# smrf-v1_0_1b.net
KiCad netlist of a schematic drawn in EAGLE
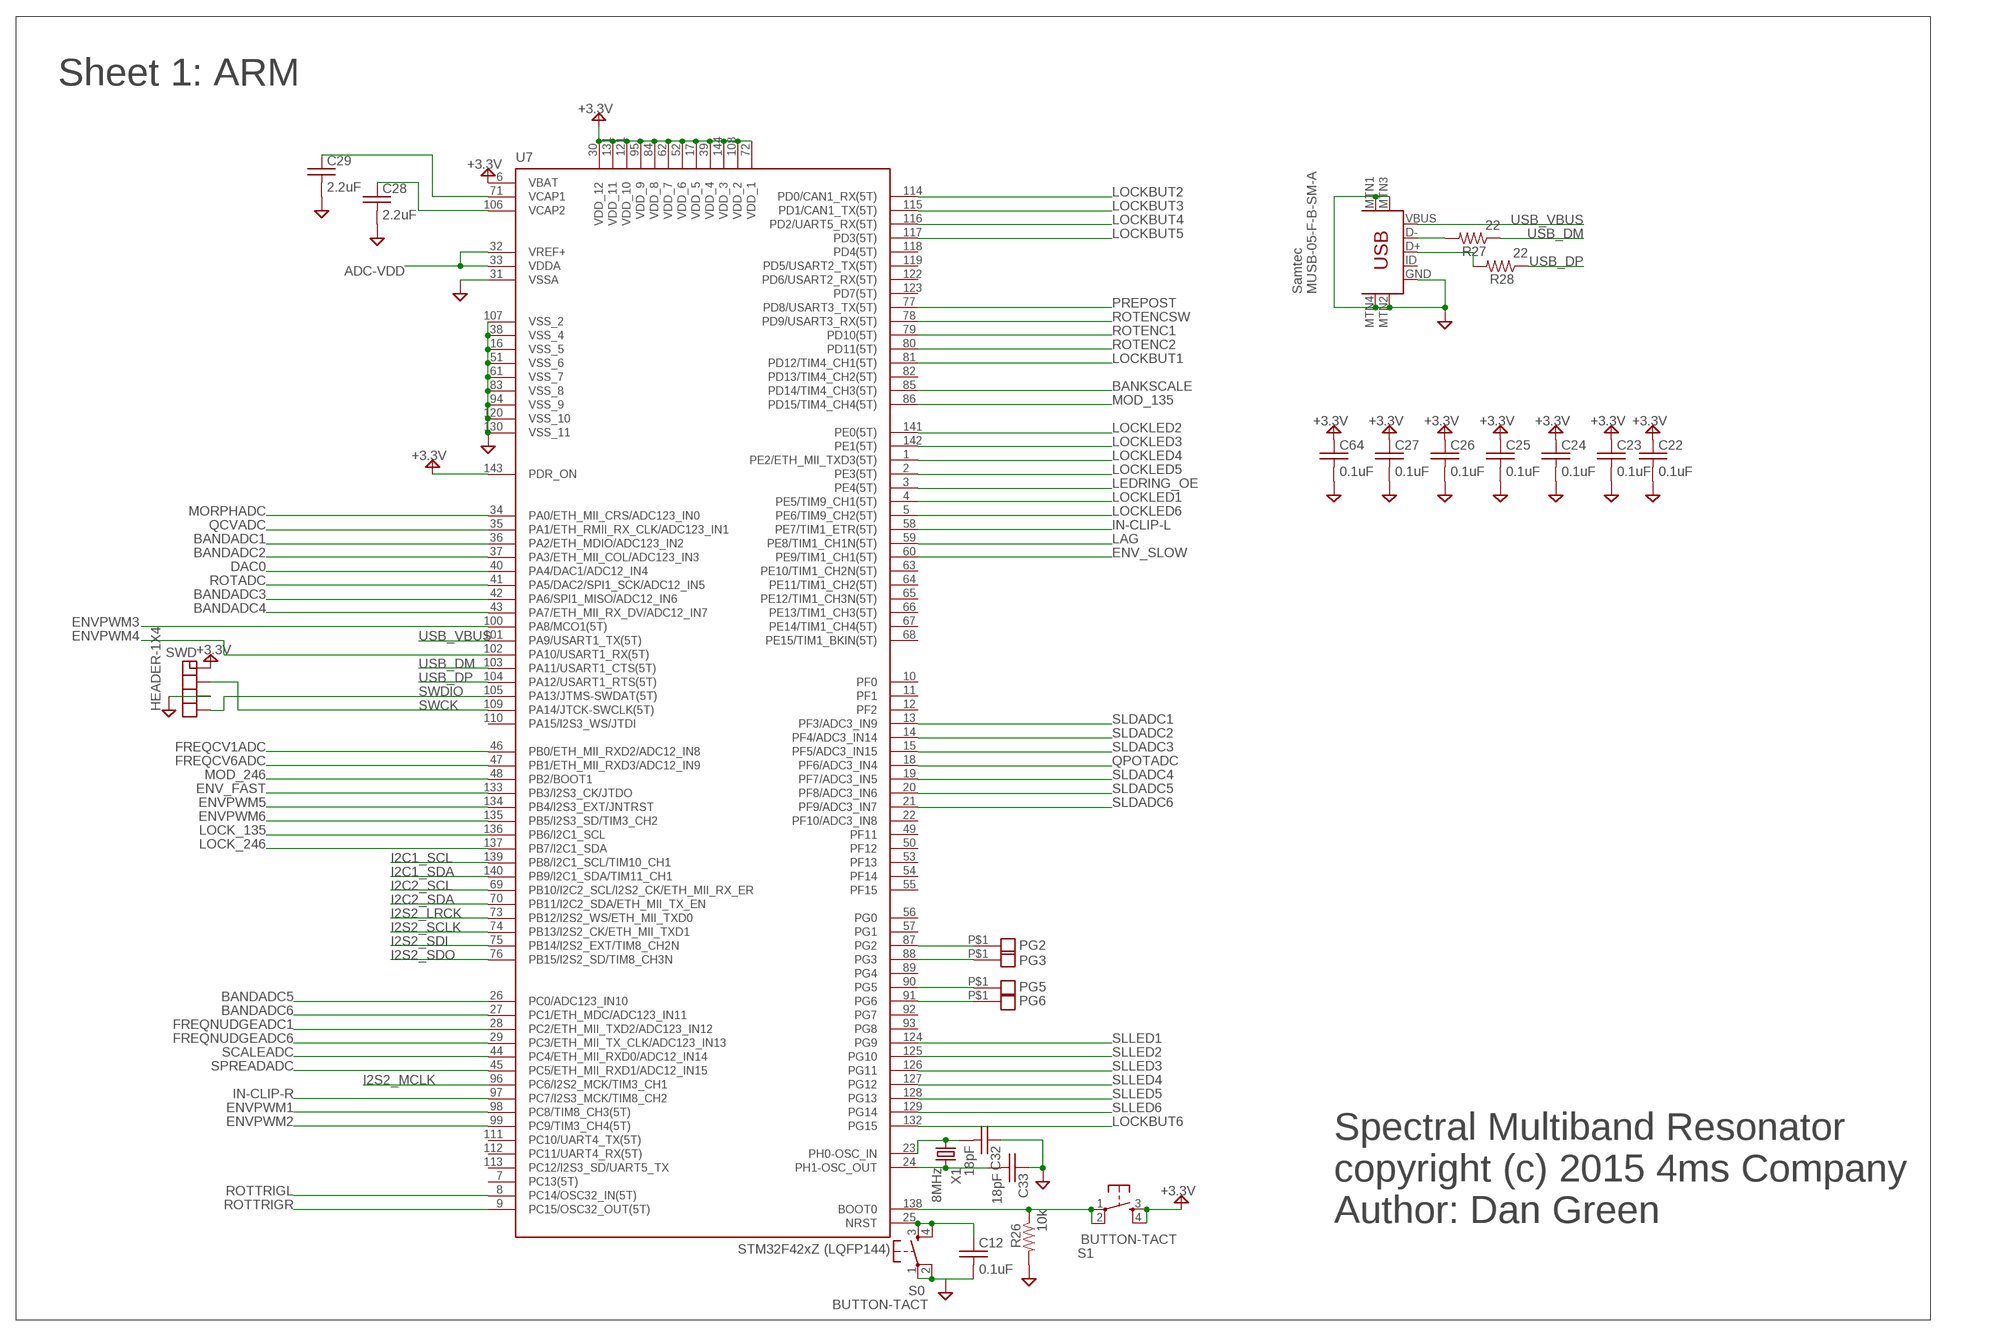
[diagram p0: schematic, sheet 1]
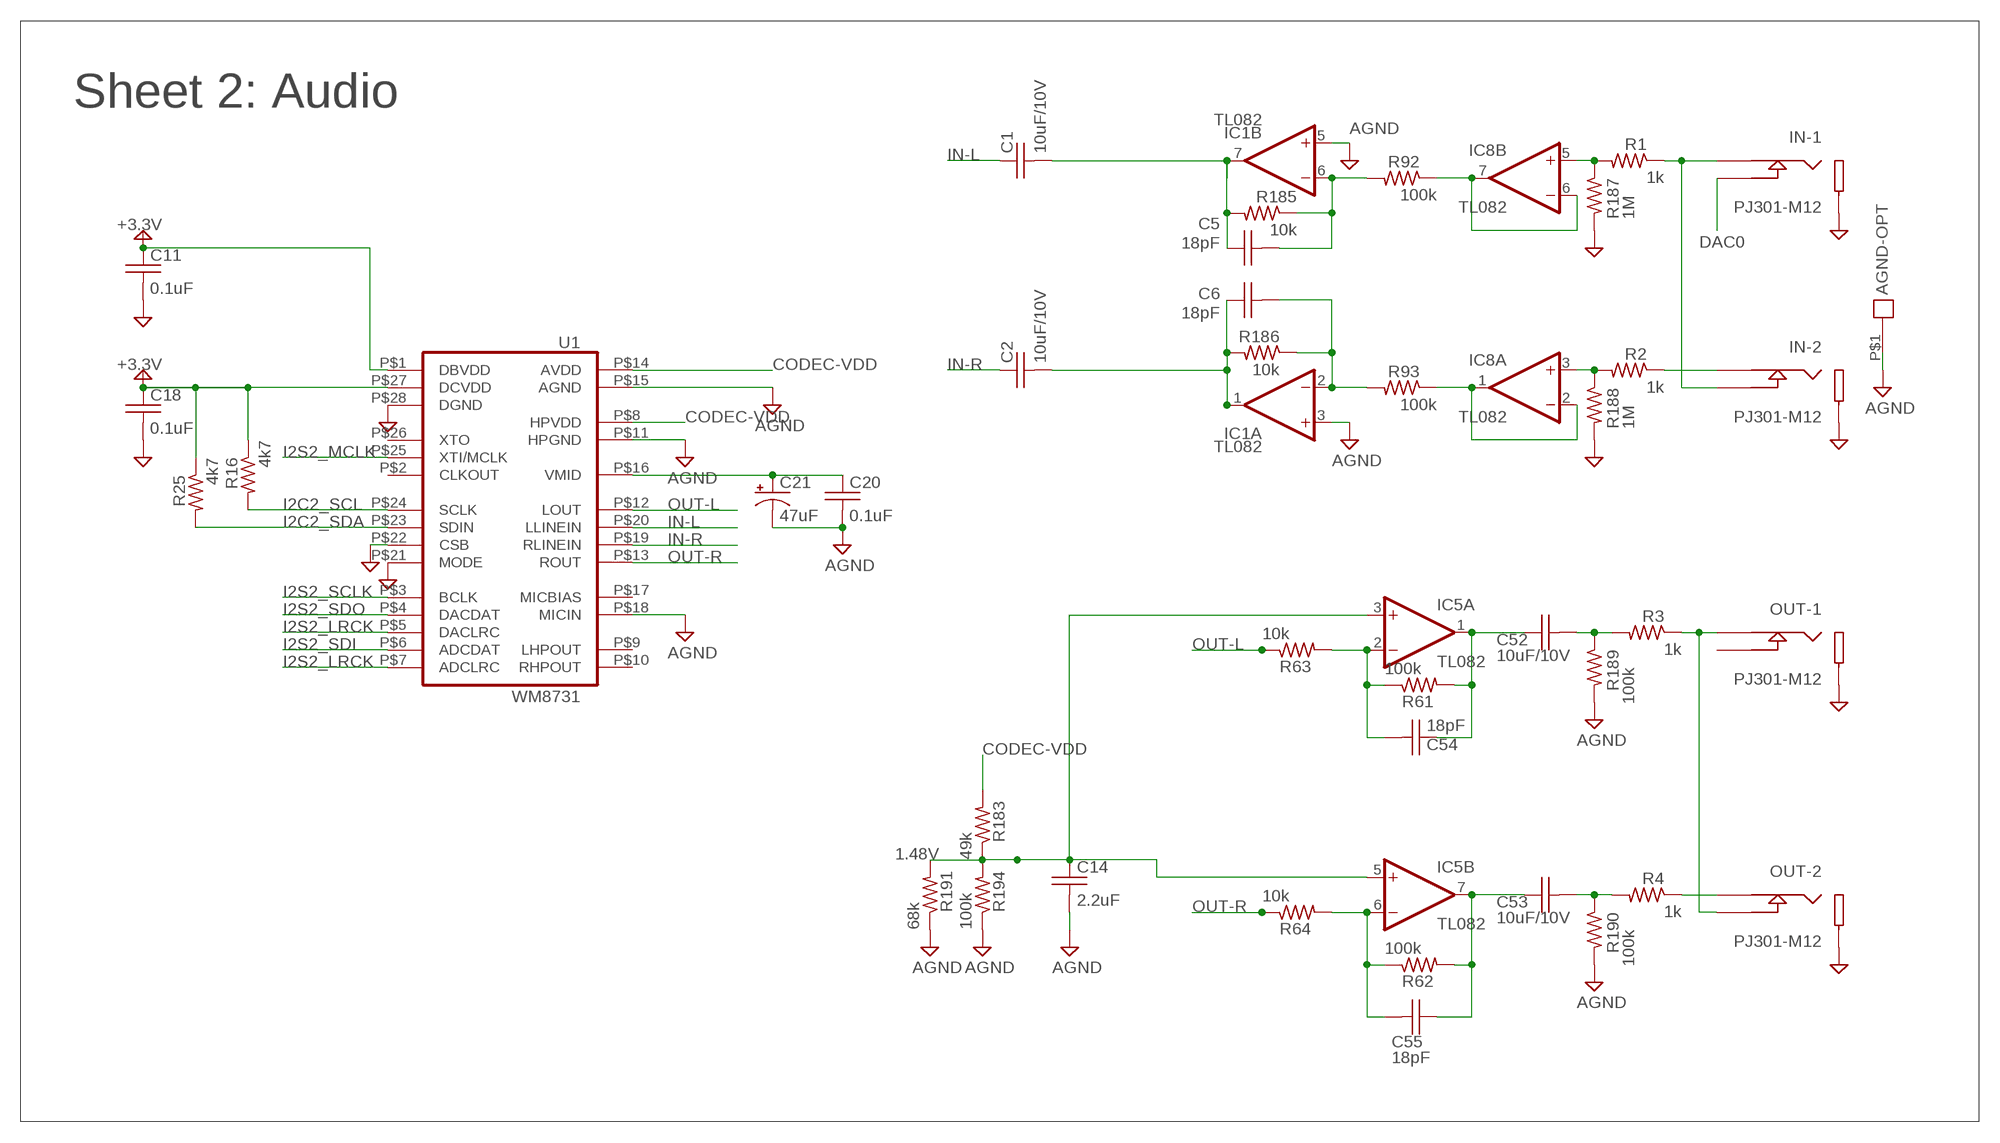
[diagram p1: schematic, sheet 2]
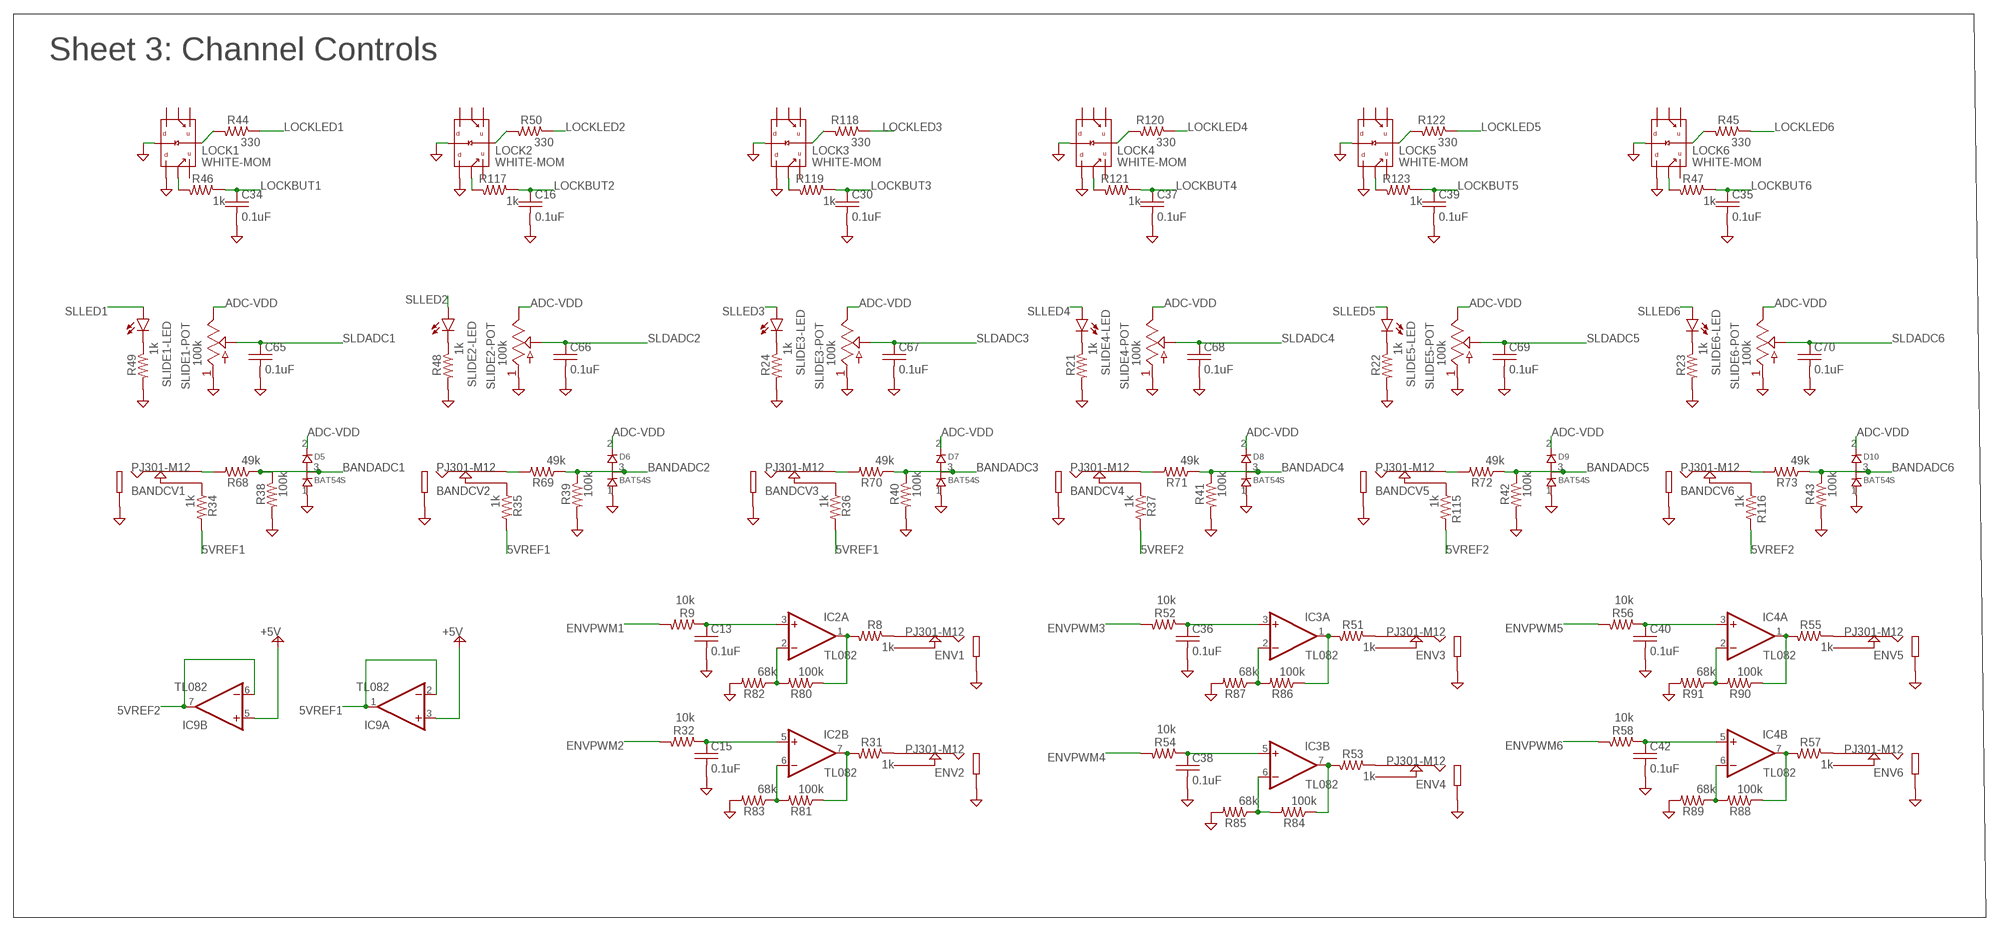
[diagram p2: schematic, sheet 3]
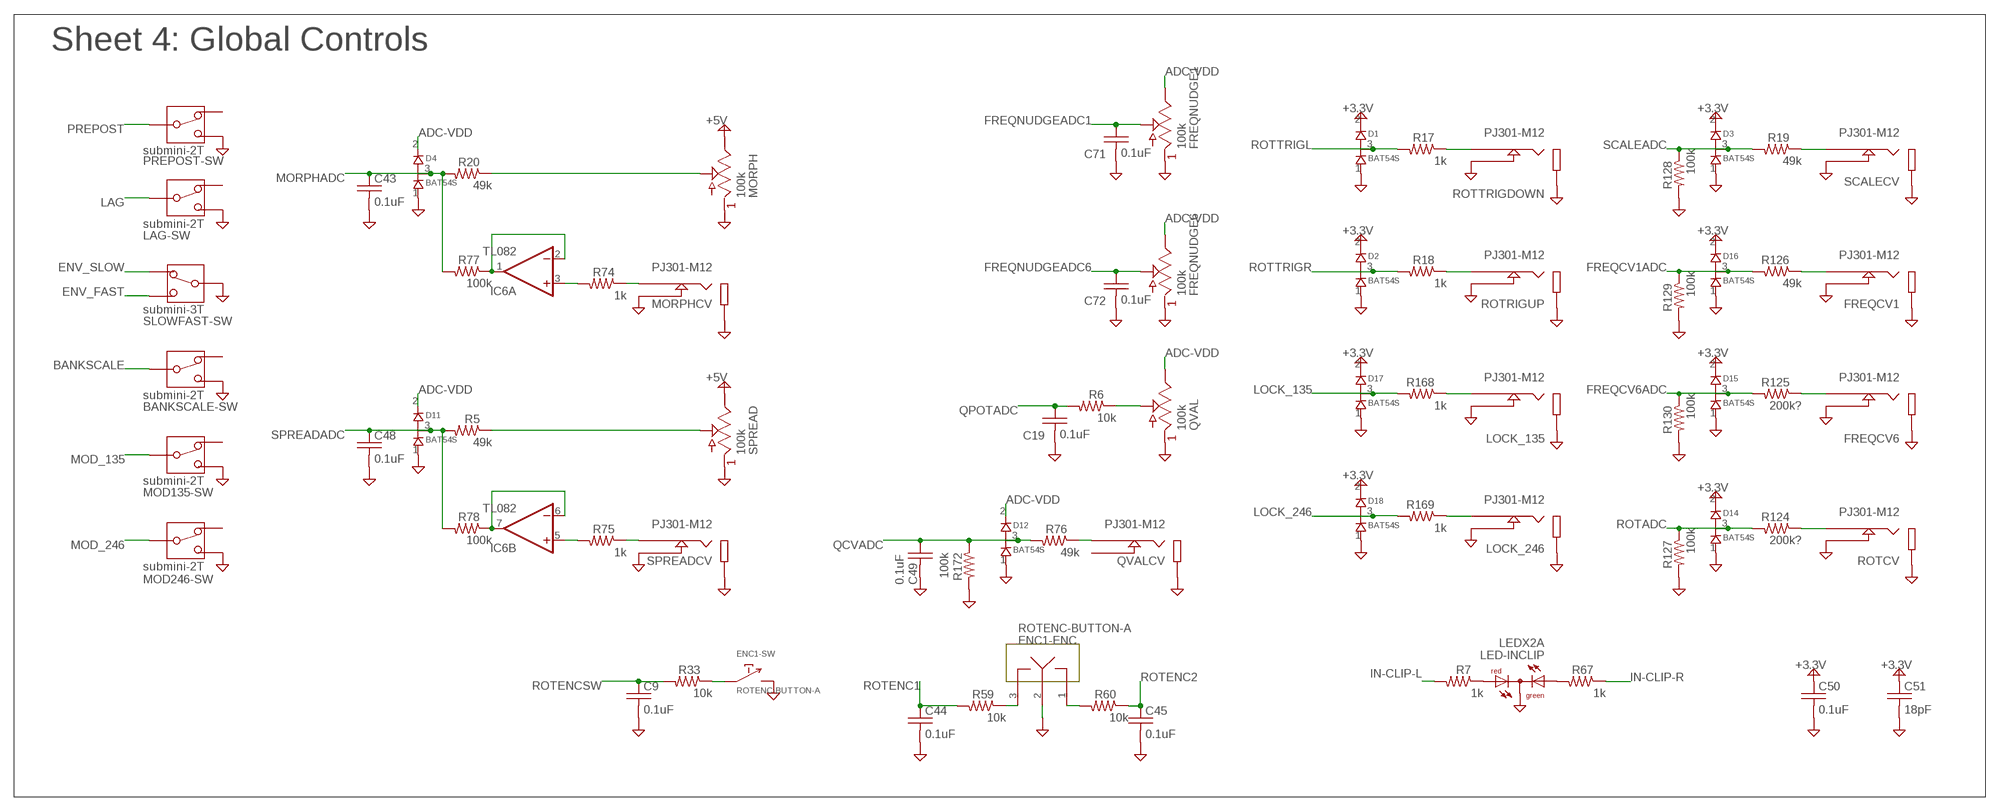
[diagram p3: schematic, sheet 4]
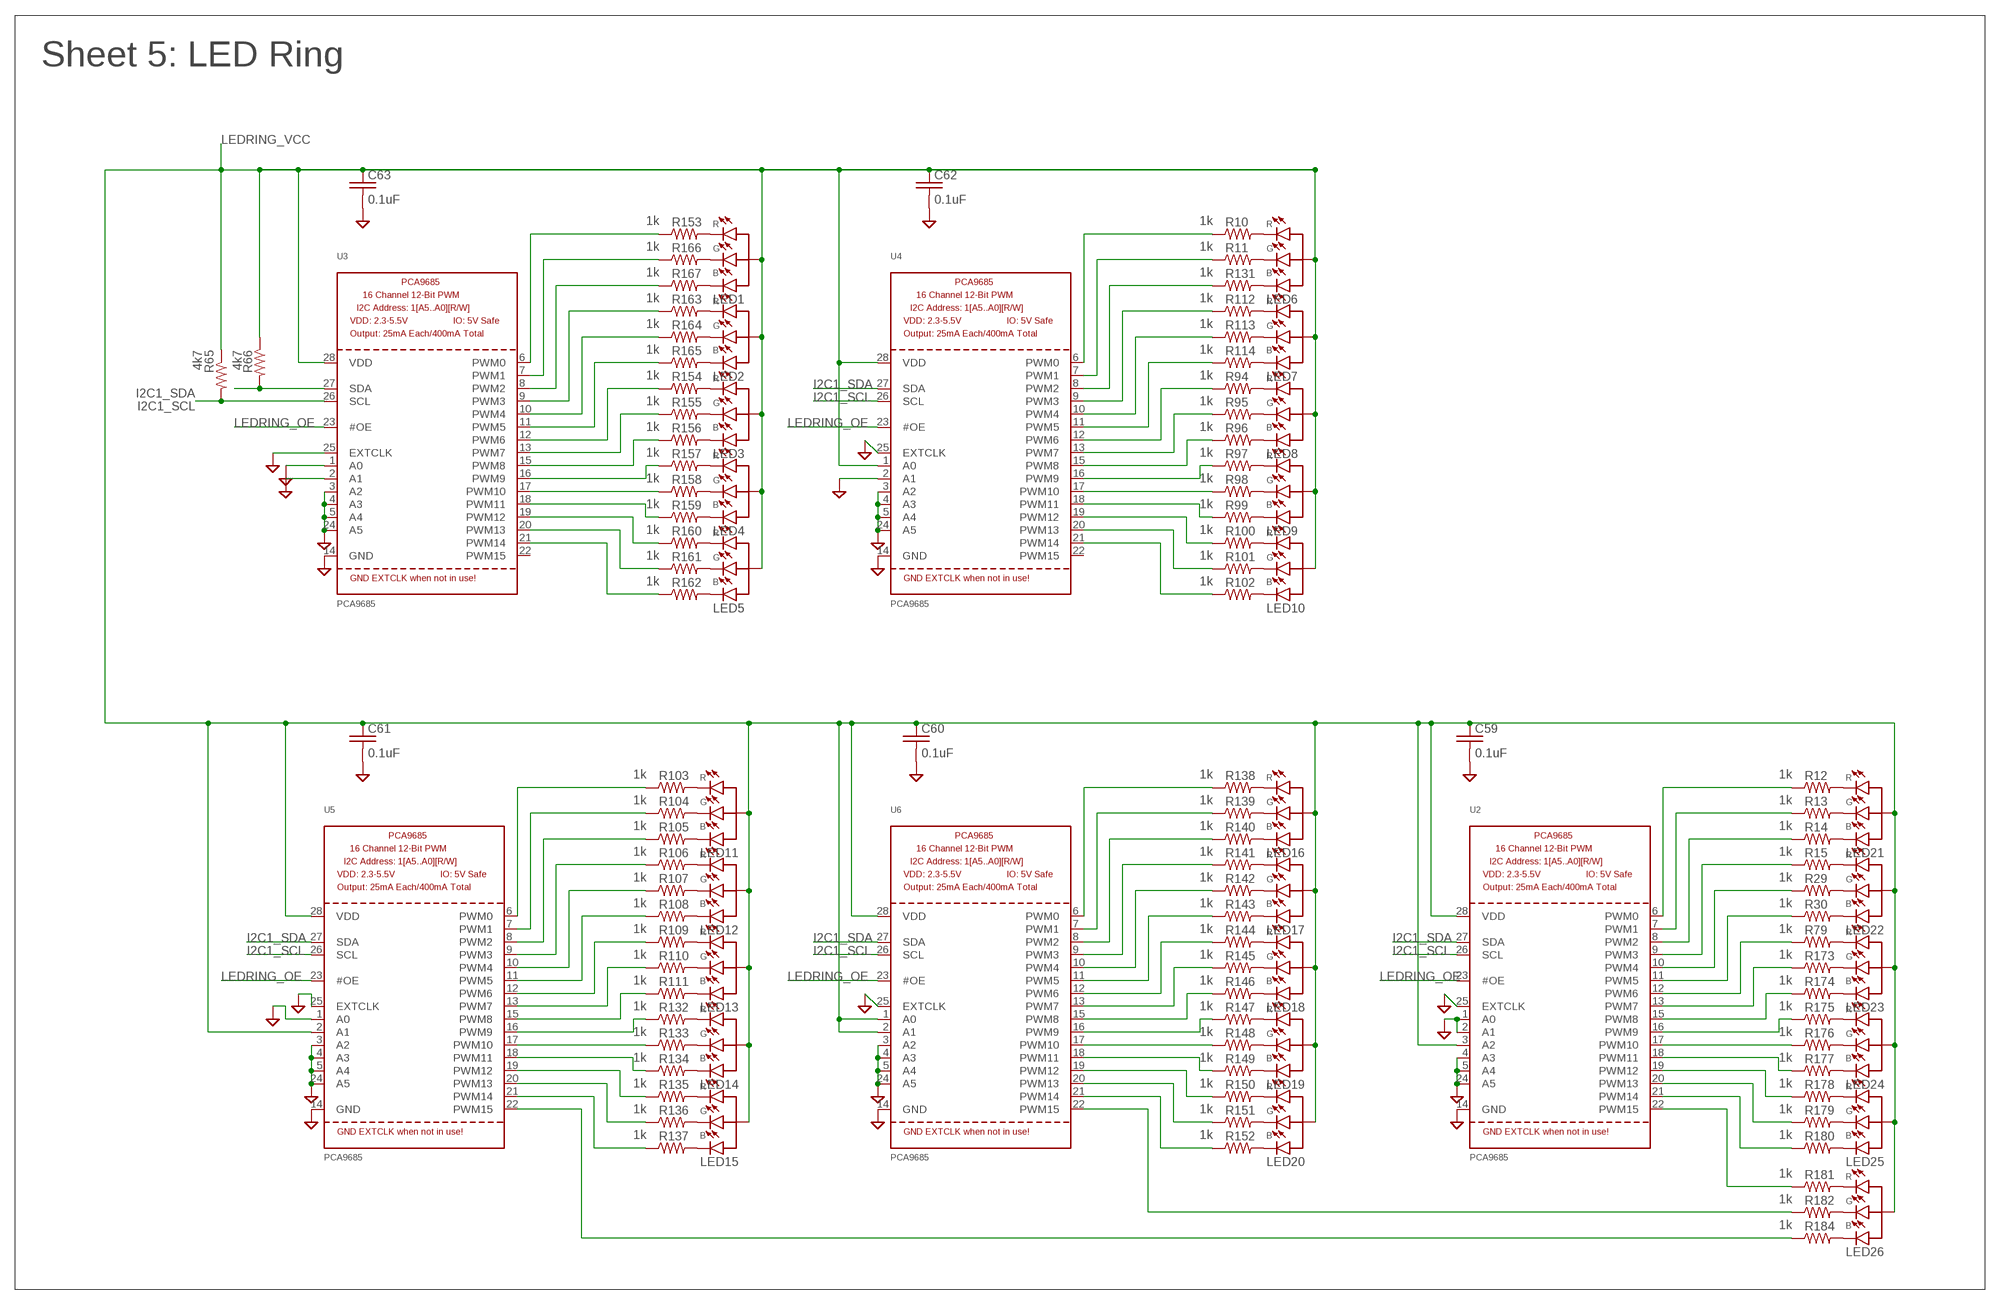
[diagram p4: schematic, sheet 5]
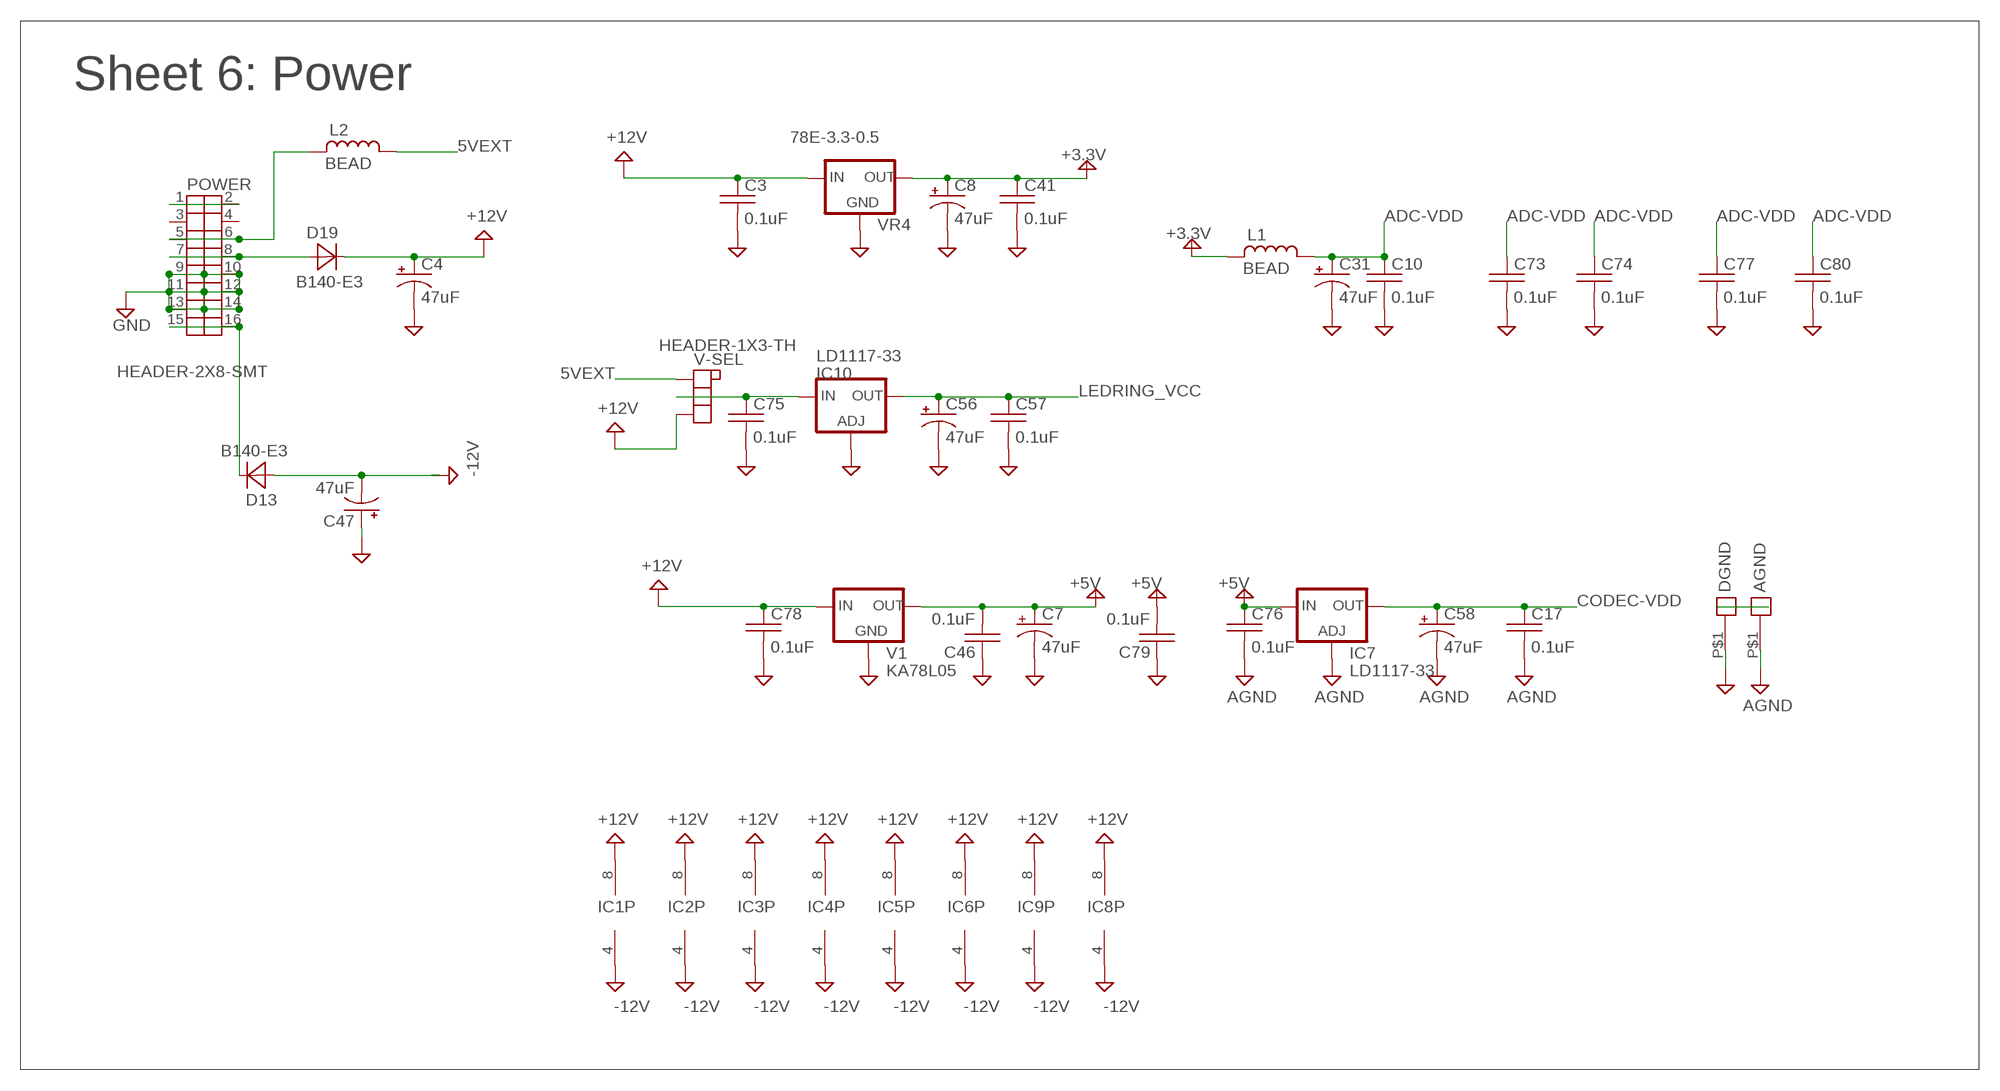
[diagram p5: schematic, sheet 6]

(export (version "E")
  (design (tool "Eeschema 10.0.6"))
  (components
    (comp (ref "BANKSCALE-SW")
      (value "submini-2T")
      (footprint "eagle-import:SPDT-SUB")
      (libsource (lib "eagle-import") (part "SPDTT"))
    )
    (comp (ref "C9")
      (value "0.1uF")
      (footprint "eagle-import:C0603")
      (libsource (lib "eagle-import") (part "CB"))
    )
    (comp (ref "C19")
      (value "0.1uF")
      (footprint "eagle-import:C0603")
      (libsource (lib "eagle-import") (part "CB"))
    )
    (comp (ref "C43")
      (value "0.1uF")
      (footprint "eagle-import:C0603")
      (libsource (lib "eagle-import") (part "CB"))
    )
    (comp (ref "C44")
      (value "0.1uF")
      (footprint "eagle-import:C0603")
      (libsource (lib "eagle-import") (part "CB"))
    )
    (comp (ref "C45")
      (value "0.1uF")
      (footprint "eagle-import:C0603")
      (libsource (lib "eagle-import") (part "CB"))
    )
    (comp (ref "C48")
      (value "0.1uF")
      (footprint "eagle-import:C0603")
      (libsource (lib "eagle-import") (part "CB"))
    )
    (comp (ref "C49")
      (value "0.1uF")
      (footprint "eagle-import:C0603")
      (libsource (lib "eagle-import") (part "CB"))
    )
    (comp (ref "C50")
      (value "0.1uF")
      (footprint "eagle-import:C0603")
      (libsource (lib "eagle-import") (part "CB"))
    )
    (comp (ref "C51")
      (value "18pF")
      (footprint "eagle-import:C0603")
      (libsource (lib "eagle-import") (part "CB"))
    )
    (comp (ref "C71")
      (value "0.1uF")
      (footprint "eagle-import:C0603")
      (libsource (lib "eagle-import") (part "CB"))
    )
    (comp (ref "C72")
      (value "0.1uF")
      (footprint "eagle-import:C0603")
      (libsource (lib "eagle-import") (part "CB"))
    )
    (comp (ref "D1")
      (value "BAT54S")
      (footprint "eagle-import:SOT23")
      (libsource (lib "eagle-import") (part "DIODE-DUAL"))
    )
    (comp (ref "D2")
      (value "BAT54S")
      (footprint "eagle-import:SOT23")
      (libsource (lib "eagle-import") (part "DIODE-DUAL"))
    )
    (comp (ref "D3")
      (value "BAT54S")
      (footprint "eagle-import:SOT23")
      (libsource (lib "eagle-import") (part "DIODE-DUAL"))
    )
    (comp (ref "D4")
      (value "BAT54S")
      (footprint "eagle-import:SOT23")
      (libsource (lib "eagle-import") (part "DIODE-DUAL"))
    )
    (comp (ref "D11")
      (value "BAT54S")
      (footprint "eagle-import:SOT23")
      (libsource (lib "eagle-import") (part "DIODE-DUAL"))
    )
    (comp (ref "D12")
      (value "BAT54S")
      (footprint "eagle-import:SOT23")
      (libsource (lib "eagle-import") (part "DIODE-DUAL"))
    )
    (comp (ref "D14")
      (value "BAT54S")
      (footprint "eagle-import:SOT23")
      (libsource (lib "eagle-import") (part "DIODE-DUAL"))
    )
    (comp (ref "D15")
      (value "BAT54S")
      (footprint "eagle-import:SOT23")
      (libsource (lib "eagle-import") (part "DIODE-DUAL"))
    )
    (comp (ref "D16")
      (value "BAT54S")
      (footprint "eagle-import:SOT23")
      (libsource (lib "eagle-import") (part "DIODE-DUAL"))
    )
    (comp (ref "D17")
      (value "BAT54S")
      (footprint "eagle-import:SOT23")
      (libsource (lib "eagle-import") (part "DIODE-DUAL"))
    )
    (comp (ref "D18")
      (value "BAT54S")
      (footprint "eagle-import:SOT23")
      (libsource (lib "eagle-import") (part "DIODE-DUAL"))
    )
    (comp (ref "ENC1")
      (value "ROTENC-BUTTON-A")
      (footprint "eagle-import:ROTENC-12MM-BUT")
      (libsource (lib "eagle-import") (part "ROTENC-BUTTON-A"))
    )
    (comp (ref "FREQCV1")
      (value "PJ301-M12")
      (footprint "eagle-import:PJ301M-12-FIX")
      (libsource (lib "eagle-import") (part "JACK-MONO-SWM2"))
    )
    (comp (ref "FREQCV6")
      (value "PJ301-M12")
      (footprint "eagle-import:PJ301M-12-FIX")
      (libsource (lib "eagle-import") (part "JACK-MONO-SWM2"))
    )
    (comp (ref "FREQNUDGE1")
      (value "100k")
      (footprint "eagle-import:POT-9MM-SONGHUEI")
      (libsource (lib "eagle-import") (part "POTR0904N"))
    )
    (comp (ref "FREQNUDGE6")
      (value "100k")
      (footprint "eagle-import:POT-9MM-SONGHUEI")
      (libsource (lib "eagle-import") (part "POTR0904N"))
    )
    (comp (ref "IC6")
      (value "TL082")
      (footprint "eagle-import:TSSOP8")
      (libsource (lib "eagle-import") (part "OPAMP-2TL072T"))
    )
    (comp (ref "LAG-SW")
      (value "submini-2T")
      (footprint "eagle-import:SPDT-SUB")
      (libsource (lib "eagle-import") (part "SPDTT"))
    )
    (comp (ref "LED-INCLIP")
      (value "LEDX2A")
      (footprint "eagle-import:LED-T1X2")
      (libsource (lib "eagle-import") (part "LEDX2A"))
    )
    (comp (ref "LOCK_135")
      (value "PJ301-M12")
      (footprint "eagle-import:PJ301M-12-FIX")
      (libsource (lib "eagle-import") (part "JACK-MONO-SWM2"))
    )
    (comp (ref "LOCK_246")
      (value "PJ301-M12")
      (footprint "eagle-import:PJ301M-12-FIX")
      (libsource (lib "eagle-import") (part "JACK-MONO-SWM2"))
    )
    (comp (ref "MOD135-SW")
      (value "submini-2T")
      (footprint "eagle-import:SPDT-SUB")
      (libsource (lib "eagle-import") (part "SPDTT"))
    )
    (comp (ref "MOD246-SW")
      (value "submini-2T")
      (footprint "eagle-import:SPDT-SUB")
      (libsource (lib "eagle-import") (part "SPDTT"))
    )
    (comp (ref "MORPH")
      (value "100k")
      (footprint "eagle-import:POT-9MM-SONGHUEI")
      (libsource (lib "eagle-import") (part "POTR0904N"))
    )
    (comp (ref "MORPHCV")
      (value "PJ301-M12")
      (footprint "eagle-import:PJ301M-12-FIX")
      (libsource (lib "eagle-import") (part "JACK-MONO-SWM2"))
    )
    (comp (ref "PREPOST-SW")
      (value "submini-2T")
      (footprint "eagle-import:SPDT-SUB")
      (libsource (lib "eagle-import") (part "SPDTT"))
    )
    (comp (ref "QVAL")
      (value "100k")
      (footprint "eagle-import:POT-9MM-SONGHUEI")
      (libsource (lib "eagle-import") (part "POTR0904N"))
    )
    (comp (ref "QVALCV")
      (value "PJ301-M12")
      (footprint "eagle-import:PJ301M-12-FIX")
      (libsource (lib "eagle-import") (part "JACK-MONO-SWM2"))
    )
    (comp (ref "R5")
      (value "49k")
      (footprint "eagle-import:R0603")
      (libsource (lib "eagle-import") (part "malekko main_RB"))
    )
    (comp (ref "R6")
      (value "10k")
      (footprint "eagle-import:R0603")
      (libsource (lib "eagle-import") (part "malekko main_RB"))
    )
    (comp (ref "R7")
      (value "1k")
      (footprint "eagle-import:R0603")
      (libsource (lib "eagle-import") (part "malekko main_RB"))
    )
    (comp (ref "R17")
      (value "1k")
      (footprint "eagle-import:R0603")
      (libsource (lib "eagle-import") (part "RB"))
    )
    (comp (ref "R18")
      (value "1k")
      (footprint "eagle-import:R0603")
      (libsource (lib "eagle-import") (part "RB"))
    )
    (comp (ref "R19")
      (value "49k")
      (footprint "eagle-import:R0603")
      (libsource (lib "eagle-import") (part "RB"))
    )
    (comp (ref "R20")
      (value "49k")
      (footprint "eagle-import:R0603")
      (libsource (lib "eagle-import") (part "malekko main_RB"))
    )
    (comp (ref "R33")
      (value "10k")
      (footprint "eagle-import:R0603")
      (libsource (lib "eagle-import") (part "RB"))
    )
    (comp (ref "R59")
      (value "10k")
      (footprint "eagle-import:R0603")
      (libsource (lib "eagle-import") (part "RB"))
    )
    (comp (ref "R60")
      (value "10k")
      (footprint "eagle-import:R0603")
      (libsource (lib "eagle-import") (part "RB"))
    )
    (comp (ref "R67")
      (value "1k")
      (footprint "eagle-import:R0603")
      (libsource (lib "eagle-import") (part "malekko main_RB"))
    )
    (comp (ref "R74")
      (value "1k")
      (footprint "eagle-import:R0603")
      (libsource (lib "eagle-import") (part "malekko main_RB"))
    )
    (comp (ref "R75")
      (value "1k")
      (footprint "eagle-import:R0603")
      (libsource (lib "eagle-import") (part "malekko main_RB"))
    )
    (comp (ref "R76")
      (value "49k")
      (footprint "eagle-import:R0603")
      (libsource (lib "eagle-import") (part "malekko main_RB"))
    )
    (comp (ref "R77")
      (value "100k")
      (footprint "eagle-import:R0603")
      (libsource (lib "eagle-import") (part "malekko main_RB"))
    )
    (comp (ref "R78")
      (value "100k")
      (footprint "eagle-import:R0603")
      (libsource (lib "eagle-import") (part "malekko main_RB"))
    )
    (comp (ref "R124")
      (value "200k?")
      (footprint "eagle-import:R0603")
      (libsource (lib "eagle-import") (part "RB"))
    )
    (comp (ref "R125")
      (value "200k?")
      (footprint "eagle-import:R0603")
      (libsource (lib "eagle-import") (part "RB"))
    )
    (comp (ref "R126")
      (value "49k")
      (footprint "eagle-import:R0603")
      (libsource (lib "eagle-import") (part "RB"))
    )
    (comp (ref "R127")
      (value "100k")
      (footprint "eagle-import:R0603")
      (libsource (lib "eagle-import") (part "RB"))
    )
    (comp (ref "R128")
      (value "100k")
      (footprint "eagle-import:R0603")
      (libsource (lib "eagle-import") (part "RB"))
    )
    (comp (ref "R129")
      (value "100k")
      (footprint "eagle-import:R0603")
      (libsource (lib "eagle-import") (part "RB"))
    )
    (comp (ref "R130")
      (value "100k")
      (footprint "eagle-import:R0603")
      (libsource (lib "eagle-import") (part "RB"))
    )
    (comp (ref "R168")
      (value "1k")
      (footprint "eagle-import:R0603")
      (libsource (lib "eagle-import") (part "RB"))
    )
    (comp (ref "R169")
      (value "1k")
      (footprint "eagle-import:R0603")
      (libsource (lib "eagle-import") (part "RB"))
    )
    (comp (ref "R172")
      (value "100k")
      (footprint "eagle-import:R0603")
      (libsource (lib "eagle-import") (part "malekko main_RB"))
    )
    (comp (ref "ROTCV")
      (value "PJ301-M12")
      (footprint "eagle-import:PJ301M-12-FIX")
      (libsource (lib "eagle-import") (part "JACK-MONO-SWM2"))
    )
    (comp (ref "ROTRIGUP")
      (value "PJ301-M12")
      (footprint "eagle-import:PJ301M-12-FIX")
      (libsource (lib "eagle-import") (part "JACK-MONO-SWM2"))
    )
    (comp (ref "ROTTRIGDOWN")
      (value "PJ301-M12")
      (footprint "eagle-import:PJ301M-12-FIX")
      (libsource (lib "eagle-import") (part "JACK-MONO-SWM2"))
    )
    (comp (ref "SCALECV")
      (value "PJ301-M12")
      (footprint "eagle-import:PJ301M-12-FIX")
      (libsource (lib "eagle-import") (part "JACK-MONO-SWM2"))
    )
    (comp (ref "SLOWFAST-SW")
      (value "submini-3T")
      (footprint "eagle-import:SPDT-SUB")
      (libsource (lib "eagle-import") (part "SPDTT"))
    )
    (comp (ref "SPREAD")
      (value "100k")
      (footprint "eagle-import:POT-9MM-SONGHUEI")
      (libsource (lib "eagle-import") (part "POTR0904N"))
    )
    (comp (ref "SPREADCV")
      (value "PJ301-M12")
      (footprint "eagle-import:PJ301M-12-FIX")
      (libsource (lib "eagle-import") (part "JACK-MONO-SWM2"))
    )
    (comp (ref "C59")
      (value "0.1uF")
      (footprint "eagle-import:C0603")
      (libsource (lib "eagle-import") (part "CB"))
    )
    (comp (ref "C60")
      (value "0.1uF")
      (footprint "eagle-import:C0603")
      (libsource (lib "eagle-import") (part "CB"))
    )
    (comp (ref "C61")
      (value "0.1uF")
      (footprint "eagle-import:C0603")
      (libsource (lib "eagle-import") (part "CB"))
    )
    (comp (ref "C62")
      (value "0.1uF")
      (footprint "eagle-import:C0603")
      (libsource (lib "eagle-import") (part "CB"))
    )
    (comp (ref "C63")
      (value "0.1uF")
      (footprint "eagle-import:C0603")
      (libsource (lib "eagle-import") (part "CB"))
    )
    (comp (ref "LED1")
      (value "LED-RGB-CA-HEBEI")
      (footprint "eagle-import:PLCC4")
      (libsource (lib "eagle-import") (part "LED-RGB-CA-HEBEI"))
    )
    (comp (ref "LED2")
      (value "LED-RGB-CA-HEBEI")
      (footprint "eagle-import:PLCC4")
      (libsource (lib "eagle-import") (part "LED-RGB-CA-HEBEI"))
    )
    (comp (ref "LED3")
      (value "LED-RGB-CA-HEBEI")
      (footprint "eagle-import:PLCC4")
      (libsource (lib "eagle-import") (part "LED-RGB-CA-HEBEI"))
    )
    (comp (ref "LED4")
      (value "LED-RGB-CA-HEBEI")
      (footprint "eagle-import:PLCC4")
      (libsource (lib "eagle-import") (part "LED-RGB-CA-HEBEI"))
    )
    (comp (ref "LED5")
      (value "LED-RGB-CA-HEBEI")
      (footprint "eagle-import:PLCC4")
      (libsource (lib "eagle-import") (part "LED-RGB-CA-HEBEI"))
    )
    (comp (ref "LED6")
      (value "LED-RGB-CA-HEBEI")
      (footprint "eagle-import:PLCC4")
      (libsource (lib "eagle-import") (part "LED-RGB-CA-HEBEI"))
    )
    (comp (ref "LED7")
      (value "LED-RGB-CA-HEBEI")
      (footprint "eagle-import:PLCC4")
      (libsource (lib "eagle-import") (part "LED-RGB-CA-HEBEI"))
    )
    (comp (ref "LED8")
      (value "LED-RGB-CA-HEBEI")
      (footprint "eagle-import:PLCC4")
      (libsource (lib "eagle-import") (part "LED-RGB-CA-HEBEI"))
    )
    (comp (ref "LED9")
      (value "LED-RGB-CA-HEBEI")
      (footprint "eagle-import:PLCC4")
      (libsource (lib "eagle-import") (part "LED-RGB-CA-HEBEI"))
    )
    (comp (ref "LED10")
      (value "LED-RGB-CA-HEBEI")
      (footprint "eagle-import:PLCC4")
      (libsource (lib "eagle-import") (part "LED-RGB-CA-HEBEI"))
    )
    (comp (ref "LED11")
      (value "LED-RGB-CA-HEBEI")
      (footprint "eagle-import:PLCC4")
      (libsource (lib "eagle-import") (part "LED-RGB-CA-HEBEI"))
    )
    (comp (ref "LED12")
      (value "LED-RGB-CA-HEBEI")
      (footprint "eagle-import:PLCC4")
      (libsource (lib "eagle-import") (part "LED-RGB-CA-HEBEI"))
    )
    (comp (ref "LED13")
      (value "LED-RGB-CA-HEBEI")
      (footprint "eagle-import:PLCC4")
      (libsource (lib "eagle-import") (part "LED-RGB-CA-HEBEI"))
    )
    (comp (ref "LED14")
      (value "LED-RGB-CA-HEBEI")
      (footprint "eagle-import:PLCC4")
      (libsource (lib "eagle-import") (part "LED-RGB-CA-HEBEI"))
    )
    (comp (ref "LED15")
      (value "LED-RGB-CA-HEBEI")
      (footprint "eagle-import:PLCC4")
      (libsource (lib "eagle-import") (part "LED-RGB-CA-HEBEI"))
    )
    (comp (ref "LED16")
      (value "LED-RGB-CA-HEBEI")
      (footprint "eagle-import:PLCC4")
      (libsource (lib "eagle-import") (part "LED-RGB-CA-HEBEI"))
    )
    (comp (ref "LED17")
      (value "LED-RGB-CA-HEBEI")
      (footprint "eagle-import:PLCC4")
      (libsource (lib "eagle-import") (part "LED-RGB-CA-HEBEI"))
    )
    (comp (ref "LED18")
      (value "LED-RGB-CA-HEBEI")
      (footprint "eagle-import:PLCC4")
      (libsource (lib "eagle-import") (part "LED-RGB-CA-HEBEI"))
    )
    (comp (ref "LED19")
      (value "LED-RGB-CA-HEBEI")
      (footprint "eagle-import:PLCC4")
      (libsource (lib "eagle-import") (part "LED-RGB-CA-HEBEI"))
    )
    (comp (ref "LED20")
      (value "LED-RGB-CA-HEBEI")
      (footprint "eagle-import:PLCC4")
      (libsource (lib "eagle-import") (part "LED-RGB-CA-HEBEI"))
    )
    (comp (ref "LED21")
      (value "LED-RGB-CA-HEBEI")
      (footprint "eagle-import:PLCC4")
      (libsource (lib "eagle-import") (part "LED-RGB-CA-HEBEI"))
    )
    (comp (ref "LED22")
      (value "LED-RGB-CA-HEBEI")
      (footprint "eagle-import:PLCC4")
      (libsource (lib "eagle-import") (part "LED-RGB-CA-HEBEI"))
    )
    (comp (ref "LED23")
      (value "LED-RGB-CA-HEBEI")
      (footprint "eagle-import:PLCC4")
      (libsource (lib "eagle-import") (part "LED-RGB-CA-HEBEI"))
    )
    (comp (ref "LED24")
      (value "LED-RGB-CA-HEBEI")
      (footprint "eagle-import:PLCC4")
      (libsource (lib "eagle-import") (part "LED-RGB-CA-HEBEI"))
    )
    (comp (ref "LED25")
      (value "LED-RGB-CA-HEBEI")
      (footprint "eagle-import:PLCC4")
      (libsource (lib "eagle-import") (part "LED-RGB-CA-HEBEI"))
    )
    (comp (ref "LED26")
      (value "LED-RGB-CA-HEBEI")
      (footprint "eagle-import:PLCC4")
      (libsource (lib "eagle-import") (part "LED-RGB-CA-HEBEI"))
    )
    (comp (ref "R10")
      (value "1k")
      (footprint "eagle-import:R0603")
      (libsource (lib "eagle-import") (part "RB"))
    )
    (comp (ref "R11")
      (value "1k")
      (footprint "eagle-import:R0603")
      (libsource (lib "eagle-import") (part "RB"))
    )
    (comp (ref "R12")
      (value "1k")
      (footprint "eagle-import:R0603")
      (libsource (lib "eagle-import") (part "RB"))
    )
    (comp (ref "R13")
      (value "1k")
      (footprint "eagle-import:R0603")
      (libsource (lib "eagle-import") (part "RB"))
    )
    (comp (ref "R14")
      (value "1k")
      (footprint "eagle-import:R0603")
      (libsource (lib "eagle-import") (part "RB"))
    )
    (comp (ref "R15")
      (value "1k")
      (footprint "eagle-import:R0603")
      (libsource (lib "eagle-import") (part "RB"))
    )
    (comp (ref "R29")
      (value "1k")
      (footprint "eagle-import:R0603")
      (libsource (lib "eagle-import") (part "RB"))
    )
    (comp (ref "R30")
      (value "1k")
      (footprint "eagle-import:R0603")
      (libsource (lib "eagle-import") (part "RB"))
    )
    (comp (ref "R65")
      (value "4k7")
      (footprint "eagle-import:R0603")
      (libsource (lib "eagle-import") (part "malekko main_RB"))
    )
    (comp (ref "R66")
      (value "4k7")
      (footprint "eagle-import:R0603")
      (libsource (lib "eagle-import") (part "malekko main_RB"))
    )
    (comp (ref "R79")
      (value "1k")
      (footprint "eagle-import:R0603")
      (libsource (lib "eagle-import") (part "RB"))
    )
    (comp (ref "R94")
      (value "1k")
      (footprint "eagle-import:R0603")
      (libsource (lib "eagle-import") (part "RB"))
    )
    (comp (ref "R95")
      (value "1k")
      (footprint "eagle-import:R0603")
      (libsource (lib "eagle-import") (part "RB"))
    )
    (comp (ref "R96")
      (value "1k")
      (footprint "eagle-import:R0603")
      (libsource (lib "eagle-import") (part "RB"))
    )
    (comp (ref "R97")
      (value "1k")
      (footprint "eagle-import:R0603")
      (libsource (lib "eagle-import") (part "RB"))
    )
    (comp (ref "R98")
      (value "1k")
      (footprint "eagle-import:R0603")
      (libsource (lib "eagle-import") (part "RB"))
    )
    (comp (ref "R99")
      (value "1k")
      (footprint "eagle-import:R0603")
      (libsource (lib "eagle-import") (part "RB"))
    )
    (comp (ref "R100")
      (value "1k")
      (footprint "eagle-import:R0603")
      (libsource (lib "eagle-import") (part "RB"))
    )
    (comp (ref "R101")
      (value "1k")
      (footprint "eagle-import:R0603")
      (libsource (lib "eagle-import") (part "RB"))
    )
    (comp (ref "R102")
      (value "1k")
      (footprint "eagle-import:R0603")
      (libsource (lib "eagle-import") (part "RB"))
    )
    (comp (ref "R103")
      (value "1k")
      (footprint "eagle-import:R0603")
      (libsource (lib "eagle-import") (part "RB"))
    )
    (comp (ref "R104")
      (value "1k")
      (footprint "eagle-import:R0603")
      (libsource (lib "eagle-import") (part "RB"))
    )
    (comp (ref "R105")
      (value "1k")
      (footprint "eagle-import:R0603")
      (libsource (lib "eagle-import") (part "RB"))
    )
    (comp (ref "R106")
      (value "1k")
      (footprint "eagle-import:R0603")
      (libsource (lib "eagle-import") (part "RB"))
    )
    (comp (ref "R107")
      (value "1k")
      (footprint "eagle-import:R0603")
      (libsource (lib "eagle-import") (part "RB"))
    )
    (comp (ref "R108")
      (value "1k")
      (footprint "eagle-import:R0603")
      (libsource (lib "eagle-import") (part "RB"))
    )
    (comp (ref "R109")
      (value "1k")
      (footprint "eagle-import:R0603")
      (libsource (lib "eagle-import") (part "RB"))
    )
    (comp (ref "R110")
      (value "1k")
      (footprint "eagle-import:R0603")
      (libsource (lib "eagle-import") (part "RB"))
    )
    (comp (ref "R111")
      (value "1k")
      (footprint "eagle-import:R0603")
      (libsource (lib "eagle-import") (part "RB"))
    )
    (comp (ref "R112")
      (value "1k")
      (footprint "eagle-import:R0603")
      (libsource (lib "eagle-import") (part "RB"))
    )
    (comp (ref "R113")
      (value "1k")
      (footprint "eagle-import:R0603")
      (libsource (lib "eagle-import") (part "RB"))
    )
    (comp (ref "R114")
      (value "1k")
      (footprint "eagle-import:R0603")
      (libsource (lib "eagle-import") (part "RB"))
    )
    (comp (ref "R131")
      (value "1k")
      (footprint "eagle-import:R0603")
      (libsource (lib "eagle-import") (part "RB"))
    )
    (comp (ref "R132")
      (value "1k")
      (footprint "eagle-import:R0603")
      (libsource (lib "eagle-import") (part "RB"))
    )
    (comp (ref "R133")
      (value "1k")
      (footprint "eagle-import:R0603")
      (libsource (lib "eagle-import") (part "RB"))
    )
    (comp (ref "R134")
      (value "1k")
      (footprint "eagle-import:R0603")
      (libsource (lib "eagle-import") (part "RB"))
    )
    (comp (ref "R135")
      (value "1k")
      (footprint "eagle-import:R0603")
      (libsource (lib "eagle-import") (part "RB"))
    )
    (comp (ref "R136")
      (value "1k")
      (footprint "eagle-import:R0603")
      (libsource (lib "eagle-import") (part "RB"))
    )
    (comp (ref "R137")
      (value "1k")
      (footprint "eagle-import:R0603")
      (libsource (lib "eagle-import") (part "RB"))
    )
    (comp (ref "R138")
      (value "1k")
      (footprint "eagle-import:R0603")
      (libsource (lib "eagle-import") (part "RB"))
    )
    (comp (ref "R139")
      (value "1k")
      (footprint "eagle-import:R0603")
      (libsource (lib "eagle-import") (part "RB"))
    )
    (comp (ref "R140")
      (value "1k")
      (footprint "eagle-import:R0603")
      (libsource (lib "eagle-import") (part "RB"))
    )
    (comp (ref "R141")
      (value "1k")
      (footprint "eagle-import:R0603")
      (libsource (lib "eagle-import") (part "RB"))
    )
    (comp (ref "R142")
      (value "1k")
      (footprint "eagle-import:R0603")
      (libsource (lib "eagle-import") (part "RB"))
    )
    (comp (ref "R143")
      (value "1k")
      (footprint "eagle-import:R0603")
      (libsource (lib "eagle-import") (part "RB"))
    )
    (comp (ref "R144")
      (value "1k")
      (footprint "eagle-import:R0603")
      (libsource (lib "eagle-import") (part "RB"))
    )
    (comp (ref "R145")
      (value "1k")
      (footprint "eagle-import:R0603")
      (libsource (lib "eagle-import") (part "RB"))
    )
    (comp (ref "R146")
      (value "1k")
      (footprint "eagle-import:R0603")
      (libsource (lib "eagle-import") (part "RB"))
    )
    (comp (ref "R147")
      (value "1k")
      (footprint "eagle-import:R0603")
      (libsource (lib "eagle-import") (part "RB"))
    )
    (comp (ref "R148")
      (value "1k")
      (footprint "eagle-import:R0603")
      (libsource (lib "eagle-import") (part "RB"))
    )
    (comp (ref "R149")
      (value "1k")
      (footprint "eagle-import:R0603")
      (libsource (lib "eagle-import") (part "RB"))
    )
    (comp (ref "R150")
      (value "1k")
      (footprint "eagle-import:R0603")
      (libsource (lib "eagle-import") (part "RB"))
    )
    (comp (ref "R151")
      (value "1k")
      (footprint "eagle-import:R0603")
      (libsource (lib "eagle-import") (part "RB"))
    )
    (comp (ref "R152")
      (value "1k")
      (footprint "eagle-import:R0603")
      (libsource (lib "eagle-import") (part "RB"))
    )
    (comp (ref "R153")
      (value "1k")
      (footprint "eagle-import:R0603")
      (libsource (lib "eagle-import") (part "RB"))
    )
    (comp (ref "R154")
      (value "1k")
      (footprint "eagle-import:R0603")
      (libsource (lib "eagle-import") (part "RB"))
    )
    (comp (ref "R155")
      (value "1k")
      (footprint "eagle-import:R0603")
      (libsource (lib "eagle-import") (part "RB"))
    )
    (comp (ref "R156")
      (value "1k")
      (footprint "eagle-import:R0603")
      (libsource (lib "eagle-import") (part "RB"))
    )
    (comp (ref "R157")
      (value "1k")
      (footprint "eagle-import:R0603")
      (libsource (lib "eagle-import") (part "RB"))
    )
    (comp (ref "R158")
      (value "1k")
      (footprint "eagle-import:R0603")
      (libsource (lib "eagle-import") (part "RB"))
    )
    (comp (ref "R159")
      (value "1k")
      (footprint "eagle-import:R0603")
      (libsource (lib "eagle-import") (part "RB"))
    )
    (comp (ref "R160")
      (value "1k")
      (footprint "eagle-import:R0603")
      (libsource (lib "eagle-import") (part "RB"))
    )
    (comp (ref "R161")
      (value "1k")
      (footprint "eagle-import:R0603")
      (libsource (lib "eagle-import") (part "RB"))
    )
    (comp (ref "R162")
      (value "1k")
      (footprint "eagle-import:R0603")
      (libsource (lib "eagle-import") (part "RB"))
    )
    (comp (ref "R163")
      (value "1k")
      (footprint "eagle-import:R0603")
      (libsource (lib "eagle-import") (part "RB"))
    )
    (comp (ref "R164")
      (value "1k")
      (footprint "eagle-import:R0603")
      (libsource (lib "eagle-import") (part "RB"))
    )
    (comp (ref "R165")
      (value "1k")
      (footprint "eagle-import:R0603")
      (libsource (lib "eagle-import") (part "RB"))
    )
    (comp (ref "R166")
      (value "1k")
      (footprint "eagle-import:R0603")
      (libsource (lib "eagle-import") (part "RB"))
    )
    (comp (ref "R167")
      (value "1k")
      (footprint "eagle-import:R0603")
      (libsource (lib "eagle-import") (part "RB"))
    )
    (comp (ref "R173")
      (value "1k")
      (footprint "eagle-import:R0603")
      (libsource (lib "eagle-import") (part "RB"))
    )
    (comp (ref "R174")
      (value "1k")
      (footprint "eagle-import:R0603")
      (libsource (lib "eagle-import") (part "RB"))
    )
    (comp (ref "R175")
      (value "1k")
      (footprint "eagle-import:R0603")
      (libsource (lib "eagle-import") (part "RB"))
    )
    (comp (ref "R176")
      (value "1k")
      (footprint "eagle-import:R0603")
      (libsource (lib "eagle-import") (part "RB"))
    )
    (comp (ref "R177")
      (value "1k")
      (footprint "eagle-import:R0603")
      (libsource (lib "eagle-import") (part "RB"))
    )
    (comp (ref "R178")
      (value "1k")
      (footprint "eagle-import:R0603")
      (libsource (lib "eagle-import") (part "RB"))
    )
    (comp (ref "R179")
      (value "1k")
      (footprint "eagle-import:R0603")
      (libsource (lib "eagle-import") (part "RB"))
    )
    (comp (ref "R180")
      (value "1k")
      (footprint "eagle-import:R0603")
      (libsource (lib "eagle-import") (part "RB"))
    )
    (comp (ref "R181")
      (value "1k")
      (footprint "eagle-import:R0603")
      (libsource (lib "eagle-import") (part "RB"))
    )
    (comp (ref "R182")
      (value "1k")
      (footprint "eagle-import:R0603")
      (libsource (lib "eagle-import") (part "RB"))
    )
    (comp (ref "R184")
      (value "1k")
      (footprint "eagle-import:R0603")
      (libsource (lib "eagle-import") (part "RB"))
    )
    (comp (ref "U2")
      (value "PCA9685")
      (footprint "eagle-import:TSSOP28")
      (libsource (lib "eagle-import") (part "PCA9685"))
    )
    (comp (ref "U3")
      (value "PCA9685")
      (footprint "eagle-import:TSSOP28")
      (libsource (lib "eagle-import") (part "PCA9685"))
    )
    (comp (ref "U4")
      (value "PCA9685")
      (footprint "eagle-import:TSSOP28")
      (libsource (lib "eagle-import") (part "PCA9685"))
    )
    (comp (ref "U5")
      (value "PCA9685")
      (footprint "eagle-import:TSSOP28")
      (libsource (lib "eagle-import") (part "PCA9685"))
    )
    (comp (ref "U6")
      (value "PCA9685")
      (footprint "eagle-import:TSSOP28")
      (libsource (lib "eagle-import") (part "PCA9685"))
    )
    (comp (ref "BANDCV1")
      (value "PJ301-M12")
      (footprint "eagle-import:PJ301M-12-FIX")
      (libsource (lib "eagle-import") (part "JACK-MONO-SWM2"))
    )
    (comp (ref "BANDCV2")
      (value "PJ301-M12")
      (footprint "eagle-import:PJ301M-12-FIX")
      (libsource (lib "eagle-import") (part "JACK-MONO-SWM2"))
    )
    (comp (ref "BANDCV3")
      (value "PJ301-M12")
      (footprint "eagle-import:PJ301M-12-FIX")
      (libsource (lib "eagle-import") (part "JACK-MONO-SWM2"))
    )
    (comp (ref "BANDCV4")
      (value "PJ301-M12")
      (footprint "eagle-import:PJ301M-12-FIX")
      (libsource (lib "eagle-import") (part "JACK-MONO-SWM2"))
    )
    (comp (ref "BANDCV5")
      (value "PJ301-M12")
      (footprint "eagle-import:PJ301M-12-FIX")
      (libsource (lib "eagle-import") (part "JACK-MONO-SWM2"))
    )
    (comp (ref "BANDCV6")
      (value "PJ301-M12")
      (footprint "eagle-import:PJ301M-12-FIX")
      (libsource (lib "eagle-import") (part "JACK-MONO-SWM2"))
    )
    (comp (ref "C13")
      (value "0.1uF")
      (footprint "eagle-import:C0603")
      (libsource (lib "eagle-import") (part "CB"))
    )
    (comp (ref "C15")
      (value "0.1uF")
      (footprint "eagle-import:C0603")
      (libsource (lib "eagle-import") (part "CB"))
    )
    (comp (ref "C16")
      (value "0.1uF")
      (footprint "eagle-import:C0603")
      (libsource (lib "eagle-import") (part "CB"))
    )
    (comp (ref "C30")
      (value "0.1uF")
      (footprint "eagle-import:C0603")
      (libsource (lib "eagle-import") (part "CB"))
    )
    (comp (ref "C34")
      (value "0.1uF")
      (footprint "eagle-import:C0603")
      (libsource (lib "eagle-import") (part "CB"))
    )
    (comp (ref "C35")
      (value "0.1uF")
      (footprint "eagle-import:C0603")
      (libsource (lib "eagle-import") (part "CB"))
    )
    (comp (ref "C36")
      (value "0.1uF")
      (footprint "eagle-import:C0603")
      (libsource (lib "eagle-import") (part "CB"))
    )
    (comp (ref "C37")
      (value "0.1uF")
      (footprint "eagle-import:C0603")
      (libsource (lib "eagle-import") (part "CB"))
    )
    (comp (ref "C38")
      (value "0.1uF")
      (footprint "eagle-import:C0603")
      (libsource (lib "eagle-import") (part "CB"))
    )
    (comp (ref "C39")
      (value "0.1uF")
      (footprint "eagle-import:C0603")
      (libsource (lib "eagle-import") (part "CB"))
    )
    (comp (ref "C40")
      (value "0.1uF")
      (footprint "eagle-import:C0603")
      (libsource (lib "eagle-import") (part "CB"))
    )
    (comp (ref "C42")
      (value "0.1uF")
      (footprint "eagle-import:C0603")
      (libsource (lib "eagle-import") (part "CB"))
    )
    (comp (ref "C65")
      (value "0.1uF")
      (footprint "eagle-import:C0603")
      (libsource (lib "eagle-import") (part "CB"))
    )
    (comp (ref "C66")
      (value "0.1uF")
      (footprint "eagle-import:C0603")
      (libsource (lib "eagle-import") (part "CB"))
    )
    (comp (ref "C67")
      (value "0.1uF")
      (footprint "eagle-import:C0603")
      (libsource (lib "eagle-import") (part "CB"))
    )
    (comp (ref "C68")
      (value "0.1uF")
      (footprint "eagle-import:C0603")
      (libsource (lib "eagle-import") (part "CB"))
    )
    (comp (ref "C69")
      (value "0.1uF")
      (footprint "eagle-import:C0603")
      (libsource (lib "eagle-import") (part "CB"))
    )
    (comp (ref "C70")
      (value "0.1uF")
      (footprint "eagle-import:C0603")
      (libsource (lib "eagle-import") (part "CB"))
    )
    (comp (ref "D5")
      (value "BAT54S")
      (footprint "eagle-import:SOT23")
      (libsource (lib "eagle-import") (part "DIODE-DUAL"))
    )
    (comp (ref "D6")
      (value "BAT54S")
      (footprint "eagle-import:SOT23")
      (libsource (lib "eagle-import") (part "DIODE-DUAL"))
    )
    (comp (ref "D7")
      (value "BAT54S")
      (footprint "eagle-import:SOT23")
      (libsource (lib "eagle-import") (part "DIODE-DUAL"))
    )
    (comp (ref "D8")
      (value "BAT54S")
      (footprint "eagle-import:SOT23")
      (libsource (lib "eagle-import") (part "DIODE-DUAL"))
    )
    (comp (ref "D9")
      (value "BAT54S")
      (footprint "eagle-import:SOT23")
      (libsource (lib "eagle-import") (part "DIODE-DUAL"))
    )
    (comp (ref "D10")
      (value "BAT54S")
      (footprint "eagle-import:SOT23")
      (libsource (lib "eagle-import") (part "DIODE-DUAL"))
    )
    (comp (ref "ENV1")
      (value "PJ301-M12")
      (footprint "eagle-import:PJ301M-12-FIX")
      (libsource (lib "eagle-import") (part "JACK-MONO-SWM2"))
    )
    (comp (ref "ENV2")
      (value "PJ301-M12")
      (footprint "eagle-import:PJ301M-12-FIX")
      (libsource (lib "eagle-import") (part "JACK-MONO-SWM2"))
    )
    (comp (ref "ENV3")
      (value "PJ301-M12")
      (footprint "eagle-import:PJ301M-12-FIX")
      (libsource (lib "eagle-import") (part "JACK-MONO-SWM2"))
    )
    (comp (ref "ENV4")
      (value "PJ301-M12")
      (footprint "eagle-import:PJ301M-12-FIX")
      (libsource (lib "eagle-import") (part "JACK-MONO-SWM2"))
    )
    (comp (ref "ENV5")
      (value "PJ301-M12")
      (footprint "eagle-import:PJ301M-12-FIX")
      (libsource (lib "eagle-import") (part "JACK-MONO-SWM2"))
    )
    (comp (ref "ENV6")
      (value "PJ301-M12")
      (footprint "eagle-import:PJ301M-12-FIX")
      (libsource (lib "eagle-import") (part "JACK-MONO-SWM2"))
    )
    (comp (ref "IC2")
      (value "TL082")
      (footprint "eagle-import:TSSOP8")
      (libsource (lib "eagle-import") (part "OPAMP-2TL072T"))
    )
    (comp (ref "IC3")
      (value "TL082")
      (footprint "eagle-import:TSSOP8")
      (libsource (lib "eagle-import") (part "OPAMP-2TL072T"))
    )
    (comp (ref "IC4")
      (value "TL082")
      (footprint "eagle-import:TSSOP8")
      (libsource (lib "eagle-import") (part "OPAMP-2TL072T"))
    )
    (comp (ref "IC9")
      (value "TL082")
      (footprint "eagle-import:TSSOP8")
      (libsource (lib "eagle-import") (part "OPAMP-2TL072T"))
    )
    (comp (ref "LOCK1")
      (value "WHITE-MOM")
      (footprint "eagle-import:BUTTON-LED-PB61303")
      (libsource (lib "eagle-import") (part "BUTTON-LED"))
    )
    (comp (ref "LOCK2")
      (value "WHITE-MOM")
      (footprint "eagle-import:BUTTON-LED-PB61303")
      (libsource (lib "eagle-import") (part "BUTTON-LED"))
    )
    (comp (ref "LOCK3")
      (value "WHITE-MOM")
      (footprint "eagle-import:BUTTON-LED-PB61303")
      (libsource (lib "eagle-import") (part "BUTTON-LED"))
    )
    (comp (ref "LOCK4")
      (value "WHITE-MOM")
      (footprint "eagle-import:BUTTON-LED-PB61303")
      (libsource (lib "eagle-import") (part "BUTTON-LED"))
    )
    (comp (ref "LOCK5")
      (value "WHITE-MOM")
      (footprint "eagle-import:BUTTON-LED-PB61303")
      (libsource (lib "eagle-import") (part "BUTTON-LED"))
    )
    (comp (ref "LOCK6")
      (value "WHITE-MOM")
      (footprint "eagle-import:BUTTON-LED-PB61303")
      (libsource (lib "eagle-import") (part "BUTTON-LED"))
    )
    (comp (ref "R8")
      (value "1k")
      (footprint "eagle-import:R0603")
      (libsource (lib "eagle-import") (part "malekko main_RB"))
    )
    (comp (ref "R9")
      (value "10k")
      (footprint "eagle-import:R0603")
      (libsource (lib "eagle-import") (part "RB"))
    )
    (comp (ref "R21")
      (value "1k")
      (footprint "eagle-import:R0603")
      (libsource (lib "eagle-import") (part "RB"))
    )
    (comp (ref "R22")
      (value "1k")
      (footprint "eagle-import:R0603")
      (libsource (lib "eagle-import") (part "RB"))
    )
    (comp (ref "R23")
      (value "1k")
      (footprint "eagle-import:R0603")
      (libsource (lib "eagle-import") (part "RB"))
    )
    (comp (ref "R24")
      (value "1k")
      (footprint "eagle-import:R0603")
      (libsource (lib "eagle-import") (part "RB"))
    )
    (comp (ref "R31")
      (value "1k")
      (footprint "eagle-import:R0603")
      (libsource (lib "eagle-import") (part "malekko main_RB"))
    )
    (comp (ref "R32")
      (value "10k")
      (footprint "eagle-import:R0603")
      (libsource (lib "eagle-import") (part "RB"))
    )
    (comp (ref "R34")
      (value "1k")
      (footprint "eagle-import:R0603")
      (libsource (lib "eagle-import") (part "malekko main_RB"))
    )
    (comp (ref "R35")
      (value "1k")
      (footprint "eagle-import:R0603")
      (libsource (lib "eagle-import") (part "malekko main_RB"))
    )
    (comp (ref "R36")
      (value "1k")
      (footprint "eagle-import:R0603")
      (libsource (lib "eagle-import") (part "malekko main_RB"))
    )
    (comp (ref "R37")
      (value "1k")
      (footprint "eagle-import:R0603")
      (libsource (lib "eagle-import") (part "malekko main_RB"))
    )
    (comp (ref "R38")
      (value "100k")
      (footprint "eagle-import:R0603")
      (libsource (lib "eagle-import") (part "RB"))
    )
    (comp (ref "R39")
      (value "100k")
      (footprint "eagle-import:R0603")
      (libsource (lib "eagle-import") (part "RB"))
    )
    (comp (ref "R40")
      (value "100k")
      (footprint "eagle-import:R0603")
      (libsource (lib "eagle-import") (part "RB"))
    )
    (comp (ref "R41")
      (value "100k")
      (footprint "eagle-import:R0603")
      (libsource (lib "eagle-import") (part "RB"))
    )
    (comp (ref "R42")
      (value "100k")
      (footprint "eagle-import:R0603")
      (libsource (lib "eagle-import") (part "RB"))
    )
    (comp (ref "R43")
      (value "100k")
      (footprint "eagle-import:R0603")
      (libsource (lib "eagle-import") (part "RB"))
    )
    (comp (ref "R44")
      (value "330")
      (footprint "eagle-import:R0603")
      (libsource (lib "eagle-import") (part "RB"))
    )
    (comp (ref "R45")
      (value "330")
      (footprint "eagle-import:R0603")
      (libsource (lib "eagle-import") (part "RB"))
    )
    (comp (ref "R46")
      (value "1k")
      (footprint "eagle-import:R0603")
      (libsource (lib "eagle-import") (part "RB"))
    )
    (comp (ref "R47")
      (value "1k")
      (footprint "eagle-import:R0603")
      (libsource (lib "eagle-import") (part "RB"))
    )
    (comp (ref "R48")
      (value "1k")
      (footprint "eagle-import:R0603")
      (libsource (lib "eagle-import") (part "RB"))
    )
    (comp (ref "R49")
      (value "1k")
      (footprint "eagle-import:R0603")
      (libsource (lib "eagle-import") (part "RB"))
    )
    (comp (ref "R50")
      (value "330")
      (footprint "eagle-import:R0603")
      (libsource (lib "eagle-import") (part "RB"))
    )
    (comp (ref "R51")
      (value "1k")
      (footprint "eagle-import:R0603")
      (libsource (lib "eagle-import") (part "malekko main_RB"))
    )
    (comp (ref "R52")
      (value "10k")
      (footprint "eagle-import:R0603")
      (libsource (lib "eagle-import") (part "RB"))
    )
    (comp (ref "R53")
      (value "1k")
      (footprint "eagle-import:R0603")
      (libsource (lib "eagle-import") (part "malekko main_RB"))
    )
    (comp (ref "R54")
      (value "10k")
      (footprint "eagle-import:R0603")
      (libsource (lib "eagle-import") (part "RB"))
    )
    (comp (ref "R55")
      (value "1k")
      (footprint "eagle-import:R0603")
      (libsource (lib "eagle-import") (part "malekko main_RB"))
    )
    (comp (ref "R56")
      (value "10k")
      (footprint "eagle-import:R0603")
      (libsource (lib "eagle-import") (part "RB"))
    )
    (comp (ref "R57")
      (value "1k")
      (footprint "eagle-import:R0603")
      (libsource (lib "eagle-import") (part "malekko main_RB"))
    )
    (comp (ref "R58")
      (value "10k")
      (footprint "eagle-import:R0603")
      (libsource (lib "eagle-import") (part "RB"))
    )
    (comp (ref "R68")
      (value "49k")
      (footprint "eagle-import:R0603")
      (libsource (lib "eagle-import") (part "malekko main_RB"))
    )
    (comp (ref "R69")
      (value "49k")
      (footprint "eagle-import:R0603")
      (libsource (lib "eagle-import") (part "malekko main_RB"))
    )
    (comp (ref "R70")
      (value "49k")
      (footprint "eagle-import:R0603")
      (libsource (lib "eagle-import") (part "malekko main_RB"))
    )
    (comp (ref "R71")
      (value "49k")
      (footprint "eagle-import:R0603")
      (libsource (lib "eagle-import") (part "malekko main_RB"))
    )
    (comp (ref "R72")
      (value "49k")
      (footprint "eagle-import:R0603")
      (libsource (lib "eagle-import") (part "malekko main_RB"))
    )
    (comp (ref "R73")
      (value "49k")
      (footprint "eagle-import:R0603")
      (libsource (lib "eagle-import") (part "malekko main_RB"))
    )
    (comp (ref "R80")
      (value "100k")
      (footprint "eagle-import:R0603")
      (libsource (lib "eagle-import") (part "malekko main_RB"))
    )
    (comp (ref "R81")
      (value "100k")
      (footprint "eagle-import:R0603")
      (libsource (lib "eagle-import") (part "malekko main_RB"))
    )
    (comp (ref "R82")
      (value "68k")
      (footprint "eagle-import:R0603")
      (libsource (lib "eagle-import") (part "malekko main_RB"))
    )
    (comp (ref "R83")
      (value "68k")
      (footprint "eagle-import:R0603")
      (libsource (lib "eagle-import") (part "malekko main_RB"))
    )
    (comp (ref "R84")
      (value "100k")
      (footprint "eagle-import:R0603")
      (libsource (lib "eagle-import") (part "malekko main_RB"))
    )
    (comp (ref "R85")
      (value "68k")
      (footprint "eagle-import:R0603")
      (libsource (lib "eagle-import") (part "malekko main_RB"))
    )
    (comp (ref "R86")
      (value "100k")
      (footprint "eagle-import:R0603")
      (libsource (lib "eagle-import") (part "malekko main_RB"))
    )
    (comp (ref "R87")
      (value "68k")
      (footprint "eagle-import:R0603")
      (libsource (lib "eagle-import") (part "malekko main_RB"))
    )
    (comp (ref "R88")
      (value "100k")
      (footprint "eagle-import:R0603")
      (libsource (lib "eagle-import") (part "malekko main_RB"))
    )
    (comp (ref "R89")
      (value "68k")
      (footprint "eagle-import:R0603")
      (libsource (lib "eagle-import") (part "malekko main_RB"))
    )
    (comp (ref "R90")
      (value "100k")
      (footprint "eagle-import:R0603")
      (libsource (lib "eagle-import") (part "malekko main_RB"))
    )
    (comp (ref "R91")
      (value "68k")
      (footprint "eagle-import:R0603")
      (libsource (lib "eagle-import") (part "malekko main_RB"))
    )
    (comp (ref "R115")
      (value "1k")
      (footprint "eagle-import:R0603")
      (libsource (lib "eagle-import") (part "malekko main_RB"))
    )
    (comp (ref "R116")
      (value "1k")
      (footprint "eagle-import:R0603")
      (libsource (lib "eagle-import") (part "malekko main_RB"))
    )
    (comp (ref "R117")
      (value "1k")
      (footprint "eagle-import:R0603")
      (libsource (lib "eagle-import") (part "RB"))
    )
    (comp (ref "R118")
      (value "330")
      (footprint "eagle-import:R0603")
      (libsource (lib "eagle-import") (part "RB"))
    )
    (comp (ref "R119")
      (value "1k")
      (footprint "eagle-import:R0603")
      (libsource (lib "eagle-import") (part "RB"))
    )
    (comp (ref "R120")
      (value "330")
      (footprint "eagle-import:R0603")
      (libsource (lib "eagle-import") (part "RB"))
    )
    (comp (ref "R121")
      (value "1k")
      (footprint "eagle-import:R0603")
      (libsource (lib "eagle-import") (part "RB"))
    )
    (comp (ref "R122")
      (value "330")
      (footprint "eagle-import:R0603")
      (libsource (lib "eagle-import") (part "RB"))
    )
    (comp (ref "R123")
      (value "1k")
      (footprint "eagle-import:R0603")
      (libsource (lib "eagle-import") (part "RB"))
    )
    (comp (ref "SLIDE1")
      (value "100k")
      (footprint "eagle-import:POT-SLIDER-ALPHA-RA2045F-20")
      (libsource (lib "eagle-import") (part "POT-LED"))
    )
    (comp (ref "SLIDE2")
      (value "100k")
      (footprint "eagle-import:POT-SLIDER-ALPHA-RA2045F-20")
      (libsource (lib "eagle-import") (part "POT-LED"))
    )
    (comp (ref "SLIDE3")
      (value "100k")
      (footprint "eagle-import:POT-SLIDER-ALPHA-RA2045F-20")
      (libsource (lib "eagle-import") (part "POT-LED"))
    )
    (comp (ref "SLIDE4")
      (value "100k")
      (footprint "eagle-import:POT-SLIDER-ALPHA-RA2045F-20")
      (libsource (lib "eagle-import") (part "POT-LED"))
    )
    (comp (ref "SLIDE5")
      (value "100k")
      (footprint "eagle-import:POT-SLIDER-ALPHA-RA2045F-20")
      (libsource (lib "eagle-import") (part "POT-LED"))
    )
    (comp (ref "SLIDE6")
      (value "100k")
      (footprint "eagle-import:POT-SLIDER-ALPHA-RA2045F-20")
      (libsource (lib "eagle-import") (part "POT-LED"))
    )
    (comp (ref "AGND")
      (value "PAD-06")
      (footprint "eagle-import:PAD-06")
      (libsource (lib "eagle-import") (part "PAD-06"))
    )
    (comp (ref "C3")
      (value "0.1uF")
      (footprint "eagle-import:C0603")
      (libsource (lib "eagle-import") (part "CB"))
    )
    (comp (ref "C4")
      (value "47uF")
      (footprint "eagle-import:C-POL-5")
      (libsource (lib "eagle-import") (part "C-POL5"))
    )
    (comp (ref "C7")
      (value "47uF")
      (footprint "eagle-import:C-POL-5")
      (libsource (lib "eagle-import") (part "C-POL5"))
    )
    (comp (ref "C8")
      (value "47uF")
      (footprint "eagle-import:C-POL-5")
      (libsource (lib "eagle-import") (part "C-POL5"))
    )
    (comp (ref "C10")
      (value "0.1uF")
      (footprint "eagle-import:C0603")
      (libsource (lib "eagle-import") (part "CB"))
    )
    (comp (ref "C17")
      (value "0.1uF")
      (footprint "eagle-import:C0603")
      (libsource (lib "eagle-import") (part "CB"))
    )
    (comp (ref "C31")
      (value "47uF")
      (footprint "eagle-import:C-POL-5")
      (libsource (lib "eagle-import") (part "C-POL5"))
    )
    (comp (ref "C41")
      (value "0.1uF")
      (footprint "eagle-import:C0603")
      (libsource (lib "eagle-import") (part "CB"))
    )
    (comp (ref "C46")
      (value "0.1uF")
      (footprint "eagle-import:C0603")
      (libsource (lib "eagle-import") (part "CB"))
    )
    (comp (ref "C47")
      (value "47uF")
      (footprint "eagle-import:C-POL-5")
      (libsource (lib "eagle-import") (part "C-POL5"))
    )
    (comp (ref "C56")
      (value "47uF")
      (footprint "eagle-import:C-POL-5")
      (libsource (lib "eagle-import") (part "C-POL5"))
    )
    (comp (ref "C57")
      (value "0.1uF")
      (footprint "eagle-import:C0603")
      (libsource (lib "eagle-import") (part "CB"))
    )
    (comp (ref "C58")
      (value "47uF")
      (footprint "eagle-import:C-POL-5")
      (libsource (lib "eagle-import") (part "C-POL5"))
    )
    (comp (ref "C73")
      (value "0.1uF")
      (footprint "eagle-import:C0603")
      (libsource (lib "eagle-import") (part "CB"))
    )
    (comp (ref "C74")
      (value "0.1uF")
      (footprint "eagle-import:C0603")
      (libsource (lib "eagle-import") (part "CB"))
    )
    (comp (ref "C75")
      (value "0.1uF")
      (footprint "eagle-import:C0603")
      (libsource (lib "eagle-import") (part "CB"))
    )
    (comp (ref "C76")
      (value "0.1uF")
      (footprint "eagle-import:C0603")
      (libsource (lib "eagle-import") (part "CB"))
    )
    (comp (ref "C77")
      (value "0.1uF")
      (footprint "eagle-import:C0603")
      (libsource (lib "eagle-import") (part "CB"))
    )
    (comp (ref "C78")
      (value "0.1uF")
      (footprint "eagle-import:C0603")
      (libsource (lib "eagle-import") (part "CB"))
    )
    (comp (ref "C79")
      (value "0.1uF")
      (footprint "eagle-import:C0603")
      (libsource (lib "eagle-import") (part "CB"))
    )
    (comp (ref "C80")
      (value "0.1uF")
      (footprint "eagle-import:C0603")
      (libsource (lib "eagle-import") (part "CB"))
    )
    (comp (ref "D13")
      (value "B140-E3")
      (footprint "eagle-import:SMA")
      (libsource (lib "eagle-import") (part "DA"))
    )
    (comp (ref "D19")
      (value "B140-E3")
      (footprint "eagle-import:SMA")
      (libsource (lib "eagle-import") (part "DA"))
    )
    (comp (ref "DGND")
      (value "PAD-06")
      (footprint "eagle-import:PAD-06")
      (libsource (lib "eagle-import") (part "PAD-06"))
    )
    (comp (ref "IC1")
      (value "TL082")
      (footprint "eagle-import:TSSOP8")
      (libsource (lib "eagle-import") (part "OPAMP-2TL072T"))
    )
    (comp (ref "IC5")
      (value "TL082")
      (footprint "eagle-import:TSSOP8")
      (libsource (lib "eagle-import") (part "OPAMP-2TL072T"))
    )
    (comp (ref "IC7")
      (value "LD1117-33")
      (footprint "eagle-import:SOT223")
      (libsource (lib "eagle-import") (part "LD1117S50TR"))
    )
    (comp (ref "IC8")
      (value "TL082")
      (footprint "eagle-import:TSSOP8")
      (libsource (lib "eagle-import") (part "OPAMP-2TL072T"))
    )
    (comp (ref "IC10")
      (value "LD1117-33")
      (footprint "eagle-import:SOT223")
      (libsource (lib "eagle-import") (part "LD1117S50TR"))
    )
    (comp (ref "L1")
      (value "BEAD")
      (footprint "eagle-import:0603")
      (libsource (lib "eagle-import") (part "LB"))
    )
    (comp (ref "L2")
      (value "BEAD")
      (footprint "eagle-import:0603")
      (libsource (lib "eagle-import") (part "LB"))
    )
    (comp (ref "POWER")
      (value "HEADER-2X8-SMT")
      (footprint "eagle-import:HEADER-2X8-SMT-SHROUDED")
      (libsource (lib "eagle-import") (part "HEADER-2X8SHRD"))
    )
    (comp (ref "V-SEL")
      (value "HEADER-1X3-TH")
      (footprint "eagle-import:HEADER-1X3-TH")
      (libsource (lib "eagle-import") (part "HEADER-1X3"))
    )
    (comp (ref "V1")
      (value "KA78L05")
      (footprint "eagle-import:SOT89")
      (libsource (lib "eagle-import") (part "VREG-KA78LXX"))
    )
    (comp (ref "VR4")
      (value "78E-3.3-0.5")
      (footprint "eagle-import:RECOM-DCDC")
      (libsource (lib "eagle-import") (part "VREG-DCDC"))
    )
    (comp (ref "C12")
      (value "0.1uF")
      (footprint "eagle-import:C0603")
      (libsource (lib "eagle-import") (part "CB"))
    )
    (comp (ref "C22")
      (value "0.1uF")
      (footprint "eagle-import:C0603")
      (libsource (lib "eagle-import") (part "CB"))
    )
    (comp (ref "C23")
      (value "0.1uF")
      (footprint "eagle-import:C0603")
      (libsource (lib "eagle-import") (part "CB"))
    )
    (comp (ref "C24")
      (value "0.1uF")
      (footprint "eagle-import:C0603")
      (libsource (lib "eagle-import") (part "CB"))
    )
    (comp (ref "C25")
      (value "0.1uF")
      (footprint "eagle-import:C0603")
      (libsource (lib "eagle-import") (part "CB"))
    )
    (comp (ref "C26")
      (value "0.1uF")
      (footprint "eagle-import:C0603")
      (libsource (lib "eagle-import") (part "CB"))
    )
    (comp (ref "C27")
      (value "0.1uF")
      (footprint "eagle-import:C0603")
      (libsource (lib "eagle-import") (part "CB"))
    )
    (comp (ref "C28")
      (value "2.2uF")
      (footprint "eagle-import:C0603")
      (libsource (lib "eagle-import") (part "CB"))
    )
    (comp (ref "C29")
      (value "2.2uF")
      (footprint "eagle-import:C0603")
      (libsource (lib "eagle-import") (part "CB"))
    )
    (comp (ref "C32")
      (value "18pF")
      (footprint "eagle-import:C0603")
      (libsource (lib "eagle-import") (part "CB"))
    )
    (comp (ref "C33")
      (value "18pF")
      (footprint "eagle-import:C0603")
      (libsource (lib "eagle-import") (part "CB"))
    )
    (comp (ref "C64")
      (value "0.1uF")
      (footprint "eagle-import:C0603")
      (libsource (lib "eagle-import") (part "CB"))
    )
    (comp (ref "PG2")
      (value "PAD-06")
      (footprint "eagle-import:PAD-06")
      (libsource (lib "eagle-import") (part "PAD-06"))
    )
    (comp (ref "PG3")
      (value "PAD-06")
      (footprint "eagle-import:PAD-06")
      (libsource (lib "eagle-import") (part "PAD-06"))
    )
    (comp (ref "PG5")
      (value "PAD-06")
      (footprint "eagle-import:PAD-06")
      (libsource (lib "eagle-import") (part "PAD-06"))
    )
    (comp (ref "PG6")
      (value "PAD-06")
      (footprint "eagle-import:PAD-06")
      (libsource (lib "eagle-import") (part "PAD-06"))
    )
    (comp (ref "R26")
      (value "10k")
      (footprint "eagle-import:R0603")
      (libsource (lib "eagle-import") (part "malekko main_RB"))
    )
    (comp (ref "R27")
      (value "22")
      (footprint "eagle-import:R0603")
      (libsource (lib "eagle-import") (part "RB"))
    )
    (comp (ref "R28")
      (value "22")
      (footprint "eagle-import:R0603")
      (libsource (lib "eagle-import") (part "RB"))
    )
    (comp (ref "S0")
      (value "BUTTON-TACT")
      (footprint "eagle-import:BUTTON-TACT-SKQG")
      (libsource (lib "eagle-import") (part "BUTTON-TACT"))
    )
    (comp (ref "S1")
      (value "BUTTON-TACT")
      (footprint "eagle-import:BUTTON-TACT-SKQG")
      (libsource (lib "eagle-import") (part "BUTTON-TACT"))
    )
    (comp (ref "SWD")
      (value "HEADER-1X4")
      (footprint "eagle-import:HEADER-1X4-TH")
      (libsource (lib "eagle-import") (part "HEADER-1X4"))
    )
    (comp (ref "U$1")
      (value "USB-MINIB-5PIN")
      (footprint "eagle-import:USB-MINIB")
      (libsource (lib "eagle-import") (part "USB-MINIB-5PIN"))
    )
    (comp (ref "U7")
      (value "STM32F427ZG")
      (footprint "eagle-import:LQFP144")
      (libsource (lib "eagle-import") (part "STM32F429ZI"))
    )
    (comp (ref "X1")
      (value "8MHz")
      (footprint "eagle-import:HC-49_US")
      (libsource (lib "eagle-import") (part "CRYSTALD"))
    )
    (comp (ref "AGND-OPT")
      (value "PAD-06")
      (footprint "eagle-import:PAD-06")
      (libsource (lib "eagle-import") (part "PAD-06"))
    )
    (comp (ref "C1")
      (value "10uF/10V")
      (footprint "eagle-import:C0603")
      (libsource (lib "eagle-import") (part "CB"))
    )
    (comp (ref "C2")
      (value "10uF/10V")
      (footprint "eagle-import:C0603")
      (libsource (lib "eagle-import") (part "CB"))
    )
    (comp (ref "C5")
      (value "18pF")
      (footprint "eagle-import:C0603")
      (libsource (lib "eagle-import") (part "CB"))
    )
    (comp (ref "C6")
      (value "18pF")
      (footprint "eagle-import:C0603")
      (libsource (lib "eagle-import") (part "CB"))
    )
    (comp (ref "C11")
      (value "0.1uF")
      (footprint "eagle-import:C0603")
      (libsource (lib "eagle-import") (part "CB"))
    )
    (comp (ref "C14")
      (value "2.2uF")
      (footprint "eagle-import:C0603")
      (libsource (lib "eagle-import") (part "CB"))
    )
    (comp (ref "C18")
      (value "0.1uF")
      (footprint "eagle-import:C0603")
      (libsource (lib "eagle-import") (part "CB"))
    )
    (comp (ref "C20")
      (value "0.1uF")
      (footprint "eagle-import:C0603")
      (libsource (lib "eagle-import") (part "CB"))
    )
    (comp (ref "C21")
      (value "47uF")
      (footprint "eagle-import:C-POL-5")
      (libsource (lib "eagle-import") (part "C-POL5"))
    )
    (comp (ref "C52")
      (value "10uF/10V")
      (footprint "eagle-import:C0603")
      (libsource (lib "eagle-import") (part "CB"))
    )
    (comp (ref "C53")
      (value "10uF/10V")
      (footprint "eagle-import:C0603")
      (libsource (lib "eagle-import") (part "CB"))
    )
    (comp (ref "C54")
      (value "18pF")
      (footprint "eagle-import:C0603")
      (libsource (lib "eagle-import") (part "CB"))
    )
    (comp (ref "C55")
      (value "18pF")
      (footprint "eagle-import:C0603")
      (libsource (lib "eagle-import") (part "CB"))
    )
    (comp (ref "IN-1")
      (value "PJ301-M12")
      (footprint "eagle-import:PJ301M-12-FIX")
      (libsource (lib "eagle-import") (part "JACK-MONO-SWM2"))
    )
    (comp (ref "IN-2")
      (value "PJ301-M12")
      (footprint "eagle-import:PJ301M-12-FIX")
      (libsource (lib "eagle-import") (part "JACK-MONO-SWM2"))
    )
    (comp (ref "OUT-1")
      (value "PJ301-M12")
      (footprint "eagle-import:PJ301M-12-FIX")
      (libsource (lib "eagle-import") (part "JACK-MONO-SWM2"))
    )
    (comp (ref "OUT-2")
      (value "PJ301-M12")
      (footprint "eagle-import:PJ301M-12-FIX")
      (libsource (lib "eagle-import") (part "JACK-MONO-SWM2"))
    )
    (comp (ref "R1")
      (value "1k")
      (footprint "eagle-import:R0603")
      (libsource (lib "eagle-import") (part "malekko main_RB"))
    )
    (comp (ref "R2")
      (value "1k")
      (footprint "eagle-import:R0603")
      (libsource (lib "eagle-import") (part "malekko main_RB"))
    )
    (comp (ref "R3")
      (value "1k")
      (footprint "eagle-import:R0603")
      (libsource (lib "eagle-import") (part "malekko main_RB"))
    )
    (comp (ref "R4")
      (value "1k")
      (footprint "eagle-import:R0603")
      (libsource (lib "eagle-import") (part "malekko main_RB"))
    )
    (comp (ref "R16")
      (value "4k7")
      (footprint "eagle-import:R0603")
      (libsource (lib "eagle-import") (part "malekko main_RB"))
    )
    (comp (ref "R25")
      (value "4k7")
      (footprint "eagle-import:R0603")
      (libsource (lib "eagle-import") (part "malekko main_RB"))
    )
    (comp (ref "R61")
      (value "100k")
      (footprint "eagle-import:R0603")
      (libsource (lib "eagle-import") (part "malekko main_RB"))
    )
    (comp (ref "R62")
      (value "100k")
      (footprint "eagle-import:R0603")
      (libsource (lib "eagle-import") (part "malekko main_RB"))
    )
    (comp (ref "R63")
      (value "10k")
      (footprint "eagle-import:R0603")
      (libsource (lib "eagle-import") (part "malekko main_RB"))
    )
    (comp (ref "R64")
      (value "10k")
      (footprint "eagle-import:R0603")
      (libsource (lib "eagle-import") (part "malekko main_RB"))
    )
    (comp (ref "R92")
      (value "100k")
      (footprint "eagle-import:R0603")
      (libsource (lib "eagle-import") (part "malekko main_RB"))
    )
    (comp (ref "R93")
      (value "100k")
      (footprint "eagle-import:R0603")
      (libsource (lib "eagle-import") (part "malekko main_RB"))
    )
    (comp (ref "R183")
      (value "49k")
      (footprint "eagle-import:R0603")
      (libsource (lib "eagle-import") (part "malekko main_RB"))
    )
    (comp (ref "R185")
      (value "10k")
      (footprint "eagle-import:R0603")
      (libsource (lib "eagle-import") (part "malekko main_RB"))
    )
    (comp (ref "R186")
      (value "10k")
      (footprint "eagle-import:R0603")
      (libsource (lib "eagle-import") (part "malekko main_RB"))
    )
    (comp (ref "R187")
      (value "1M")
      (footprint "eagle-import:R0603")
      (libsource (lib "eagle-import") (part "malekko main_RB"))
    )
    (comp (ref "R188")
      (value "1M")
      (footprint "eagle-import:R0603")
      (libsource (lib "eagle-import") (part "malekko main_RB"))
    )
    (comp (ref "R189")
      (value "100k")
      (footprint "eagle-import:R0603")
      (libsource (lib "eagle-import") (part "malekko main_RB"))
    )
    (comp (ref "R190")
      (value "100k")
      (footprint "eagle-import:R0603")
      (libsource (lib "eagle-import") (part "malekko main_RB"))
    )
    (comp (ref "R191")
      (value "68k")
      (footprint "eagle-import:R0603")
      (libsource (lib "eagle-import") (part "malekko main_RB"))
    )
    (comp (ref "R194")
      (value "100k")
      (footprint "eagle-import:R0603")
      (libsource (lib "eagle-import") (part "malekko main_RB"))
    )
    (comp (ref "U1")
      (value "WM8731")
      (footprint "eagle-import:28-SSOP")
      (libsource (lib "eagle-import") (part "WM8731"))
    )
  )
  (nets
    (net (code "1") (name "+3.3V") (class "Default")
      (node (ref "C11") (pin "1") (pinfunction "1_1") (pintype "passive"))
      (node (ref "C18") (pin "1") (pinfunction "1_1") (pintype "passive"))
      (node (ref "C22") (pin "1") (pinfunction "1_1") (pintype "passive"))
      (node (ref "C23") (pin "1") (pinfunction "1_1") (pintype "passive"))
      (node (ref "C24") (pin "1") (pinfunction "1_1") (pintype "passive"))
      (node (ref "C25") (pin "1") (pinfunction "1_1") (pintype "passive"))
      (node (ref "C26") (pin "1") (pinfunction "1_1") (pintype "passive"))
      (node (ref "C27") (pin "1") (pinfunction "1_1") (pintype "passive"))
      (node (ref "C41") (pin "1") (pinfunction "1_1") (pintype "passive"))
      (node (ref "C50") (pin "1") (pinfunction "1_1") (pintype "passive"))
      (node (ref "C51") (pin "1") (pinfunction "1_1") (pintype "passive"))
      (node (ref "C64") (pin "1") (pinfunction "1_1") (pintype "passive"))
      (node (ref "C8") (pin "+") (pinfunction "+_+") (pintype "passive"))
      (node (ref "D1") (pin "2") (pinfunction "CATHODE_2") (pintype "bidirectional"))
      (node (ref "D14") (pin "2") (pinfunction "CATHODE_2") (pintype "bidirectional"))
      (node (ref "D15") (pin "2") (pinfunction "CATHODE_2") (pintype "bidirectional"))
      (node (ref "D16") (pin "2") (pinfunction "CATHODE_2") (pintype "bidirectional"))
      (node (ref "D17") (pin "2") (pinfunction "CATHODE_2") (pintype "bidirectional"))
      (node (ref "D18") (pin "2") (pinfunction "CATHODE_2") (pintype "bidirectional"))
      (node (ref "D2") (pin "2") (pinfunction "CATHODE_2") (pintype "bidirectional"))
      (node (ref "D3") (pin "2") (pinfunction "CATHODE_2") (pintype "bidirectional"))
      (node (ref "L1") (pin "1") (pinfunction "1_1") (pintype "passive"))
      (node (ref "R16") (pin "1") (pinfunction "1_1") (pintype "passive"))
      (node (ref "R25") (pin "1") (pinfunction "1_1") (pintype "passive"))
      (node (ref "S1") (pin "3") (pinfunction "3_3") (pintype "passive"))
      (node (ref "S1") (pin "4") (pinfunction "4_4") (pintype "passive"))
      (node (ref "SWD") (pin "P$1") (pinfunction "P$1_P$1") (pintype "bidirectional"))
      (node (ref "U1") (pin "P$1") (pinfunction "DBVDD_P$1") (pintype "power_in"))
      (node (ref "U1") (pin "P$27") (pinfunction "DCVDD_P$27") (pintype "power_in"))
      (node (ref "U7") (pin "108") (pinfunction "VDD_2_108") (pintype "bidirectional"))
      (node (ref "U7") (pin "121") (pinfunction "VDD_10_121") (pintype "bidirectional"))
      (node (ref "U7") (pin "131") (pinfunction "VDD_11_131") (pintype "bidirectional"))
      (node (ref "U7") (pin "143") (pinfunction "PDR_ON_143") (pintype "bidirectional"))
      (node (ref "U7") (pin "144") (pinfunction "VDD_3_144") (pintype "bidirectional"))
      (node (ref "U7") (pin "17") (pinfunction "VDD_5_17") (pintype "bidirectional"))
      (node (ref "U7") (pin "30") (pinfunction "VDD_12_30") (pintype "bidirectional"))
      (node (ref "U7") (pin "39") (pinfunction "VDD_4_39") (pintype "bidirectional"))
      (node (ref "U7") (pin "52") (pinfunction "VDD_6_52") (pintype "bidirectional"))
      (node (ref "U7") (pin "6") (pinfunction "VBAT_6") (pintype "bidirectional"))
      (node (ref "U7") (pin "62") (pinfunction "VDD_7_62") (pintype "bidirectional"))
      (node (ref "U7") (pin "72") (pinfunction "VDD_1_72") (pintype "bidirectional"))
      (node (ref "U7") (pin "84") (pinfunction "VDD_8_84") (pintype "bidirectional"))
      (node (ref "U7") (pin "95") (pinfunction "VDD_9_95") (pintype "bidirectional"))
      (node (ref "VR4") (pin "P$3") (pinfunction "OUT_P$3") (pintype "passive"))
    )
    (net (code "2") (name "+5V") (class "Default")
      (node (ref "C46") (pin "2") (pinfunction "2_2") (pintype "passive"))
      (node (ref "C7") (pin "+") (pinfunction "+_+") (pintype "passive"))
      (node (ref "C76") (pin "1") (pinfunction "1_1") (pintype "passive"))
      (node (ref "C79") (pin "2") (pinfunction "2_2") (pintype "passive"))
      (node (ref "IC7") (pin "3") (pinfunction "IN_3") (pintype "input"))
      (node (ref "IC9") (pin "3") (pinfunction "+IN_3") (pintype "input"))
      (node (ref "IC9") (pin "5") (pinfunction "+IN_5") (pintype "input"))
      (node (ref "MORPH") (pin "3") (pinfunction "3_3") (pintype "passive"))
      (node (ref "SPREAD") (pin "3") (pinfunction "3_3") (pintype "passive"))
      (node (ref "V1") (pin "1") (pinfunction "OUT_1") (pintype "passive"))
    )
    (net (code "3") (name "+12V") (class "Default")
      (node (ref "C3") (pin "1") (pinfunction "1_1") (pintype "passive"))
      (node (ref "C4") (pin "+") (pinfunction "+_+") (pintype "passive"))
      (node (ref "C78") (pin "1") (pinfunction "1_1") (pintype "passive"))
      (node (ref "D19") (pin "K") (pinfunction "C_K") (pintype "passive"))
      (node (ref "IC1") (pin "8") (pinfunction "V+_8") (pintype "power_in"))
      (node (ref "IC2") (pin "8") (pinfunction "V+_8") (pintype "power_in"))
      (node (ref "IC3") (pin "8") (pinfunction "V+_8") (pintype "power_in"))
      (node (ref "IC4") (pin "8") (pinfunction "V+_8") (pintype "power_in"))
      (node (ref "IC5") (pin "8") (pinfunction "V+_8") (pintype "power_in"))
      (node (ref "IC6") (pin "8") (pinfunction "V+_8") (pintype "power_in"))
      (node (ref "IC8") (pin "8") (pinfunction "V+_8") (pintype "power_in"))
      (node (ref "IC9") (pin "8") (pinfunction "V+_8") (pintype "power_in"))
      (node (ref "V-SEL") (pin "P$3") (pinfunction "P$3_P$3") (pintype "bidirectional"))
      (node (ref "V1") (pin "3") (pinfunction "IN_3") (pintype "input"))
      (node (ref "VR4") (pin "P$1") (pinfunction "IN_P$1") (pintype "input"))
    )
    (net (code "4") (name "-12V") (class "Default")
      (node (ref "C47") (pin "-") (pinfunction "-_-") (pintype "passive"))
      (node (ref "D13") (pin "A") (pinfunction "A_A") (pintype "passive"))
      (node (ref "IC1") (pin "4") (pinfunction "V-_4") (pintype "power_in"))
      (node (ref "IC2") (pin "4") (pinfunction "V-_4") (pintype "power_in"))
      (node (ref "IC3") (pin "4") (pinfunction "V-_4") (pintype "power_in"))
      (node (ref "IC4") (pin "4") (pinfunction "V-_4") (pintype "power_in"))
      (node (ref "IC5") (pin "4") (pinfunction "V-_4") (pintype "power_in"))
      (node (ref "IC6") (pin "4") (pinfunction "V-_4") (pintype "power_in"))
      (node (ref "IC8") (pin "4") (pinfunction "V-_4") (pintype "power_in"))
      (node (ref "IC9") (pin "4") (pinfunction "V-_4") (pintype "power_in"))
    )
    (net (code "5") (name "5VEXT") (class "Default")
      (node (ref "L2") (pin "2") (pinfunction "4_2") (pintype "passive"))
      (node (ref "V-SEL") (pin "P$1") (pinfunction "P$1_P$1") (pintype "bidirectional"))
    )
    (net (code "6") (name "5VREF1") (class "Default")
      (node (ref "IC9") (pin "1") (pinfunction "OUT_1") (pintype "output"))
      (node (ref "IC9") (pin "2") (pinfunction "-IN_2") (pintype "input"))
      (node (ref "R34") (pin "2") (pinfunction "2_2") (pintype "passive"))
      (node (ref "R35") (pin "2") (pinfunction "2_2") (pintype "passive"))
      (node (ref "R36") (pin "2") (pinfunction "2_2") (pintype "passive"))
    )
    (net (code "7") (name "5VREF2") (class "Default")
      (node (ref "IC9") (pin "6") (pinfunction "-IN_6") (pintype "input"))
      (node (ref "IC9") (pin "7") (pinfunction "OUT_7") (pintype "output"))
      (node (ref "R115") (pin "2") (pinfunction "2_2") (pintype "passive"))
      (node (ref "R116") (pin "2") (pinfunction "2_2") (pintype "passive"))
      (node (ref "R37") (pin "2") (pinfunction "2_2") (pintype "passive"))
    )
    (net (code "8") (name "ADC-VDD") (class "Default")
      (node (ref "C10") (pin "1") (pinfunction "1_1") (pintype "passive"))
      (node (ref "C31") (pin "+") (pinfunction "+_+") (pintype "passive"))
      (node (ref "C73") (pin "1") (pinfunction "1_1") (pintype "passive"))
      (node (ref "C74") (pin "1") (pinfunction "1_1") (pintype "passive"))
      (node (ref "C77") (pin "1") (pinfunction "1_1") (pintype "passive"))
      (node (ref "C80") (pin "1") (pinfunction "1_1") (pintype "passive"))
      (node (ref "D10") (pin "2") (pinfunction "CATHODE_2") (pintype "bidirectional"))
      (node (ref "D11") (pin "2") (pinfunction "CATHODE_2") (pintype "bidirectional"))
      (node (ref "D12") (pin "2") (pinfunction "CATHODE_2") (pintype "bidirectional"))
      (node (ref "D4") (pin "2") (pinfunction "CATHODE_2") (pintype "bidirectional"))
      (node (ref "D5") (pin "2") (pinfunction "CATHODE_2") (pintype "bidirectional"))
      (node (ref "D6") (pin "2") (pinfunction "CATHODE_2") (pintype "bidirectional"))
      (node (ref "D7") (pin "2") (pinfunction "CATHODE_2") (pintype "bidirectional"))
      (node (ref "D8") (pin "2") (pinfunction "CATHODE_2") (pintype "bidirectional"))
      (node (ref "D9") (pin "2") (pinfunction "CATHODE_2") (pintype "bidirectional"))
      (node (ref "FREQNUDGE1") (pin "3") (pinfunction "3_3") (pintype "passive"))
      (node (ref "FREQNUDGE6") (pin "3") (pinfunction "3_3") (pintype "passive"))
      (node (ref "L1") (pin "2") (pinfunction "4_2") (pintype "passive"))
      (node (ref "QVAL") (pin "3") (pinfunction "3_3") (pintype "passive"))
      (node (ref "SLIDE1") (pin "P$3") (pinfunction "3_P$3") (pintype "passive"))
      (node (ref "SLIDE2") (pin "P$3") (pinfunction "3_P$3") (pintype "passive"))
      (node (ref "SLIDE3") (pin "P$3") (pinfunction "3_P$3") (pintype "passive"))
      (node (ref "SLIDE4") (pin "P$3") (pinfunction "3_P$3") (pintype "passive"))
      (node (ref "SLIDE5") (pin "P$3") (pinfunction "3_P$3") (pintype "passive"))
      (node (ref "SLIDE6") (pin "P$3") (pinfunction "3_P$3") (pintype "passive"))
      (node (ref "U7") (pin "32") (pinfunction "VREF+_32") (pintype "bidirectional"))
      (node (ref "U7") (pin "33") (pinfunction "VDDA_33") (pintype "bidirectional"))
    )
    (net (code "9") (name "AGND") (class "Default")
      (node (ref "AGND") (pin "P$1") (pinfunction "1_P$1") (pintype "bidirectional"))
      (node (ref "AGND-OPT") (pin "P$1") (pinfunction "1_P$1") (pintype "bidirectional"))
      (node (ref "C14") (pin "2") (pinfunction "2_2") (pintype "passive"))
      (node (ref "C17") (pin "2") (pinfunction "2_2") (pintype "passive"))
      (node (ref "C20") (pin "2") (pinfunction "2_2") (pintype "passive"))
      (node (ref "C21") (pin "-") (pinfunction "-_-") (pintype "passive"))
      (node (ref "C58") (pin "-") (pinfunction "-_-") (pintype "passive"))
      (node (ref "C76") (pin "2") (pinfunction "2_2") (pintype "passive"))
      (node (ref "IC1") (pin "3") (pinfunction "+IN_3") (pintype "input"))
      (node (ref "IC1") (pin "5") (pinfunction "+IN_5") (pintype "input"))
      (node (ref "IC7") (pin "1") (pinfunction "ADJ_1") (pintype "input"))
      (node (ref "R189") (pin "2") (pinfunction "2_2") (pintype "passive"))
      (node (ref "R190") (pin "2") (pinfunction "2_2") (pintype "passive"))
      (node (ref "R191") (pin "1") (pinfunction "1_1") (pintype "passive"))
      (node (ref "R194") (pin "1") (pinfunction "1_1") (pintype "passive"))
      (node (ref "U1") (pin "P$11") (pinfunction "HPGND_P$11") (pintype "power_in"))
      (node (ref "U1") (pin "P$15") (pinfunction "AGND_P$15") (pintype "power_in"))
      (node (ref "U1") (pin "P$18") (pinfunction "MICIN_P$18") (pintype "input"))
    )
    (net (code "10") (name "BANDADC1") (class "Default")
      (node (ref "D5") (pin "3") (pinfunction "COMMON_3") (pintype "bidirectional"))
      (node (ref "R38") (pin "1") (pinfunction "1_1") (pintype "passive"))
      (node (ref "R68") (pin "1") (pinfunction "1_1") (pintype "passive"))
      (node (ref "U7") (pin "36") (pinfunction "PA2/ETH_MDIO/ADC123_IN2_36") (pintype "bidirectional"))
    )
    (net (code "11") (name "BANDADC2") (class "Default")
      (node (ref "D6") (pin "3") (pinfunction "COMMON_3") (pintype "bidirectional"))
      (node (ref "R39") (pin "1") (pinfunction "1_1") (pintype "passive"))
      (node (ref "R69") (pin "1") (pinfunction "1_1") (pintype "passive"))
      (node (ref "U7") (pin "37") (pinfunction "PA3/ETH_MII_COL/ADC123_IN3_37") (pintype "bidirectional"))
    )
    (net (code "12") (name "BANDADC3") (class "Default")
      (node (ref "D7") (pin "3") (pinfunction "COMMON_3") (pintype "bidirectional"))
      (node (ref "R40") (pin "1") (pinfunction "1_1") (pintype "passive"))
      (node (ref "R70") (pin "1") (pinfunction "1_1") (pintype "passive"))
      (node (ref "U7") (pin "42") (pinfunction "PA6/SPI1_MISO/ADC12_IN6_42") (pintype "bidirectional"))
    )
    (net (code "13") (name "BANDADC4") (class "Default")
      (node (ref "D8") (pin "3") (pinfunction "COMMON_3") (pintype "bidirectional"))
      (node (ref "R41") (pin "1") (pinfunction "1_1") (pintype "passive"))
      (node (ref "R71") (pin "1") (pinfunction "1_1") (pintype "passive"))
      (node (ref "U7") (pin "43") (pinfunction "PA7/ETH_MII_RX_DV/ADC12_IN7_43") (pintype "bidirectional"))
    )
    (net (code "14") (name "BANDADC5") (class "Default")
      (node (ref "D9") (pin "3") (pinfunction "COMMON_3") (pintype "bidirectional"))
      (node (ref "R42") (pin "1") (pinfunction "1_1") (pintype "passive"))
      (node (ref "R72") (pin "1") (pinfunction "1_1") (pintype "passive"))
      (node (ref "U7") (pin "26") (pinfunction "PC0/ADC123_IN10_26") (pintype "bidirectional"))
    )
    (net (code "15") (name "BANDADC6") (class "Default")
      (node (ref "D10") (pin "3") (pinfunction "COMMON_3") (pintype "bidirectional"))
      (node (ref "R43") (pin "1") (pinfunction "1_1") (pintype "passive"))
      (node (ref "R73") (pin "1") (pinfunction "1_1") (pintype "passive"))
      (node (ref "U7") (pin "27") (pinfunction "PC1/ETH_MDC/ADC123_IN11_27") (pintype "bidirectional"))
    )
    (net (code "16") (name "BANKSCALE") (class "Default")
      (node (ref "BANKSCALE-SW") (pin "P$2") (pinfunction "P$2_P$2") (pintype "passive"))
      (node (ref "U7") (pin "85") (pinfunction "PD14/TIM4_CH3(5T)_85") (pintype "bidirectional"))
    )
    (net (code "17") (name "CODEC-VDD") (class "Default")
      (node (ref "C17") (pin "1") (pinfunction "1_1") (pintype "passive"))
      (node (ref "C58") (pin "+") (pinfunction "+_+") (pintype "passive"))
      (node (ref "IC7") (pin "2") (pinfunction "OUT_2") (pintype "passive"))
      (node (ref "IC7") (pin "4") (pinfunction "OUT_4") (pintype "passive"))
      (node (ref "R183") (pin "2") (pinfunction "2_2") (pintype "passive"))
      (node (ref "U1") (pin "P$14") (pinfunction "AVDD_P$14") (pintype "power_in"))
      (node (ref "U1") (pin "P$8") (pinfunction "HPVDD_P$8") (pintype "power_in"))
    )
    (net (code "18") (name "DAC0") (class "Default")
      (node (ref "IN-1") (pin "3") (pinfunction "TIP-SW_3") (pintype "passive"))
      (node (ref "U7") (pin "40") (pinfunction "PA4/DAC1/ADC12_IN4_40") (pintype "bidirectional"))
    )
    (net (code "19") (name "ENVPWM1") (class "Default")
      (node (ref "R9") (pin "2") (pinfunction "2_2") (pintype "passive"))
      (node (ref "U7") (pin "98") (pinfunction "PC8/TIM8_CH3(5T)_98") (pintype "bidirectional"))
    )
    (net (code "20") (name "ENVPWM2") (class "Default")
      (node (ref "R32") (pin "2") (pinfunction "2_2") (pintype "passive"))
      (node (ref "U7") (pin "99") (pinfunction "PC9/TIM3_CH4(5T)_99") (pintype "bidirectional"))
    )
    (net (code "21") (name "ENVPWM3") (class "Default")
      (node (ref "R52") (pin "2") (pinfunction "2_2") (pintype "passive"))
      (node (ref "U7") (pin "100") (pinfunction "PA8/MCO1(5T)_100") (pintype "bidirectional"))
    )
    (net (code "22") (name "ENVPWM4") (class "Default")
      (node (ref "R54") (pin "2") (pinfunction "2_2") (pintype "passive"))
      (node (ref "U7") (pin "102") (pinfunction "PA10/USART1_RX(5T)_102") (pintype "bidirectional"))
    )
    (net (code "23") (name "ENVPWM5") (class "Default")
      (node (ref "R56") (pin "2") (pinfunction "2_2") (pintype "passive"))
      (node (ref "U7") (pin "134") (pinfunction "PB4/I2S3_EXT/JNTRST_134") (pintype "bidirectional"))
    )
    (net (code "24") (name "ENVPWM6") (class "Default")
      (node (ref "R58") (pin "2") (pinfunction "2_2") (pintype "passive"))
      (node (ref "U7") (pin "135") (pinfunction "PB5/I2S3_SD/TIM3_CH2_135") (pintype "bidirectional"))
    )
    (net (code "25") (name "ENV_FAST") (class "Default")
      (node (ref "SLOWFAST-SW") (pin "P$1") (pinfunction "P$1_P$1") (pintype "passive"))
      (node (ref "U7") (pin "133") (pinfunction "PB3/I2S3_CK/JTDO_133") (pintype "bidirectional"))
    )
    (net (code "26") (name "ENV_SLOW") (class "Default")
      (node (ref "SLOWFAST-SW") (pin "P$3") (pinfunction "P$3_P$3") (pintype "passive"))
      (node (ref "U7") (pin "60") (pinfunction "PE9/TIM1_CH1(5T)_60") (pintype "bidirectional"))
    )
    (net (code "27") (name "FREQCV1ADC") (class "Default")
      (node (ref "D16") (pin "3") (pinfunction "COMMON_3") (pintype "bidirectional"))
      (node (ref "R126") (pin "2") (pinfunction "2_2") (pintype "passive"))
      (node (ref "R129") (pin "1") (pinfunction "1_1") (pintype "passive"))
      (node (ref "U7") (pin "46") (pinfunction "PB0/ETH_MII_RXD2/ADC12_IN8_46") (pintype "bidirectional"))
    )
    (net (code "28") (name "FREQCV6ADC") (class "Default")
      (node (ref "D15") (pin "3") (pinfunction "COMMON_3") (pintype "bidirectional"))
      (node (ref "R125") (pin "2") (pinfunction "2_2") (pintype "passive"))
      (node (ref "R130") (pin "1") (pinfunction "1_1") (pintype "passive"))
      (node (ref "U7") (pin "47") (pinfunction "PB1/ETH_MII_RXD3/ADC12_IN9_47") (pintype "bidirectional"))
    )
    (net (code "29") (name "FREQNUDGEADC1") (class "Default")
      (node (ref "C71") (pin "1") (pinfunction "1_1") (pintype "passive"))
      (node (ref "FREQNUDGE1") (pin "2") (pinfunction "2_2") (pintype "passive"))
      (node (ref "U7") (pin "28") (pinfunction "PC2/ETH_MII_TXD2/ADC123_IN12_28") (pintype "bidirectional"))
    )
    (net (code "30") (name "FREQNUDGEADC6") (class "Default")
      (node (ref "C72") (pin "1") (pinfunction "1_1") (pintype "passive"))
      (node (ref "FREQNUDGE6") (pin "2") (pinfunction "2_2") (pintype "passive"))
      (node (ref "U7") (pin "29") (pinfunction "PC3/ETH_MII_TX_CLK/ADC123_IN13_29") (pintype "bidirectional"))
    )
    (net (code "31") (name "GND") (class "Default")
      (node (ref "BANDCV1") (pin "2") (pinfunction "SLEEVE_2") (pintype "passive"))
      (node (ref "BANDCV2") (pin "2") (pinfunction "SLEEVE_2") (pintype "passive"))
      (node (ref "BANDCV3") (pin "2") (pinfunction "SLEEVE_2") (pintype "passive"))
      (node (ref "BANDCV4") (pin "2") (pinfunction "SLEEVE_2") (pintype "passive"))
      (node (ref "BANDCV5") (pin "2") (pinfunction "SLEEVE_2") (pintype "passive"))
      (node (ref "BANDCV6") (pin "2") (pinfunction "SLEEVE_2") (pintype "passive"))
      (node (ref "BANKSCALE-SW") (pin "P$1") (pinfunction "P$1_P$1") (pintype "passive"))
      (node (ref "C10") (pin "2") (pinfunction "2_2") (pintype "passive"))
      (node (ref "C11") (pin "2") (pinfunction "2_2") (pintype "passive"))
      (node (ref "C12") (pin "2") (pinfunction "2_2") (pintype "passive"))
      (node (ref "C13") (pin "2") (pinfunction "2_2") (pintype "passive"))
      (node (ref "C15") (pin "2") (pinfunction "2_2") (pintype "passive"))
      (node (ref "C16") (pin "2") (pinfunction "2_2") (pintype "passive"))
      (node (ref "C18") (pin "2") (pinfunction "2_2") (pintype "passive"))
      (node (ref "C19") (pin "2") (pinfunction "2_2") (pintype "passive"))
      (node (ref "C22") (pin "2") (pinfunction "2_2") (pintype "passive"))
      (node (ref "C23") (pin "2") (pinfunction "2_2") (pintype "passive"))
      (node (ref "C24") (pin "2") (pinfunction "2_2") (pintype "passive"))
      (node (ref "C25") (pin "2") (pinfunction "2_2") (pintype "passive"))
      (node (ref "C26") (pin "2") (pinfunction "2_2") (pintype "passive"))
      (node (ref "C27") (pin "2") (pinfunction "2_2") (pintype "passive"))
      (node (ref "C28") (pin "2") (pinfunction "2_2") (pintype "passive"))
      (node (ref "C29") (pin "2") (pinfunction "2_2") (pintype "passive"))
      (node (ref "C3") (pin "2") (pinfunction "2_2") (pintype "passive"))
      (node (ref "C30") (pin "2") (pinfunction "2_2") (pintype "passive"))
      (node (ref "C31") (pin "-") (pinfunction "-_-") (pintype "passive"))
      (node (ref "C32") (pin "1") (pinfunction "1_1") (pintype "passive"))
      (node (ref "C33") (pin "1") (pinfunction "1_1") (pintype "passive"))
      (node (ref "C34") (pin "2") (pinfunction "2_2") (pintype "passive"))
      (node (ref "C35") (pin "2") (pinfunction "2_2") (pintype "passive"))
      (node (ref "C36") (pin "2") (pinfunction "2_2") (pintype "passive"))
      (node (ref "C37") (pin "2") (pinfunction "2_2") (pintype "passive"))
      (node (ref "C38") (pin "2") (pinfunction "2_2") (pintype "passive"))
      (node (ref "C39") (pin "2") (pinfunction "2_2") (pintype "passive"))
      (node (ref "C4") (pin "-") (pinfunction "-_-") (pintype "passive"))
      (node (ref "C40") (pin "2") (pinfunction "2_2") (pintype "passive"))
      (node (ref "C41") (pin "2") (pinfunction "2_2") (pintype "passive"))
      (node (ref "C42") (pin "2") (pinfunction "2_2") (pintype "passive"))
      (node (ref "C43") (pin "2") (pinfunction "2_2") (pintype "passive"))
      (node (ref "C44") (pin "2") (pinfunction "2_2") (pintype "passive"))
      (node (ref "C45") (pin "2") (pinfunction "2_2") (pintype "passive"))
      (node (ref "C46") (pin "1") (pinfunction "1_1") (pintype "passive"))
      (node (ref "C47") (pin "+") (pinfunction "+_+") (pintype "passive"))
      (node (ref "C48") (pin "2") (pinfunction "2_2") (pintype "passive"))
      (node (ref "C49") (pin "2") (pinfunction "2_2") (pintype "passive"))
      (node (ref "C50") (pin "2") (pinfunction "2_2") (pintype "passive"))
      (node (ref "C51") (pin "2") (pinfunction "2_2") (pintype "passive"))
      (node (ref "C56") (pin "-") (pinfunction "-_-") (pintype "passive"))
      (node (ref "C57") (pin "2") (pinfunction "2_2") (pintype "passive"))
      (node (ref "C59") (pin "2") (pinfunction "2_2") (pintype "passive"))
      (node (ref "C60") (pin "2") (pinfunction "2_2") (pintype "passive"))
      (node (ref "C61") (pin "2") (pinfunction "2_2") (pintype "passive"))
      (node (ref "C62") (pin "2") (pinfunction "2_2") (pintype "passive"))
      (node (ref "C63") (pin "2") (pinfunction "2_2") (pintype "passive"))
      (node (ref "C64") (pin "2") (pinfunction "2_2") (pintype "passive"))
      (node (ref "C65") (pin "2") (pinfunction "2_2") (pintype "passive"))
      (node (ref "C66") (pin "2") (pinfunction "2_2") (pintype "passive"))
      (node (ref "C67") (pin "2") (pinfunction "2_2") (pintype "passive"))
      (node (ref "C68") (pin "2") (pinfunction "2_2") (pintype "passive"))
      (node (ref "C69") (pin "2") (pinfunction "2_2") (pintype "passive"))
      (node (ref "C7") (pin "-") (pinfunction "-_-") (pintype "passive"))
      (node (ref "C70") (pin "2") (pinfunction "2_2") (pintype "passive"))
      (node (ref "C71") (pin "2") (pinfunction "2_2") (pintype "passive"))
      (node (ref "C72") (pin "2") (pinfunction "2_2") (pintype "passive"))
      (node (ref "C73") (pin "2") (pinfunction "2_2") (pintype "passive"))
      (node (ref "C74") (pin "2") (pinfunction "2_2") (pintype "passive"))
      (node (ref "C75") (pin "2") (pinfunction "2_2") (pintype "passive"))
      (node (ref "C77") (pin "2") (pinfunction "2_2") (pintype "passive"))
      (node (ref "C78") (pin "2") (pinfunction "2_2") (pintype "passive"))
      (node (ref "C79") (pin "1") (pinfunction "1_1") (pintype "passive"))
      (node (ref "C8") (pin "-") (pinfunction "-_-") (pintype "passive"))
      (node (ref "C80") (pin "2") (pinfunction "2_2") (pintype "passive"))
      (node (ref "C9") (pin "2") (pinfunction "2_2") (pintype "passive"))
      (node (ref "D1") (pin "1") (pinfunction "ANODE_1") (pintype "bidirectional"))
      (node (ref "D10") (pin "1") (pinfunction "ANODE_1") (pintype "bidirectional"))
      (node (ref "D11") (pin "1") (pinfunction "ANODE_1") (pintype "bidirectional"))
      (node (ref "D12") (pin "1") (pinfunction "ANODE_1") (pintype "bidirectional"))
      (node (ref "D14") (pin "1") (pinfunction "ANODE_1") (pintype "bidirectional"))
      (node (ref "D15") (pin "1") (pinfunction "ANODE_1") (pintype "bidirectional"))
      (node (ref "D16") (pin "1") (pinfunction "ANODE_1") (pintype "bidirectional"))
      (node (ref "D17") (pin "1") (pinfunction "ANODE_1") (pintype "bidirectional"))
      (node (ref "D18") (pin "1") (pinfunction "ANODE_1") (pintype "bidirectional"))
      (node (ref "D2") (pin "1") (pinfunction "ANODE_1") (pintype "bidirectional"))
      (node (ref "D3") (pin "1") (pinfunction "ANODE_1") (pintype "bidirectional"))
      (node (ref "D4") (pin "1") (pinfunction "ANODE_1") (pintype "bidirectional"))
      (node (ref "D5") (pin "1") (pinfunction "ANODE_1") (pintype "bidirectional"))
      (node (ref "D6") (pin "1") (pinfunction "ANODE_1") (pintype "bidirectional"))
      (node (ref "D7") (pin "1") (pinfunction "ANODE_1") (pintype "bidirectional"))
      (node (ref "D8") (pin "1") (pinfunction "ANODE_1") (pintype "bidirectional"))
      (node (ref "D9") (pin "1") (pinfunction "ANODE_1") (pintype "bidirectional"))
      (node (ref "DGND") (pin "P$1") (pinfunction "1_P$1") (pintype "bidirectional"))
      (node (ref "ENC1") (pin "2") (pinfunction "P$2_2") (pintype "bidirectional"))
      (node (ref "ENC1") (pin "SW2") (pinfunction "P$2_SW2") (pintype "passive"))
      (node (ref "ENV1") (pin "2") (pinfunction "SLEEVE_2") (pintype "passive"))
      (node (ref "ENV2") (pin "2") (pinfunction "SLEEVE_2") (pintype "passive"))
      (node (ref "ENV3") (pin "2") (pinfunction "SLEEVE_2") (pintype "passive"))
      (node (ref "ENV4") (pin "2") (pinfunction "SLEEVE_2") (pintype "passive"))
      (node (ref "ENV5") (pin "2") (pinfunction "SLEEVE_2") (pintype "passive"))
      (node (ref "ENV6") (pin "2") (pinfunction "SLEEVE_2") (pintype "passive"))
      (node (ref "FREQCV1") (pin "2") (pinfunction "SLEEVE_2") (pintype "passive"))
      (node (ref "FREQCV1") (pin "3") (pinfunction "TIP-SW_3") (pintype "passive"))
      (node (ref "FREQCV6") (pin "2") (pinfunction "SLEEVE_2") (pintype "passive"))
      (node (ref "FREQCV6") (pin "3") (pinfunction "TIP-SW_3") (pintype "passive"))
      (node (ref "FREQNUDGE1") (pin "1") (pinfunction "1_1") (pintype "passive"))
      (node (ref "FREQNUDGE6") (pin "1") (pinfunction "1_1") (pintype "passive"))
      (node (ref "IC10") (pin "1") (pinfunction "ADJ_1") (pintype "input"))
      (node (ref "IN-1") (pin "2") (pinfunction "SLEEVE_2") (pintype "passive"))
      (node (ref "IN-2") (pin "2") (pinfunction "SLEEVE_2") (pintype "passive"))
      (node (ref "LAG-SW") (pin "P$1") (pinfunction "P$1_P$1") (pintype "passive"))
      (node (ref "LED-INCLIP") (pin "K-2") (pinfunction "C_K-2") (pintype "passive"))
      (node (ref "LOCK1") (pin "P$6") (pinfunction "P$6_P$6") (pintype "bidirectional"))
      (node (ref "LOCK1") (pin "P$8") (pinfunction "P$8_P$8") (pintype "bidirectional"))
      (node (ref "LOCK2") (pin "P$6") (pinfunction "P$6_P$6") (pintype "bidirectional"))
      (node (ref "LOCK2") (pin "P$8") (pinfunction "P$8_P$8") (pintype "bidirectional"))
      (node (ref "LOCK3") (pin "P$6") (pinfunction "P$6_P$6") (pintype "bidirectional"))
      (node (ref "LOCK3") (pin "P$8") (pinfunction "P$8_P$8") (pintype "bidirectional"))
      (node (ref "LOCK4") (pin "P$6") (pinfunction "P$6_P$6") (pintype "bidirectional"))
      (node (ref "LOCK4") (pin "P$8") (pinfunction "P$8_P$8") (pintype "bidirectional"))
      (node (ref "LOCK5") (pin "P$6") (pinfunction "P$6_P$6") (pintype "bidirectional"))
      (node (ref "LOCK5") (pin "P$8") (pinfunction "P$8_P$8") (pintype "bidirectional"))
      (node (ref "LOCK6") (pin "P$6") (pinfunction "P$6_P$6") (pintype "bidirectional"))
      (node (ref "LOCK6") (pin "P$8") (pinfunction "P$8_P$8") (pintype "bidirectional"))
      (node (ref "LOCK_135") (pin "2") (pinfunction "SLEEVE_2") (pintype "passive"))
      (node (ref "LOCK_135") (pin "3") (pinfunction "TIP-SW_3") (pintype "passive"))
      (node (ref "LOCK_246") (pin "2") (pinfunction "SLEEVE_2") (pintype "passive"))
      (node (ref "LOCK_246") (pin "3") (pinfunction "TIP-SW_3") (pintype "passive"))
      (node (ref "MOD135-SW") (pin "P$1") (pinfunction "P$1_P$1") (pintype "passive"))
      (node (ref "MOD246-SW") (pin "P$1") (pinfunction "P$1_P$1") (pintype "passive"))
      (node (ref "MORPH") (pin "1") (pinfunction "1_1") (pintype "passive"))
      (node (ref "MORPHCV") (pin "2") (pinfunction "SLEEVE_2") (pintype "passive"))
      (node (ref "MORPHCV") (pin "3") (pinfunction "TIP-SW_3") (pintype "passive"))
      (node (ref "OUT-1") (pin "2") (pinfunction "SLEEVE_2") (pintype "passive"))
      (node (ref "OUT-2") (pin "2") (pinfunction "SLEEVE_2") (pintype "passive"))
      (node (ref "POWER") (pin "10") (pinfunction "P$10_10") (pintype "bidirectional"))
      (node (ref "POWER") (pin "11") (pinfunction "P$11_11") (pintype "bidirectional"))
      (node (ref "POWER") (pin "12") (pinfunction "P$12_12") (pintype "bidirectional"))
      (node (ref "POWER") (pin "13") (pinfunction "P$13_13") (pintype "bidirectional"))
      (node (ref "POWER") (pin "14") (pinfunction "P$14_14") (pintype "bidirectional"))
      (node (ref "POWER") (pin "9") (pinfunction "P$9_9") (pintype "bidirectional"))
      (node (ref "PREPOST-SW") (pin "P$1") (pinfunction "P$1_P$1") (pintype "passive"))
      (node (ref "QVAL") (pin "1") (pinfunction "1_1") (pintype "passive"))
      (node (ref "QVALCV") (pin "2") (pinfunction "SLEEVE_2") (pintype "passive"))
      (node (ref "R127") (pin "2") (pinfunction "2_2") (pintype "passive"))
      (node (ref "R128") (pin "2") (pinfunction "2_2") (pintype "passive"))
      (node (ref "R129") (pin "2") (pinfunction "2_2") (pintype "passive"))
      (node (ref "R130") (pin "2") (pinfunction "2_2") (pintype "passive"))
      (node (ref "R172") (pin "2") (pinfunction "2_2") (pintype "passive"))
      (node (ref "R187") (pin "2") (pinfunction "2_2") (pintype "passive"))
      (node (ref "R188") (pin "2") (pinfunction "2_2") (pintype "passive"))
      (node (ref "R21") (pin "2") (pinfunction "2_2") (pintype "passive"))
      (node (ref "R22") (pin "2") (pinfunction "2_2") (pintype "passive"))
      (node (ref "R23") (pin "2") (pinfunction "2_2") (pintype "passive"))
      (node (ref "R24") (pin "2") (pinfunction "2_2") (pintype "passive"))
      (node (ref "R26") (pin "2") (pinfunction "2_2") (pintype "passive"))
      (node (ref "R38") (pin "2") (pinfunction "2_2") (pintype "passive"))
      (node (ref "R39") (pin "2") (pinfunction "2_2") (pintype "passive"))
      (node (ref "R40") (pin "2") (pinfunction "2_2") (pintype "passive"))
      (node (ref "R41") (pin "2") (pinfunction "2_2") (pintype "passive"))
      (node (ref "R42") (pin "2") (pinfunction "2_2") (pintype "passive"))
      (node (ref "R43") (pin "2") (pinfunction "2_2") (pintype "passive"))
      (node (ref "R48") (pin "2") (pinfunction "2_2") (pintype "passive"))
      (node (ref "R49") (pin "2") (pinfunction "2_2") (pintype "passive"))
      (node (ref "R82") (pin "2") (pinfunction "2_2") (pintype "passive"))
      (node (ref "R83") (pin "2") (pinfunction "2_2") (pintype "passive"))
      (node (ref "R85") (pin "2") (pinfunction "2_2") (pintype "passive"))
      (node (ref "R87") (pin "2") (pinfunction "2_2") (pintype "passive"))
      (node (ref "R89") (pin "2") (pinfunction "2_2") (pintype "passive"))
      (node (ref "R91") (pin "2") (pinfunction "2_2") (pintype "passive"))
      (node (ref "ROTCV") (pin "2") (pinfunction "SLEEVE_2") (pintype "passive"))
      (node (ref "ROTCV") (pin "3") (pinfunction "TIP-SW_3") (pintype "passive"))
      (node (ref "ROTRIGUP") (pin "2") (pinfunction "SLEEVE_2") (pintype "passive"))
      (node (ref "ROTRIGUP") (pin "3") (pinfunction "TIP-SW_3") (pintype "passive"))
      (node (ref "ROTTRIGDOWN") (pin "2") (pinfunction "SLEEVE_2") (pintype "passive"))
      (node (ref "ROTTRIGDOWN") (pin "3") (pinfunction "TIP-SW_3") (pintype "passive"))
      (node (ref "S0") (pin "1") (pinfunction "1_1") (pintype "passive"))
      (node (ref "S0") (pin "2") (pinfunction "2_2") (pintype "passive"))
      (node (ref "SCALECV") (pin "2") (pinfunction "SLEEVE_2") (pintype "passive"))
      (node (ref "SCALECV") (pin "3") (pinfunction "TIP-SW_3") (pintype "passive"))
      (node (ref "SLIDE1") (pin "P$1") (pinfunction "1_P$1") (pintype "passive"))
      (node (ref "SLIDE2") (pin "P$1") (pinfunction "1_P$1") (pintype "passive"))
      (node (ref "SLIDE3") (pin "P$1") (pinfunction "1_P$1") (pintype "passive"))
      (node (ref "SLIDE4") (pin "P$1") (pinfunction "1_P$1") (pintype "passive"))
      (node (ref "SLIDE5") (pin "P$1") (pinfunction "1_P$1") (pintype "passive"))
      (node (ref "SLIDE6") (pin "P$1") (pinfunction "1_P$1") (pintype "passive"))
      (node (ref "SLOWFAST-SW") (pin "P$2") (pinfunction "P$2_P$2") (pintype "passive"))
      (node (ref "SPREAD") (pin "1") (pinfunction "1_1") (pintype "passive"))
      (node (ref "SPREADCV") (pin "2") (pinfunction "SLEEVE_2") (pintype "passive"))
      (node (ref "SPREADCV") (pin "3") (pinfunction "TIP-SW_3") (pintype "passive"))
      (node (ref "SWD") (pin "P$3") (pinfunction "P$3_P$3") (pintype "bidirectional"))
      (node (ref "U$1") (pin "GND") (pinfunction "GND_GND") (pintype "bidirectional"))
      (node (ref "U$1") (pin "MTN1") (pinfunction "MTN2_MTN1") (pintype "bidirectional"))
      (node (ref "U$1") (pin "MTN2") (pinfunction "MTN3_MTN2") (pintype "bidirectional"))
      (node (ref "U$1") (pin "MTN3") (pinfunction "MTN1_MTN3") (pintype "bidirectional"))
      (node (ref "U$1") (pin "MTN4") (pinfunction "MTN4_MTN4") (pintype "bidirectional"))
      (node (ref "U1") (pin "P$21") (pinfunction "MODE_P$21") (pintype "input"))
      (node (ref "U1") (pin "P$22") (pinfunction "CSB_P$22") (pintype "input"))
      (node (ref "U1") (pin "P$28") (pinfunction "DGND_P$28") (pintype "power_in"))
      (node (ref "U2") (pin "1") (pinfunction "A0_1") (pintype "bidirectional"))
      (node (ref "U2") (pin "14") (pinfunction "GND_14") (pintype "power_in"))
      (node (ref "U2") (pin "2") (pinfunction "A1_2") (pintype "bidirectional"))
      (node (ref "U2") (pin "24") (pinfunction "A5_24") (pintype "bidirectional"))
      (node (ref "U2") (pin "25") (pinfunction "EXTCLK_25") (pintype "input"))
      (node (ref "U2") (pin "4") (pinfunction "A3_4") (pintype "bidirectional"))
      (node (ref "U2") (pin "5") (pinfunction "A4_5") (pintype "bidirectional"))
      (node (ref "U3") (pin "1") (pinfunction "A0_1") (pintype "bidirectional"))
      (node (ref "U3") (pin "14") (pinfunction "GND_14") (pintype "power_in"))
      (node (ref "U3") (pin "2") (pinfunction "A1_2") (pintype "bidirectional"))
      (node (ref "U3") (pin "24") (pinfunction "A5_24") (pintype "bidirectional"))
      (node (ref "U3") (pin "25") (pinfunction "EXTCLK_25") (pintype "input"))
      (node (ref "U3") (pin "3") (pinfunction "A2_3") (pintype "bidirectional"))
      (node (ref "U3") (pin "4") (pinfunction "A3_4") (pintype "bidirectional"))
      (node (ref "U3") (pin "5") (pinfunction "A4_5") (pintype "bidirectional"))
      (node (ref "U4") (pin "14") (pinfunction "GND_14") (pintype "power_in"))
      (node (ref "U4") (pin "2") (pinfunction "A1_2") (pintype "bidirectional"))
      (node (ref "U4") (pin "24") (pinfunction "A5_24") (pintype "bidirectional"))
      (node (ref "U4") (pin "25") (pinfunction "EXTCLK_25") (pintype "input"))
      (node (ref "U4") (pin "3") (pinfunction "A2_3") (pintype "bidirectional"))
      (node (ref "U4") (pin "4") (pinfunction "A3_4") (pintype "bidirectional"))
      (node (ref "U4") (pin "5") (pinfunction "A4_5") (pintype "bidirectional"))
      (node (ref "U5") (pin "1") (pinfunction "A0_1") (pintype "bidirectional"))
      (node (ref "U5") (pin "14") (pinfunction "GND_14") (pintype "power_in"))
      (node (ref "U5") (pin "24") (pinfunction "A5_24") (pintype "bidirectional"))
      (node (ref "U5") (pin "25") (pinfunction "EXTCLK_25") (pintype "input"))
      (node (ref "U5") (pin "3") (pinfunction "A2_3") (pintype "bidirectional"))
      (node (ref "U5") (pin "4") (pinfunction "A3_4") (pintype "bidirectional"))
      (node (ref "U5") (pin "5") (pinfunction "A4_5") (pintype "bidirectional"))
      (node (ref "U6") (pin "14") (pinfunction "GND_14") (pintype "power_in"))
      (node (ref "U6") (pin "24") (pinfunction "A5_24") (pintype "bidirectional"))
      (node (ref "U6") (pin "25") (pinfunction "EXTCLK_25") (pintype "input"))
      (node (ref "U6") (pin "3") (pinfunction "A2_3") (pintype "bidirectional"))
      (node (ref "U6") (pin "4") (pinfunction "A3_4") (pintype "bidirectional"))
      (node (ref "U6") (pin "5") (pinfunction "A4_5") (pintype "bidirectional"))
      (node (ref "U7") (pin "107") (pinfunction "VSS_2_107") (pintype "bidirectional"))
      (node (ref "U7") (pin "120") (pinfunction "VSS_10_120") (pintype "bidirectional"))
      (node (ref "U7") (pin "130") (pinfunction "VSS_11_130") (pintype "bidirectional"))
      (node (ref "U7") (pin "16") (pinfunction "VSS_5_16") (pintype "bidirectional"))
      (node (ref "U7") (pin "31") (pinfunction "VSSA_31") (pintype "bidirectional"))
      (node (ref "U7") (pin "38") (pinfunction "VSS_4_38") (pintype "bidirectional"))
      (node (ref "U7") (pin "51") (pinfunction "VSS_6_51") (pintype "bidirectional"))
      (node (ref "U7") (pin "61") (pinfunction "VSS_7_61") (pintype "bidirectional"))
      (node (ref "U7") (pin "83") (pinfunction "VSS_8_83") (pintype "bidirectional"))
      (node (ref "U7") (pin "94") (pinfunction "VSS_9_94") (pintype "bidirectional"))
      (node (ref "V1") (pin "2A") (pinfunction "GND_2A") (pintype "input"))
      (node (ref "V1") (pin "2B") (pinfunction "GND_2B") (pintype "input"))
      (node (ref "VR4") (pin "P$2") (pinfunction "GND_P$2") (pintype "input"))
    )
    (net (code "32") (name "I2C1_SCL") (class "Default")
      (node (ref "R65") (pin "2") (pinfunction "2_2") (pintype "passive"))
      (node (ref "U2") (pin "26") (pinfunction "SCL_26") (pintype "bidirectional"))
      (node (ref "U3") (pin "26") (pinfunction "SCL_26") (pintype "bidirectional"))
      (node (ref "U4") (pin "26") (pinfunction "SCL_26") (pintype "bidirectional"))
      (node (ref "U5") (pin "26") (pinfunction "SCL_26") (pintype "bidirectional"))
      (node (ref "U6") (pin "26") (pinfunction "SCL_26") (pintype "bidirectional"))
      (node (ref "U7") (pin "139") (pinfunction "PB8/I2C1_SCL/TIM10_CH1_139") (pintype "bidirectional"))
    )
    (net (code "33") (name "I2C1_SDA") (class "Default")
      (node (ref "R66") (pin "2") (pinfunction "2_2") (pintype "passive"))
      (node (ref "U2") (pin "27") (pinfunction "SDA_27") (pintype "bidirectional"))
      (node (ref "U3") (pin "27") (pinfunction "SDA_27") (pintype "bidirectional"))
      (node (ref "U4") (pin "27") (pinfunction "SDA_27") (pintype "bidirectional"))
      (node (ref "U5") (pin "27") (pinfunction "SDA_27") (pintype "bidirectional"))
      (node (ref "U6") (pin "27") (pinfunction "SDA_27") (pintype "bidirectional"))
      (node (ref "U7") (pin "140") (pinfunction "PB9/I2C1_SDA/TIM11_CH1_140") (pintype "bidirectional"))
    )
    (net (code "34") (name "I2C2_SCL") (class "Default")
      (node (ref "R16") (pin "2") (pinfunction "2_2") (pintype "passive"))
      (node (ref "U1") (pin "P$24") (pinfunction "SCLK_P$24") (pintype "input"))
      (node (ref "U7") (pin "69") (pinfunction "PB10/I2C2_SCL/I2S2_CK/ETH_MII_RX_ER_69") (pintype "bidirectional"))
    )
    (net (code "35") (name "I2C2_SDA") (class "Default")
      (node (ref "R25") (pin "2") (pinfunction "2_2") (pintype "passive"))
      (node (ref "U1") (pin "P$23") (pinfunction "SDIN_P$23") (pintype "bidirectional"))
      (node (ref "U7") (pin "70") (pinfunction "PB11/I2C2_SDA/ETH_MII_TX_EN_70") (pintype "bidirectional"))
    )
    (net (code "36") (name "I2S2_LRCK") (class "Default")
      (node (ref "U1") (pin "P$5") (pinfunction "DACLRC_P$5") (pintype "bidirectional"))
      (node (ref "U1") (pin "P$7") (pinfunction "ADCLRC_P$7") (pintype "bidirectional"))
      (node (ref "U7") (pin "73") (pinfunction "PB12/I2S2_WS/ETH_MII_TXD0_73") (pintype "bidirectional"))
    )
    (net (code "37") (name "I2S2_MCLK") (class "Default")
      (node (ref "U1") (pin "P$25") (pinfunction "XTI/MCLK_P$25") (pintype "input"))
      (node (ref "U7") (pin "96") (pinfunction "PC6/I2S2_MCK/TIM3_CH1_96") (pintype "bidirectional"))
    )
    (net (code "38") (name "I2S2_SCLK") (class "Default")
      (node (ref "U1") (pin "P$3") (pinfunction "BCLK_P$3") (pintype "bidirectional"))
      (node (ref "U7") (pin "74") (pinfunction "PB13/I2S2_CK/ETH_MII_TXD1_74") (pintype "bidirectional"))
    )
    (net (code "39") (name "I2S2_SDI") (class "Default")
      (node (ref "U1") (pin "P$6") (pinfunction "ADCDAT_P$6") (pintype "output"))
      (node (ref "U7") (pin "75") (pinfunction "PB14/I2S2_EXT/TIM8_CH2N_75") (pintype "bidirectional"))
    )
    (net (code "40") (name "I2S2_SDO") (class "Default")
      (node (ref "U1") (pin "P$4") (pinfunction "DACDAT_P$4") (pintype "input"))
      (node (ref "U7") (pin "76") (pinfunction "PB15/I2S2_SD/TIM8_CH3N_76") (pintype "bidirectional"))
    )
    (net (code "41") (name "IN-CLIP-L") (class "Default")
      (node (ref "R7") (pin "2") (pinfunction "2_2") (pintype "passive"))
      (node (ref "U7") (pin "58") (pinfunction "PE7/TIM1_ETR(5T)_58") (pintype "bidirectional"))
    )
    (net (code "42") (name "IN-CLIP-R") (class "Default")
      (node (ref "R67") (pin "1") (pinfunction "1_1") (pintype "passive"))
      (node (ref "U7") (pin "97") (pinfunction "PC7/I2S3_MCK/TIM8_CH2_97") (pintype "bidirectional"))
    )
    (net (code "43") (name "IN-L") (class "Default")
      (node (ref "C1") (pin "1") (pinfunction "1_1") (pintype "passive"))
      (node (ref "U1") (pin "P$20") (pinfunction "LLINEIN_P$20") (pintype "input"))
    )
    (net (code "44") (name "IN-R") (class "Default")
      (node (ref "C2") (pin "1") (pinfunction "1_1") (pintype "passive"))
      (node (ref "U1") (pin "P$19") (pinfunction "RLINEIN_P$19") (pintype "input"))
    )
    (net (code "45") (name "LAG") (class "Default")
      (node (ref "LAG-SW") (pin "P$2") (pinfunction "P$2_P$2") (pintype "passive"))
      (node (ref "U7") (pin "59") (pinfunction "PE8/TIM1_CH1N(5T)_59") (pintype "bidirectional"))
    )
    (net (code "46") (name "LEDRING_OE") (class "Default")
      (node (ref "U2") (pin "23") (pinfunction "#OE_23") (pintype "input"))
      (node (ref "U3") (pin "23") (pinfunction "#OE_23") (pintype "input"))
      (node (ref "U4") (pin "23") (pinfunction "#OE_23") (pintype "input"))
      (node (ref "U5") (pin "23") (pinfunction "#OE_23") (pintype "input"))
      (node (ref "U6") (pin "23") (pinfunction "#OE_23") (pintype "input"))
      (node (ref "U7") (pin "3") (pinfunction "PE4(5T)_3") (pintype "bidirectional"))
    )
    (net (code "47") (name "LEDRING_VCC") (class "Default")
      (node (ref "C56") (pin "+") (pinfunction "+_+") (pintype "passive"))
      (node (ref "C57") (pin "1") (pinfunction "1_1") (pintype "passive"))
      (node (ref "C59") (pin "1") (pinfunction "1_1") (pintype "passive"))
      (node (ref "C60") (pin "1") (pinfunction "1_1") (pintype "passive"))
      (node (ref "C61") (pin "1") (pinfunction "1_1") (pintype "passive"))
      (node (ref "C62") (pin "1") (pinfunction "1_1") (pintype "passive"))
      (node (ref "C63") (pin "1") (pinfunction "1_1") (pintype "passive"))
      (node (ref "IC10") (pin "2") (pinfunction "OUT_2") (pintype "passive"))
      (node (ref "IC10") (pin "4") (pinfunction "OUT_4") (pintype "passive"))
      (node (ref "LED1") (pin "P$2") (pinfunction "A_P$2") (pintype "passive"))
      (node (ref "LED10") (pin "P$2") (pinfunction "A_P$2") (pintype "passive"))
      (node (ref "LED11") (pin "P$2") (pinfunction "A_P$2") (pintype "passive"))
      (node (ref "LED12") (pin "P$2") (pinfunction "A_P$2") (pintype "passive"))
      (node (ref "LED13") (pin "P$2") (pinfunction "A_P$2") (pintype "passive"))
      (node (ref "LED14") (pin "P$2") (pinfunction "A_P$2") (pintype "passive"))
      (node (ref "LED15") (pin "P$2") (pinfunction "A_P$2") (pintype "passive"))
      (node (ref "LED16") (pin "P$2") (pinfunction "A_P$2") (pintype "passive"))
      (node (ref "LED17") (pin "P$2") (pinfunction "A_P$2") (pintype "passive"))
      (node (ref "LED18") (pin "P$2") (pinfunction "A_P$2") (pintype "passive"))
      (node (ref "LED19") (pin "P$2") (pinfunction "A_P$2") (pintype "passive"))
      (node (ref "LED2") (pin "P$2") (pinfunction "A_P$2") (pintype "passive"))
      (node (ref "LED20") (pin "P$2") (pinfunction "A_P$2") (pintype "passive"))
      (node (ref "LED21") (pin "P$2") (pinfunction "A_P$2") (pintype "passive"))
      (node (ref "LED22") (pin "P$2") (pinfunction "A_P$2") (pintype "passive"))
      (node (ref "LED23") (pin "P$2") (pinfunction "A_P$2") (pintype "passive"))
      (node (ref "LED24") (pin "P$2") (pinfunction "A_P$2") (pintype "passive"))
      (node (ref "LED25") (pin "P$2") (pinfunction "A_P$2") (pintype "passive"))
      (node (ref "LED26") (pin "P$2") (pinfunction "A_P$2") (pintype "passive"))
      (node (ref "LED3") (pin "P$2") (pinfunction "A_P$2") (pintype "passive"))
      (node (ref "LED4") (pin "P$2") (pinfunction "A_P$2") (pintype "passive"))
      (node (ref "LED5") (pin "P$2") (pinfunction "A_P$2") (pintype "passive"))
      (node (ref "LED6") (pin "P$2") (pinfunction "A_P$2") (pintype "passive"))
      (node (ref "LED7") (pin "P$2") (pinfunction "A_P$2") (pintype "passive"))
      (node (ref "LED8") (pin "P$2") (pinfunction "A_P$2") (pintype "passive"))
      (node (ref "LED9") (pin "P$2") (pinfunction "A_P$2") (pintype "passive"))
      (node (ref "R65") (pin "1") (pinfunction "1_1") (pintype "passive"))
      (node (ref "R66") (pin "1") (pinfunction "1_1") (pintype "passive"))
      (node (ref "U2") (pin "28") (pinfunction "VDD_28") (pintype "power_in"))
      (node (ref "U2") (pin "3") (pinfunction "A2_3") (pintype "bidirectional"))
      (node (ref "U3") (pin "28") (pinfunction "VDD_28") (pintype "power_in"))
      (node (ref "U4") (pin "1") (pinfunction "A0_1") (pintype "bidirectional"))
      (node (ref "U4") (pin "28") (pinfunction "VDD_28") (pintype "power_in"))
      (node (ref "U5") (pin "2") (pinfunction "A1_2") (pintype "bidirectional"))
      (node (ref "U5") (pin "28") (pinfunction "VDD_28") (pintype "power_in"))
      (node (ref "U6") (pin "1") (pinfunction "A0_1") (pintype "bidirectional"))
      (node (ref "U6") (pin "2") (pinfunction "A1_2") (pintype "bidirectional"))
      (node (ref "U6") (pin "28") (pinfunction "VDD_28") (pintype "power_in"))
    )
    (net (code "48") (name "LOCKBUT1") (class "Default")
      (node (ref "C34") (pin "1") (pinfunction "1_1") (pintype "passive"))
      (node (ref "R46") (pin "1") (pinfunction "1_1") (pintype "passive"))
      (node (ref "U7") (pin "81") (pinfunction "PD12/TIM4_CH1(5T)_81") (pintype "bidirectional"))
    )
    (net (code "49") (name "LOCKBUT2") (class "Default")
      (node (ref "C16") (pin "1") (pinfunction "1_1") (pintype "passive"))
      (node (ref "R117") (pin "1") (pinfunction "1_1") (pintype "passive"))
      (node (ref "U7") (pin "114") (pinfunction "PD0/CAN1_RX(5T)_114") (pintype "bidirectional"))
    )
    (net (code "50") (name "LOCKBUT3") (class "Default")
      (node (ref "C30") (pin "1") (pinfunction "1_1") (pintype "passive"))
      (node (ref "R119") (pin "1") (pinfunction "1_1") (pintype "passive"))
      (node (ref "U7") (pin "115") (pinfunction "PD1/CAN1_TX(5T)_115") (pintype "bidirectional"))
    )
    (net (code "51") (name "LOCKBUT4") (class "Default")
      (node (ref "C37") (pin "1") (pinfunction "1_1") (pintype "passive"))
      (node (ref "R121") (pin "1") (pinfunction "1_1") (pintype "passive"))
      (node (ref "U7") (pin "116") (pinfunction "PD2/UART5_RX(5T)_116") (pintype "bidirectional"))
    )
    (net (code "52") (name "LOCKBUT5") (class "Default")
      (node (ref "C39") (pin "1") (pinfunction "1_1") (pintype "passive"))
      (node (ref "R123") (pin "1") (pinfunction "1_1") (pintype "passive"))
      (node (ref "U7") (pin "117") (pinfunction "PD3(5T)_117") (pintype "bidirectional"))
    )
    (net (code "53") (name "LOCKBUT6") (class "Default")
      (node (ref "C35") (pin "1") (pinfunction "1_1") (pintype "passive"))
      (node (ref "R47") (pin "1") (pinfunction "1_1") (pintype "passive"))
      (node (ref "U7") (pin "132") (pinfunction "PG15_132") (pintype "bidirectional"))
    )
    (net (code "54") (name "LOCKLED1") (class "Default")
      (node (ref "R44") (pin "1") (pinfunction "1_1") (pintype "passive"))
      (node (ref "U7") (pin "4") (pinfunction "PE5/TIM9_CH1(5T)_4") (pintype "bidirectional"))
    )
    (net (code "55") (name "LOCKLED2") (class "Default")
      (node (ref "R50") (pin "1") (pinfunction "1_1") (pintype "passive"))
      (node (ref "U7") (pin "141") (pinfunction "PE0(5T)_141") (pintype "bidirectional"))
    )
    (net (code "56") (name "LOCKLED3") (class "Default")
      (node (ref "R118") (pin "1") (pinfunction "1_1") (pintype "passive"))
      (node (ref "U7") (pin "142") (pinfunction "PE1(5T)_142") (pintype "bidirectional"))
    )
    (net (code "57") (name "LOCKLED4") (class "Default")
      (node (ref "R120") (pin "1") (pinfunction "1_1") (pintype "passive"))
      (node (ref "U7") (pin "1") (pinfunction "PE2/ETH_MII_TXD3(5T)_1") (pintype "bidirectional"))
    )
    (net (code "58") (name "LOCKLED5") (class "Default")
      (node (ref "R122") (pin "1") (pinfunction "1_1") (pintype "passive"))
      (node (ref "U7") (pin "2") (pinfunction "PE3(5T)_2") (pintype "bidirectional"))
    )
    (net (code "59") (name "LOCKLED6") (class "Default")
      (node (ref "R45") (pin "1") (pinfunction "1_1") (pintype "passive"))
      (node (ref "U7") (pin "5") (pinfunction "PE6/TIM9_CH2(5T)_5") (pintype "bidirectional"))
    )
    (net (code "60") (name "LOCK_135") (class "Default")
      (node (ref "D17") (pin "3") (pinfunction "COMMON_3") (pintype "bidirectional"))
      (node (ref "R168") (pin "2") (pinfunction "2_2") (pintype "passive"))
      (node (ref "U7") (pin "136") (pinfunction "PB6/I2C1_SCL_136") (pintype "bidirectional"))
    )
    (net (code "61") (name "LOCK_246") (class "Default")
      (node (ref "D18") (pin "3") (pinfunction "COMMON_3") (pintype "bidirectional"))
      (node (ref "R169") (pin "2") (pinfunction "2_2") (pintype "passive"))
      (node (ref "U7") (pin "137") (pinfunction "PB7/I2C1_SDA_137") (pintype "bidirectional"))
    )
    (net (code "62") (name "MOD_135") (class "Default")
      (node (ref "MOD135-SW") (pin "P$2") (pinfunction "P$2_P$2") (pintype "passive"))
      (node (ref "U7") (pin "86") (pinfunction "PD15/TIM4_CH4(5T)_86") (pintype "bidirectional"))
    )
    (net (code "63") (name "MOD_246") (class "Default")
      (node (ref "MOD246-SW") (pin "P$2") (pinfunction "P$2_P$2") (pintype "passive"))
      (node (ref "U7") (pin "48") (pinfunction "PB2/BOOT1_48") (pintype "bidirectional"))
    )
    (net (code "64") (name "MORPHADC") (class "Default")
      (node (ref "C43") (pin "1") (pinfunction "1_1") (pintype "passive"))
      (node (ref "D4") (pin "3") (pinfunction "COMMON_3") (pintype "bidirectional"))
      (node (ref "R20") (pin "2") (pinfunction "2_2") (pintype "passive"))
      (node (ref "R77") (pin "2") (pinfunction "2_2") (pintype "passive"))
      (node (ref "U7") (pin "34") (pinfunction "PA0/ETH_MII_CRS/ADC123_IN0_34") (pintype "bidirectional"))
    )
    (net (code "65") (name "Net-(BANDCV1-TIP)") (class "Default")
      (node (ref "BANDCV1") (pin "1") (pinfunction "TIP_1") (pintype "passive"))
      (node (ref "R68") (pin "2") (pinfunction "2_2") (pintype "passive"))
    )
    (net (code "66") (name "Net-(BANDCV1-TIP-SW)") (class "Default")
      (node (ref "BANDCV1") (pin "3") (pinfunction "TIP-SW_3") (pintype "passive"))
      (node (ref "R34") (pin "1") (pinfunction "1_1") (pintype "passive"))
    )
    (net (code "67") (name "Net-(BANDCV2-TIP)") (class "Default")
      (node (ref "BANDCV2") (pin "1") (pinfunction "TIP_1") (pintype "passive"))
      (node (ref "R69") (pin "2") (pinfunction "2_2") (pintype "passive"))
    )
    (net (code "68") (name "Net-(BANDCV2-TIP-SW)") (class "Default")
      (node (ref "BANDCV2") (pin "3") (pinfunction "TIP-SW_3") (pintype "passive"))
      (node (ref "R35") (pin "1") (pinfunction "1_1") (pintype "passive"))
    )
    (net (code "69") (name "Net-(BANDCV3-TIP)") (class "Default")
      (node (ref "BANDCV3") (pin "1") (pinfunction "TIP_1") (pintype "passive"))
      (node (ref "R70") (pin "2") (pinfunction "2_2") (pintype "passive"))
    )
    (net (code "70") (name "Net-(BANDCV3-TIP-SW)") (class "Default")
      (node (ref "BANDCV3") (pin "3") (pinfunction "TIP-SW_3") (pintype "passive"))
      (node (ref "R36") (pin "1") (pinfunction "1_1") (pintype "passive"))
    )
    (net (code "71") (name "Net-(BANDCV4-TIP)") (class "Default")
      (node (ref "BANDCV4") (pin "1") (pinfunction "TIP_1") (pintype "passive"))
      (node (ref "R71") (pin "2") (pinfunction "2_2") (pintype "passive"))
    )
    (net (code "72") (name "Net-(BANDCV4-TIP-SW)") (class "Default")
      (node (ref "BANDCV4") (pin "3") (pinfunction "TIP-SW_3") (pintype "passive"))
      (node (ref "R37") (pin "1") (pinfunction "1_1") (pintype "passive"))
    )
    (net (code "73") (name "Net-(BANDCV5-TIP)") (class "Default")
      (node (ref "BANDCV5") (pin "1") (pinfunction "TIP_1") (pintype "passive"))
      (node (ref "R72") (pin "2") (pinfunction "2_2") (pintype "passive"))
    )
    (net (code "74") (name "Net-(BANDCV5-TIP-SW)") (class "Default")
      (node (ref "BANDCV5") (pin "3") (pinfunction "TIP-SW_3") (pintype "passive"))
      (node (ref "R115") (pin "1") (pinfunction "1_1") (pintype "passive"))
    )
    (net (code "75") (name "Net-(BANDCV6-TIP)") (class "Default")
      (node (ref "BANDCV6") (pin "1") (pinfunction "TIP_1") (pintype "passive"))
      (node (ref "R73") (pin "2") (pinfunction "2_2") (pintype "passive"))
    )
    (net (code "76") (name "Net-(BANDCV6-TIP-SW)") (class "Default")
      (node (ref "BANDCV6") (pin "3") (pinfunction "TIP-SW_3") (pintype "passive"))
      (node (ref "R116") (pin "1") (pinfunction "1_1") (pintype "passive"))
    )
    (net (code "77") (name "Net-(C52-Pad2)") (class "Default")
      (node (ref "C52") (pin "2") (pinfunction "2_2") (pintype "passive"))
      (node (ref "R189") (pin "1") (pinfunction "1_1") (pintype "passive"))
      (node (ref "R3") (pin "2") (pinfunction "2_2") (pintype "passive"))
    )
    (net (code "78") (name "Net-(C53-Pad2)") (class "Default")
      (node (ref "C53") (pin "2") (pinfunction "2_2") (pintype "passive"))
      (node (ref "R190") (pin "1") (pinfunction "1_1") (pintype "passive"))
      (node (ref "R4") (pin "2") (pinfunction "2_2") (pintype "passive"))
    )
    (net (code "79") (name "Net-(D13-C)") (class "Default")
      (node (ref "D13") (pin "K") (pinfunction "C_K") (pintype "passive"))
      (node (ref "POWER") (pin "15") (pinfunction "P$15_15") (pintype "bidirectional"))
      (node (ref "POWER") (pin "16") (pinfunction "P$16_16") (pintype "bidirectional"))
    )
    (net (code "80") (name "Net-(ENC1A-P$1)") (class "Default")
      (node (ref "ENC1") (pin "1") (pinfunction "P$1_1") (pintype "bidirectional"))
      (node (ref "R60") (pin "2") (pinfunction "2_2") (pintype "passive"))
    )
    (net (code "81") (name "Net-(ENC1A-P$3)") (class "Default")
      (node (ref "ENC1") (pin "3") (pinfunction "P$3_3") (pintype "bidirectional"))
      (node (ref "R59") (pin "1") (pinfunction "1_1") (pintype "passive"))
    )
    (net (code "82") (name "Net-(ENC1B-P$1)") (class "Default")
      (node (ref "ENC1") (pin "SW1") (pinfunction "P$1_SW1") (pintype "passive"))
      (node (ref "R33") (pin "1") (pinfunction "1_1") (pintype "passive"))
    )
    (net (code "83") (name "Net-(ENV1-TIP)") (class "Default")
      (node (ref "ENV1") (pin "1") (pinfunction "TIP_1") (pintype "passive"))
      (node (ref "R8") (pin "1") (pinfunction "1_1") (pintype "passive"))
    )
    (net (code "84") (name "Net-(ENV2-TIP)") (class "Default")
      (node (ref "ENV2") (pin "1") (pinfunction "TIP_1") (pintype "passive"))
      (node (ref "R31") (pin "1") (pinfunction "1_1") (pintype "passive"))
    )
    (net (code "85") (name "Net-(ENV3-TIP)") (class "Default")
      (node (ref "ENV3") (pin "1") (pinfunction "TIP_1") (pintype "passive"))
      (node (ref "R51") (pin "1") (pinfunction "1_1") (pintype "passive"))
    )
    (net (code "86") (name "Net-(ENV4-TIP)") (class "Default")
      (node (ref "ENV4") (pin "1") (pinfunction "TIP_1") (pintype "passive"))
      (node (ref "R53") (pin "1") (pinfunction "1_1") (pintype "passive"))
    )
    (net (code "87") (name "Net-(ENV5-TIP)") (class "Default")
      (node (ref "ENV5") (pin "1") (pinfunction "TIP_1") (pintype "passive"))
      (node (ref "R55") (pin "1") (pinfunction "1_1") (pintype "passive"))
    )
    (net (code "88") (name "Net-(ENV6-TIP)") (class "Default")
      (node (ref "ENV6") (pin "1") (pinfunction "TIP_1") (pintype "passive"))
      (node (ref "R57") (pin "1") (pinfunction "1_1") (pintype "passive"))
    )
    (net (code "89") (name "Net-(FREQCV1-TIP)") (class "Default")
      (node (ref "FREQCV1") (pin "1") (pinfunction "TIP_1") (pintype "passive"))
      (node (ref "R126") (pin "1") (pinfunction "1_1") (pintype "passive"))
    )
    (net (code "90") (name "Net-(FREQCV6-TIP)") (class "Default")
      (node (ref "FREQCV6") (pin "1") (pinfunction "TIP_1") (pintype "passive"))
      (node (ref "R125") (pin "1") (pinfunction "1_1") (pintype "passive"))
    )
    (net (code "91") (name "Net-(IC1A--IN)") (class "Default")
      (node (ref "C6") (pin "2") (pinfunction "2_2") (pintype "passive"))
      (node (ref "IC1") (pin "2") (pinfunction "-IN_2") (pintype "input"))
      (node (ref "R186") (pin "1") (pinfunction "1_1") (pintype "passive"))
      (node (ref "R93") (pin "2") (pinfunction "2_2") (pintype "passive"))
    )
    (net (code "92") (name "Net-(IC1A-OUT)") (class "Default")
      (node (ref "C2") (pin "2") (pinfunction "2_2") (pintype "passive"))
      (node (ref "C6") (pin "1") (pinfunction "1_1") (pintype "passive"))
      (node (ref "IC1") (pin "1") (pinfunction "OUT_1") (pintype "output"))
      (node (ref "R186") (pin "2") (pinfunction "2_2") (pintype "passive"))
    )
    (net (code "93") (name "Net-(IC1B--IN)") (class "Default")
      (node (ref "C5") (pin "2") (pinfunction "2_2") (pintype "passive"))
      (node (ref "IC1") (pin "6") (pinfunction "-IN_6") (pintype "input"))
      (node (ref "R185") (pin "1") (pinfunction "1_1") (pintype "passive"))
      (node (ref "R92") (pin "2") (pinfunction "2_2") (pintype "passive"))
    )
    (net (code "94") (name "Net-(IC1B-OUT)") (class "Default")
      (node (ref "C1") (pin "2") (pinfunction "2_2") (pintype "passive"))
      (node (ref "C5") (pin "1") (pinfunction "1_1") (pintype "passive"))
      (node (ref "IC1") (pin "7") (pinfunction "OUT_7") (pintype "output"))
      (node (ref "R185") (pin "2") (pinfunction "2_2") (pintype "passive"))
    )
    (net (code "95") (name "Net-(IC2A-+IN)") (class "Default")
      (node (ref "C13") (pin "1") (pinfunction "1_1") (pintype "passive"))
      (node (ref "IC2") (pin "3") (pinfunction "+IN_3") (pintype "input"))
      (node (ref "R9") (pin "1") (pinfunction "1_1") (pintype "passive"))
    )
    (net (code "96") (name "Net-(IC2A--IN)") (class "Default")
      (node (ref "IC2") (pin "2") (pinfunction "-IN_2") (pintype "input"))
      (node (ref "R80") (pin "2") (pinfunction "2_2") (pintype "passive"))
      (node (ref "R82") (pin "1") (pinfunction "1_1") (pintype "passive"))
    )
    (net (code "97") (name "Net-(IC2A-OUT)") (class "Default")
      (node (ref "IC2") (pin "1") (pinfunction "OUT_1") (pintype "output"))
      (node (ref "R8") (pin "2") (pinfunction "2_2") (pintype "passive"))
      (node (ref "R80") (pin "1") (pinfunction "1_1") (pintype "passive"))
    )
    (net (code "98") (name "Net-(IC2B-+IN)") (class "Default")
      (node (ref "C15") (pin "1") (pinfunction "1_1") (pintype "passive"))
      (node (ref "IC2") (pin "5") (pinfunction "+IN_5") (pintype "input"))
      (node (ref "R32") (pin "1") (pinfunction "1_1") (pintype "passive"))
    )
    (net (code "99") (name "Net-(IC2B--IN)") (class "Default")
      (node (ref "IC2") (pin "6") (pinfunction "-IN_6") (pintype "input"))
      (node (ref "R81") (pin "2") (pinfunction "2_2") (pintype "passive"))
      (node (ref "R83") (pin "1") (pinfunction "1_1") (pintype "passive"))
    )
    (net (code "100") (name "Net-(IC2B-OUT)") (class "Default")
      (node (ref "IC2") (pin "7") (pinfunction "OUT_7") (pintype "output"))
      (node (ref "R31") (pin "2") (pinfunction "2_2") (pintype "passive"))
      (node (ref "R81") (pin "1") (pinfunction "1_1") (pintype "passive"))
    )
    (net (code "101") (name "Net-(IC3A-+IN)") (class "Default")
      (node (ref "C36") (pin "1") (pinfunction "1_1") (pintype "passive"))
      (node (ref "IC3") (pin "3") (pinfunction "+IN_3") (pintype "input"))
      (node (ref "R52") (pin "1") (pinfunction "1_1") (pintype "passive"))
    )
    (net (code "102") (name "Net-(IC3A--IN)") (class "Default")
      (node (ref "IC3") (pin "2") (pinfunction "-IN_2") (pintype "input"))
      (node (ref "R86") (pin "2") (pinfunction "2_2") (pintype "passive"))
      (node (ref "R87") (pin "1") (pinfunction "1_1") (pintype "passive"))
    )
    (net (code "103") (name "Net-(IC3A-OUT)") (class "Default")
      (node (ref "IC3") (pin "1") (pinfunction "OUT_1") (pintype "output"))
      (node (ref "R51") (pin "2") (pinfunction "2_2") (pintype "passive"))
      (node (ref "R86") (pin "1") (pinfunction "1_1") (pintype "passive"))
    )
    (net (code "104") (name "Net-(IC3B-+IN)") (class "Default")
      (node (ref "C38") (pin "1") (pinfunction "1_1") (pintype "passive"))
      (node (ref "IC3") (pin "5") (pinfunction "+IN_5") (pintype "input"))
      (node (ref "R54") (pin "1") (pinfunction "1_1") (pintype "passive"))
    )
    (net (code "105") (name "Net-(IC3B--IN)") (class "Default")
      (node (ref "IC3") (pin "6") (pinfunction "-IN_6") (pintype "input"))
      (node (ref "R84") (pin "2") (pinfunction "2_2") (pintype "passive"))
      (node (ref "R85") (pin "1") (pinfunction "1_1") (pintype "passive"))
    )
    (net (code "106") (name "Net-(IC3B-OUT)") (class "Default")
      (node (ref "IC3") (pin "7") (pinfunction "OUT_7") (pintype "output"))
      (node (ref "R53") (pin "2") (pinfunction "2_2") (pintype "passive"))
      (node (ref "R84") (pin "1") (pinfunction "1_1") (pintype "passive"))
    )
    (net (code "107") (name "Net-(IC4A-+IN)") (class "Default")
      (node (ref "C40") (pin "1") (pinfunction "1_1") (pintype "passive"))
      (node (ref "IC4") (pin "3") (pinfunction "+IN_3") (pintype "input"))
      (node (ref "R56") (pin "1") (pinfunction "1_1") (pintype "passive"))
    )
    (net (code "108") (name "Net-(IC4A--IN)") (class "Default")
      (node (ref "IC4") (pin "2") (pinfunction "-IN_2") (pintype "input"))
      (node (ref "R90") (pin "2") (pinfunction "2_2") (pintype "passive"))
      (node (ref "R91") (pin "1") (pinfunction "1_1") (pintype "passive"))
    )
    (net (code "109") (name "Net-(IC4A-OUT)") (class "Default")
      (node (ref "IC4") (pin "1") (pinfunction "OUT_1") (pintype "output"))
      (node (ref "R55") (pin "2") (pinfunction "2_2") (pintype "passive"))
      (node (ref "R90") (pin "1") (pinfunction "1_1") (pintype "passive"))
    )
    (net (code "110") (name "Net-(IC4B-+IN)") (class "Default")
      (node (ref "C42") (pin "1") (pinfunction "1_1") (pintype "passive"))
      (node (ref "IC4") (pin "5") (pinfunction "+IN_5") (pintype "input"))
      (node (ref "R58") (pin "1") (pinfunction "1_1") (pintype "passive"))
    )
    (net (code "111") (name "Net-(IC4B--IN)") (class "Default")
      (node (ref "IC4") (pin "6") (pinfunction "-IN_6") (pintype "input"))
      (node (ref "R88") (pin "2") (pinfunction "2_2") (pintype "passive"))
      (node (ref "R89") (pin "1") (pinfunction "1_1") (pintype "passive"))
    )
    (net (code "112") (name "Net-(IC4B-OUT)") (class "Default")
      (node (ref "IC4") (pin "7") (pinfunction "OUT_7") (pintype "output"))
      (node (ref "R57") (pin "2") (pinfunction "2_2") (pintype "passive"))
      (node (ref "R88") (pin "1") (pinfunction "1_1") (pintype "passive"))
    )
    (net (code "113") (name "Net-(IC5A-+IN)") (class "Default")
      (node (ref "C14") (pin "1") (pinfunction "1_1") (pintype "passive"))
      (node (ref "IC5") (pin "3") (pinfunction "+IN_3") (pintype "input"))
      (node (ref "IC5") (pin "5") (pinfunction "+IN_5") (pintype "input"))
      (node (ref "R183") (pin "1") (pinfunction "1_1") (pintype "passive"))
      (node (ref "R191") (pin "2") (pinfunction "2_2") (pintype "passive"))
      (node (ref "R194") (pin "2") (pinfunction "2_2") (pintype "passive"))
    )
    (net (code "114") (name "Net-(IC5A--IN)") (class "Default")
      (node (ref "C54") (pin "2") (pinfunction "2_2") (pintype "passive"))
      (node (ref "IC5") (pin "2") (pinfunction "-IN_2") (pintype "input"))
      (node (ref "R61") (pin "1") (pinfunction "1_1") (pintype "passive"))
      (node (ref "R63") (pin "2") (pinfunction "2_2") (pintype "passive"))
    )
    (net (code "115") (name "Net-(IC5A-OUT)") (class "Default")
      (node (ref "C52") (pin "1") (pinfunction "1_1") (pintype "passive"))
      (node (ref "C54") (pin "1") (pinfunction "1_1") (pintype "passive"))
      (node (ref "IC5") (pin "1") (pinfunction "OUT_1") (pintype "output"))
      (node (ref "R61") (pin "2") (pinfunction "2_2") (pintype "passive"))
    )
    (net (code "116") (name "Net-(IC5B--IN)") (class "Default")
      (node (ref "C55") (pin "2") (pinfunction "2_2") (pintype "passive"))
      (node (ref "IC5") (pin "6") (pinfunction "-IN_6") (pintype "input"))
      (node (ref "R62") (pin "1") (pinfunction "1_1") (pintype "passive"))
      (node (ref "R64") (pin "2") (pinfunction "2_2") (pintype "passive"))
    )
    (net (code "117") (name "Net-(IC5B-OUT)") (class "Default")
      (node (ref "C53") (pin "1") (pinfunction "1_1") (pintype "passive"))
      (node (ref "C55") (pin "1") (pinfunction "1_1") (pintype "passive"))
      (node (ref "IC5") (pin "7") (pinfunction "OUT_7") (pintype "output"))
      (node (ref "R62") (pin "2") (pinfunction "2_2") (pintype "passive"))
    )
    (net (code "118") (name "Net-(IC6A-+IN)") (class "Default")
      (node (ref "IC6") (pin "3") (pinfunction "+IN_3") (pintype "input"))
      (node (ref "R74") (pin "2") (pinfunction "2_2") (pintype "passive"))
    )
    (net (code "119") (name "Net-(IC6A--IN)") (class "Default")
      (node (ref "IC6") (pin "1") (pinfunction "OUT_1") (pintype "output"))
      (node (ref "IC6") (pin "2") (pinfunction "-IN_2") (pintype "input"))
      (node (ref "R77") (pin "1") (pinfunction "1_1") (pintype "passive"))
    )
    (net (code "120") (name "Net-(IC6B-+IN)") (class "Default")
      (node (ref "IC6") (pin "5") (pinfunction "+IN_5") (pintype "input"))
      (node (ref "R75") (pin "2") (pinfunction "2_2") (pintype "passive"))
    )
    (net (code "121") (name "Net-(IC6B--IN)") (class "Default")
      (node (ref "IC6") (pin "6") (pinfunction "-IN_6") (pintype "input"))
      (node (ref "IC6") (pin "7") (pinfunction "OUT_7") (pintype "output"))
      (node (ref "R78") (pin "1") (pinfunction "1_1") (pintype "passive"))
    )
    (net (code "122") (name "Net-(IC8A-+IN)") (class "Default")
      (node (ref "IC8") (pin "3") (pinfunction "+IN_3") (pintype "input"))
      (node (ref "R188") (pin "1") (pinfunction "1_1") (pintype "passive"))
      (node (ref "R2") (pin "2") (pinfunction "2_2") (pintype "passive"))
    )
    (net (code "123") (name "Net-(IC8A--IN)") (class "Default")
      (node (ref "IC8") (pin "1") (pinfunction "OUT_1") (pintype "output"))
      (node (ref "IC8") (pin "2") (pinfunction "-IN_2") (pintype "input"))
      (node (ref "R93") (pin "1") (pinfunction "1_1") (pintype "passive"))
    )
    (net (code "124") (name "Net-(IC8B-+IN)") (class "Default")
      (node (ref "IC8") (pin "5") (pinfunction "+IN_5") (pintype "input"))
      (node (ref "R1") (pin "2") (pinfunction "2_2") (pintype "passive"))
      (node (ref "R187") (pin "1") (pinfunction "1_1") (pintype "passive"))
    )
    (net (code "125") (name "Net-(IC8B--IN)") (class "Default")
      (node (ref "IC8") (pin "6") (pinfunction "-IN_6") (pintype "input"))
      (node (ref "IC8") (pin "7") (pinfunction "OUT_7") (pintype "output"))
      (node (ref "R92") (pin "1") (pinfunction "1_1") (pintype "passive"))
    )
    (net (code "126") (name "Net-(IC10-IN)") (class "Default")
      (node (ref "C75") (pin "1") (pinfunction "1_1") (pintype "passive"))
      (node (ref "IC10") (pin "3") (pinfunction "IN_3") (pintype "input"))
      (node (ref "V-SEL") (pin "P$2") (pinfunction "P$2_P$2") (pintype "bidirectional"))
    )
    (net (code "127") (name "Net-(IN-1-TIP)") (class "Default")
      (node (ref "IN-1") (pin "1") (pinfunction "TIP_1") (pintype "passive"))
      (node (ref "IN-2") (pin "3") (pinfunction "TIP-SW_3") (pintype "passive"))
      (node (ref "R1") (pin "1") (pinfunction "1_1") (pintype "passive"))
    )
    (net (code "128") (name "Net-(IN-2-TIP)") (class "Default")
      (node (ref "IN-2") (pin "1") (pinfunction "TIP_1") (pintype "passive"))
      (node (ref "R2") (pin "1") (pinfunction "1_1") (pintype "passive"))
    )
    (net (code "129") (name "Net-(LED-INCLIP-AG)") (class "Default")
      (node (ref "LED-INCLIP") (pin "A-3") (pinfunction "AG_A-3") (pintype "passive"))
      (node (ref "R67") (pin "2") (pinfunction "2_2") (pintype "passive"))
    )
    (net (code "130") (name "Net-(LED-INCLIP-AR)") (class "Default")
      (node (ref "LED-INCLIP") (pin "A-1") (pinfunction "AR_A-1") (pintype "passive"))
      (node (ref "R7") (pin "1") (pinfunction "1_1") (pintype "passive"))
    )
    (net (code "131") (name "Net-(LED1-CB)") (class "Default")
      (node (ref "LED1") (pin "P$3") (pinfunction "CB_P$3") (pintype "passive"))
      (node (ref "R167") (pin "2") (pinfunction "2_2") (pintype "passive"))
    )
    (net (code "132") (name "Net-(LED1-CG)") (class "Default")
      (node (ref "LED1") (pin "P$4") (pinfunction "CG_P$4") (pintype "passive"))
      (node (ref "R166") (pin "2") (pinfunction "2_2") (pintype "passive"))
    )
    (net (code "133") (name "Net-(LED1-CR)") (class "Default")
      (node (ref "LED1") (pin "P$1") (pinfunction "CR_P$1") (pintype "passive"))
      (node (ref "R153") (pin "2") (pinfunction "2_2") (pintype "passive"))
    )
    (net (code "134") (name "Net-(LED2-CB)") (class "Default")
      (node (ref "LED2") (pin "P$3") (pinfunction "CB_P$3") (pintype "passive"))
      (node (ref "R165") (pin "2") (pinfunction "2_2") (pintype "passive"))
    )
    (net (code "135") (name "Net-(LED2-CG)") (class "Default")
      (node (ref "LED2") (pin "P$4") (pinfunction "CG_P$4") (pintype "passive"))
      (node (ref "R164") (pin "2") (pinfunction "2_2") (pintype "passive"))
    )
    (net (code "136") (name "Net-(LED2-CR)") (class "Default")
      (node (ref "LED2") (pin "P$1") (pinfunction "CR_P$1") (pintype "passive"))
      (node (ref "R163") (pin "2") (pinfunction "2_2") (pintype "passive"))
    )
    (net (code "137") (name "Net-(LED3-CB)") (class "Default")
      (node (ref "LED3") (pin "P$3") (pinfunction "CB_P$3") (pintype "passive"))
      (node (ref "R156") (pin "2") (pinfunction "2_2") (pintype "passive"))
    )
    (net (code "138") (name "Net-(LED3-CG)") (class "Default")
      (node (ref "LED3") (pin "P$4") (pinfunction "CG_P$4") (pintype "passive"))
      (node (ref "R155") (pin "2") (pinfunction "2_2") (pintype "passive"))
    )
    (net (code "139") (name "Net-(LED3-CR)") (class "Default")
      (node (ref "LED3") (pin "P$1") (pinfunction "CR_P$1") (pintype "passive"))
      (node (ref "R154") (pin "2") (pinfunction "2_2") (pintype "passive"))
    )
    (net (code "140") (name "Net-(LED4-CB)") (class "Default")
      (node (ref "LED4") (pin "P$3") (pinfunction "CB_P$3") (pintype "passive"))
      (node (ref "R159") (pin "2") (pinfunction "2_2") (pintype "passive"))
    )
    (net (code "141") (name "Net-(LED4-CG)") (class "Default")
      (node (ref "LED4") (pin "P$4") (pinfunction "CG_P$4") (pintype "passive"))
      (node (ref "R158") (pin "2") (pinfunction "2_2") (pintype "passive"))
    )
    (net (code "142") (name "Net-(LED4-CR)") (class "Default")
      (node (ref "LED4") (pin "P$1") (pinfunction "CR_P$1") (pintype "passive"))
      (node (ref "R157") (pin "2") (pinfunction "2_2") (pintype "passive"))
    )
    (net (code "143") (name "Net-(LED5-CB)") (class "Default")
      (node (ref "LED5") (pin "P$3") (pinfunction "CB_P$3") (pintype "passive"))
      (node (ref "R162") (pin "2") (pinfunction "2_2") (pintype "passive"))
    )
    (net (code "144") (name "Net-(LED5-CG)") (class "Default")
      (node (ref "LED5") (pin "P$4") (pinfunction "CG_P$4") (pintype "passive"))
      (node (ref "R161") (pin "2") (pinfunction "2_2") (pintype "passive"))
    )
    (net (code "145") (name "Net-(LED5-CR)") (class "Default")
      (node (ref "LED5") (pin "P$1") (pinfunction "CR_P$1") (pintype "passive"))
      (node (ref "R160") (pin "2") (pinfunction "2_2") (pintype "passive"))
    )
    (net (code "146") (name "Net-(LED6-CB)") (class "Default")
      (node (ref "LED6") (pin "P$3") (pinfunction "CB_P$3") (pintype "passive"))
      (node (ref "R131") (pin "2") (pinfunction "2_2") (pintype "passive"))
    )
    (net (code "147") (name "Net-(LED6-CG)") (class "Default")
      (node (ref "LED6") (pin "P$4") (pinfunction "CG_P$4") (pintype "passive"))
      (node (ref "R11") (pin "2") (pinfunction "2_2") (pintype "passive"))
    )
    (net (code "148") (name "Net-(LED6-CR)") (class "Default")
      (node (ref "LED6") (pin "P$1") (pinfunction "CR_P$1") (pintype "passive"))
      (node (ref "R10") (pin "2") (pinfunction "2_2") (pintype "passive"))
    )
    (net (code "149") (name "Net-(LED7-CB)") (class "Default")
      (node (ref "LED7") (pin "P$3") (pinfunction "CB_P$3") (pintype "passive"))
      (node (ref "R114") (pin "2") (pinfunction "2_2") (pintype "passive"))
    )
    (net (code "150") (name "Net-(LED7-CG)") (class "Default")
      (node (ref "LED7") (pin "P$4") (pinfunction "CG_P$4") (pintype "passive"))
      (node (ref "R113") (pin "2") (pinfunction "2_2") (pintype "passive"))
    )
    (net (code "151") (name "Net-(LED7-CR)") (class "Default")
      (node (ref "LED7") (pin "P$1") (pinfunction "CR_P$1") (pintype "passive"))
      (node (ref "R112") (pin "2") (pinfunction "2_2") (pintype "passive"))
    )
    (net (code "152") (name "Net-(LED8-CB)") (class "Default")
      (node (ref "LED8") (pin "P$3") (pinfunction "CB_P$3") (pintype "passive"))
      (node (ref "R96") (pin "2") (pinfunction "2_2") (pintype "passive"))
    )
    (net (code "153") (name "Net-(LED8-CG)") (class "Default")
      (node (ref "LED8") (pin "P$4") (pinfunction "CG_P$4") (pintype "passive"))
      (node (ref "R95") (pin "2") (pinfunction "2_2") (pintype "passive"))
    )
    (net (code "154") (name "Net-(LED8-CR)") (class "Default")
      (node (ref "LED8") (pin "P$1") (pinfunction "CR_P$1") (pintype "passive"))
      (node (ref "R94") (pin "2") (pinfunction "2_2") (pintype "passive"))
    )
    (net (code "155") (name "Net-(LED9-CB)") (class "Default")
      (node (ref "LED9") (pin "P$3") (pinfunction "CB_P$3") (pintype "passive"))
      (node (ref "R99") (pin "2") (pinfunction "2_2") (pintype "passive"))
    )
    (net (code "156") (name "Net-(LED9-CG)") (class "Default")
      (node (ref "LED9") (pin "P$4") (pinfunction "CG_P$4") (pintype "passive"))
      (node (ref "R98") (pin "2") (pinfunction "2_2") (pintype "passive"))
    )
    (net (code "157") (name "Net-(LED9-CR)") (class "Default")
      (node (ref "LED9") (pin "P$1") (pinfunction "CR_P$1") (pintype "passive"))
      (node (ref "R97") (pin "2") (pinfunction "2_2") (pintype "passive"))
    )
    (net (code "158") (name "Net-(LED10-CB)") (class "Default")
      (node (ref "LED10") (pin "P$3") (pinfunction "CB_P$3") (pintype "passive"))
      (node (ref "R102") (pin "2") (pinfunction "2_2") (pintype "passive"))
    )
    (net (code "159") (name "Net-(LED10-CG)") (class "Default")
      (node (ref "LED10") (pin "P$4") (pinfunction "CG_P$4") (pintype "passive"))
      (node (ref "R101") (pin "2") (pinfunction "2_2") (pintype "passive"))
    )
    (net (code "160") (name "Net-(LED10-CR)") (class "Default")
      (node (ref "LED10") (pin "P$1") (pinfunction "CR_P$1") (pintype "passive"))
      (node (ref "R100") (pin "2") (pinfunction "2_2") (pintype "passive"))
    )
    (net (code "161") (name "Net-(LED11-CB)") (class "Default")
      (node (ref "LED11") (pin "P$3") (pinfunction "CB_P$3") (pintype "passive"))
      (node (ref "R105") (pin "2") (pinfunction "2_2") (pintype "passive"))
    )
    (net (code "162") (name "Net-(LED11-CG)") (class "Default")
      (node (ref "LED11") (pin "P$4") (pinfunction "CG_P$4") (pintype "passive"))
      (node (ref "R104") (pin "2") (pinfunction "2_2") (pintype "passive"))
    )
    (net (code "163") (name "Net-(LED11-CR)") (class "Default")
      (node (ref "LED11") (pin "P$1") (pinfunction "CR_P$1") (pintype "passive"))
      (node (ref "R103") (pin "2") (pinfunction "2_2") (pintype "passive"))
    )
    (net (code "164") (name "Net-(LED12-CB)") (class "Default")
      (node (ref "LED12") (pin "P$3") (pinfunction "CB_P$3") (pintype "passive"))
      (node (ref "R108") (pin "2") (pinfunction "2_2") (pintype "passive"))
    )
    (net (code "165") (name "Net-(LED12-CG)") (class "Default")
      (node (ref "LED12") (pin "P$4") (pinfunction "CG_P$4") (pintype "passive"))
      (node (ref "R107") (pin "2") (pinfunction "2_2") (pintype "passive"))
    )
    (net (code "166") (name "Net-(LED12-CR)") (class "Default")
      (node (ref "LED12") (pin "P$1") (pinfunction "CR_P$1") (pintype "passive"))
      (node (ref "R106") (pin "2") (pinfunction "2_2") (pintype "passive"))
    )
    (net (code "167") (name "Net-(LED13-CB)") (class "Default")
      (node (ref "LED13") (pin "P$3") (pinfunction "CB_P$3") (pintype "passive"))
      (node (ref "R111") (pin "2") (pinfunction "2_2") (pintype "passive"))
    )
    (net (code "168") (name "Net-(LED13-CG)") (class "Default")
      (node (ref "LED13") (pin "P$4") (pinfunction "CG_P$4") (pintype "passive"))
      (node (ref "R110") (pin "2") (pinfunction "2_2") (pintype "passive"))
    )
    (net (code "169") (name "Net-(LED13-CR)") (class "Default")
      (node (ref "LED13") (pin "P$1") (pinfunction "CR_P$1") (pintype "passive"))
      (node (ref "R109") (pin "2") (pinfunction "2_2") (pintype "passive"))
    )
    (net (code "170") (name "Net-(LED14-CB)") (class "Default")
      (node (ref "LED14") (pin "P$3") (pinfunction "CB_P$3") (pintype "passive"))
      (node (ref "R134") (pin "2") (pinfunction "2_2") (pintype "passive"))
    )
    (net (code "171") (name "Net-(LED14-CG)") (class "Default")
      (node (ref "LED14") (pin "P$4") (pinfunction "CG_P$4") (pintype "passive"))
      (node (ref "R133") (pin "2") (pinfunction "2_2") (pintype "passive"))
    )
    (net (code "172") (name "Net-(LED14-CR)") (class "Default")
      (node (ref "LED14") (pin "P$1") (pinfunction "CR_P$1") (pintype "passive"))
      (node (ref "R132") (pin "2") (pinfunction "2_2") (pintype "passive"))
    )
    (net (code "173") (name "Net-(LED15-CB)") (class "Default")
      (node (ref "LED15") (pin "P$3") (pinfunction "CB_P$3") (pintype "passive"))
      (node (ref "R137") (pin "2") (pinfunction "2_2") (pintype "passive"))
    )
    (net (code "174") (name "Net-(LED15-CG)") (class "Default")
      (node (ref "LED15") (pin "P$4") (pinfunction "CG_P$4") (pintype "passive"))
      (node (ref "R136") (pin "2") (pinfunction "2_2") (pintype "passive"))
    )
    (net (code "175") (name "Net-(LED15-CR)") (class "Default")
      (node (ref "LED15") (pin "P$1") (pinfunction "CR_P$1") (pintype "passive"))
      (node (ref "R135") (pin "2") (pinfunction "2_2") (pintype "passive"))
    )
    (net (code "176") (name "Net-(LED16-CB)") (class "Default")
      (node (ref "LED16") (pin "P$3") (pinfunction "CB_P$3") (pintype "passive"))
      (node (ref "R140") (pin "2") (pinfunction "2_2") (pintype "passive"))
    )
    (net (code "177") (name "Net-(LED16-CG)") (class "Default")
      (node (ref "LED16") (pin "P$4") (pinfunction "CG_P$4") (pintype "passive"))
      (node (ref "R139") (pin "2") (pinfunction "2_2") (pintype "passive"))
    )
    (net (code "178") (name "Net-(LED16-CR)") (class "Default")
      (node (ref "LED16") (pin "P$1") (pinfunction "CR_P$1") (pintype "passive"))
      (node (ref "R138") (pin "2") (pinfunction "2_2") (pintype "passive"))
    )
    (net (code "179") (name "Net-(LED17-CB)") (class "Default")
      (node (ref "LED17") (pin "P$3") (pinfunction "CB_P$3") (pintype "passive"))
      (node (ref "R143") (pin "2") (pinfunction "2_2") (pintype "passive"))
    )
    (net (code "180") (name "Net-(LED17-CG)") (class "Default")
      (node (ref "LED17") (pin "P$4") (pinfunction "CG_P$4") (pintype "passive"))
      (node (ref "R142") (pin "2") (pinfunction "2_2") (pintype "passive"))
    )
    (net (code "181") (name "Net-(LED17-CR)") (class "Default")
      (node (ref "LED17") (pin "P$1") (pinfunction "CR_P$1") (pintype "passive"))
      (node (ref "R141") (pin "2") (pinfunction "2_2") (pintype "passive"))
    )
    (net (code "182") (name "Net-(LED18-CB)") (class "Default")
      (node (ref "LED18") (pin "P$3") (pinfunction "CB_P$3") (pintype "passive"))
      (node (ref "R146") (pin "2") (pinfunction "2_2") (pintype "passive"))
    )
    (net (code "183") (name "Net-(LED18-CG)") (class "Default")
      (node (ref "LED18") (pin "P$4") (pinfunction "CG_P$4") (pintype "passive"))
      (node (ref "R145") (pin "2") (pinfunction "2_2") (pintype "passive"))
    )
    (net (code "184") (name "Net-(LED18-CR)") (class "Default")
      (node (ref "LED18") (pin "P$1") (pinfunction "CR_P$1") (pintype "passive"))
      (node (ref "R144") (pin "2") (pinfunction "2_2") (pintype "passive"))
    )
    (net (code "185") (name "Net-(LED19-CB)") (class "Default")
      (node (ref "LED19") (pin "P$3") (pinfunction "CB_P$3") (pintype "passive"))
      (node (ref "R149") (pin "2") (pinfunction "2_2") (pintype "passive"))
    )
    (net (code "186") (name "Net-(LED19-CG)") (class "Default")
      (node (ref "LED19") (pin "P$4") (pinfunction "CG_P$4") (pintype "passive"))
      (node (ref "R148") (pin "2") (pinfunction "2_2") (pintype "passive"))
    )
    (net (code "187") (name "Net-(LED19-CR)") (class "Default")
      (node (ref "LED19") (pin "P$1") (pinfunction "CR_P$1") (pintype "passive"))
      (node (ref "R147") (pin "2") (pinfunction "2_2") (pintype "passive"))
    )
    (net (code "188") (name "Net-(LED20-CB)") (class "Default")
      (node (ref "LED20") (pin "P$3") (pinfunction "CB_P$3") (pintype "passive"))
      (node (ref "R152") (pin "2") (pinfunction "2_2") (pintype "passive"))
    )
    (net (code "189") (name "Net-(LED20-CG)") (class "Default")
      (node (ref "LED20") (pin "P$4") (pinfunction "CG_P$4") (pintype "passive"))
      (node (ref "R151") (pin "2") (pinfunction "2_2") (pintype "passive"))
    )
    (net (code "190") (name "Net-(LED20-CR)") (class "Default")
      (node (ref "LED20") (pin "P$1") (pinfunction "CR_P$1") (pintype "passive"))
      (node (ref "R150") (pin "2") (pinfunction "2_2") (pintype "passive"))
    )
    (net (code "191") (name "Net-(LED21-CB)") (class "Default")
      (node (ref "LED21") (pin "P$3") (pinfunction "CB_P$3") (pintype "passive"))
      (node (ref "R14") (pin "2") (pinfunction "2_2") (pintype "passive"))
    )
    (net (code "192") (name "Net-(LED21-CG)") (class "Default")
      (node (ref "LED21") (pin "P$4") (pinfunction "CG_P$4") (pintype "passive"))
      (node (ref "R13") (pin "2") (pinfunction "2_2") (pintype "passive"))
    )
    (net (code "193") (name "Net-(LED21-CR)") (class "Default")
      (node (ref "LED21") (pin "P$1") (pinfunction "CR_P$1") (pintype "passive"))
      (node (ref "R12") (pin "2") (pinfunction "2_2") (pintype "passive"))
    )
    (net (code "194") (name "Net-(LED22-CB)") (class "Default")
      (node (ref "LED22") (pin "P$3") (pinfunction "CB_P$3") (pintype "passive"))
      (node (ref "R30") (pin "2") (pinfunction "2_2") (pintype "passive"))
    )
    (net (code "195") (name "Net-(LED22-CG)") (class "Default")
      (node (ref "LED22") (pin "P$4") (pinfunction "CG_P$4") (pintype "passive"))
      (node (ref "R29") (pin "2") (pinfunction "2_2") (pintype "passive"))
    )
    (net (code "196") (name "Net-(LED22-CR)") (class "Default")
      (node (ref "LED22") (pin "P$1") (pinfunction "CR_P$1") (pintype "passive"))
      (node (ref "R15") (pin "2") (pinfunction "2_2") (pintype "passive"))
    )
    (net (code "197") (name "Net-(LED23-CB)") (class "Default")
      (node (ref "LED23") (pin "P$3") (pinfunction "CB_P$3") (pintype "passive"))
      (node (ref "R174") (pin "2") (pinfunction "2_2") (pintype "passive"))
    )
    (net (code "198") (name "Net-(LED23-CG)") (class "Default")
      (node (ref "LED23") (pin "P$4") (pinfunction "CG_P$4") (pintype "passive"))
      (node (ref "R173") (pin "2") (pinfunction "2_2") (pintype "passive"))
    )
    (net (code "199") (name "Net-(LED23-CR)") (class "Default")
      (node (ref "LED23") (pin "P$1") (pinfunction "CR_P$1") (pintype "passive"))
      (node (ref "R79") (pin "2") (pinfunction "2_2") (pintype "passive"))
    )
    (net (code "200") (name "Net-(LED24-CB)") (class "Default")
      (node (ref "LED24") (pin "P$3") (pinfunction "CB_P$3") (pintype "passive"))
      (node (ref "R177") (pin "2") (pinfunction "2_2") (pintype "passive"))
    )
    (net (code "201") (name "Net-(LED24-CG)") (class "Default")
      (node (ref "LED24") (pin "P$4") (pinfunction "CG_P$4") (pintype "passive"))
      (node (ref "R176") (pin "2") (pinfunction "2_2") (pintype "passive"))
    )
    (net (code "202") (name "Net-(LED24-CR)") (class "Default")
      (node (ref "LED24") (pin "P$1") (pinfunction "CR_P$1") (pintype "passive"))
      (node (ref "R175") (pin "2") (pinfunction "2_2") (pintype "passive"))
    )
    (net (code "203") (name "Net-(LED25-CB)") (class "Default")
      (node (ref "LED25") (pin "P$3") (pinfunction "CB_P$3") (pintype "passive"))
      (node (ref "R180") (pin "2") (pinfunction "2_2") (pintype "passive"))
    )
    (net (code "204") (name "Net-(LED25-CG)") (class "Default")
      (node (ref "LED25") (pin "P$4") (pinfunction "CG_P$4") (pintype "passive"))
      (node (ref "R179") (pin "2") (pinfunction "2_2") (pintype "passive"))
    )
    (net (code "205") (name "Net-(LED25-CR)") (class "Default")
      (node (ref "LED25") (pin "P$1") (pinfunction "CR_P$1") (pintype "passive"))
      (node (ref "R178") (pin "2") (pinfunction "2_2") (pintype "passive"))
    )
    (net (code "206") (name "Net-(LED26-CB)") (class "Default")
      (node (ref "LED26") (pin "P$3") (pinfunction "CB_P$3") (pintype "passive"))
      (node (ref "R184") (pin "2") (pinfunction "2_2") (pintype "passive"))
    )
    (net (code "207") (name "Net-(LED26-CG)") (class "Default")
      (node (ref "LED26") (pin "P$4") (pinfunction "CG_P$4") (pintype "passive"))
      (node (ref "R182") (pin "2") (pinfunction "2_2") (pintype "passive"))
    )
    (net (code "208") (name "Net-(LED26-CR)") (class "Default")
      (node (ref "LED26") (pin "P$1") (pinfunction "CR_P$1") (pintype "passive"))
      (node (ref "R181") (pin "2") (pinfunction "2_2") (pintype "passive"))
    )
    (net (code "209") (name "Net-(LOCK1-PadP$5)") (class "Default")
      (node (ref "LOCK1") (pin "P$5") (pinfunction "P$5_P$5") (pintype "bidirectional"))
      (node (ref "R46") (pin "2") (pinfunction "2_2") (pintype "passive"))
    )
    (net (code "210") (name "Net-(LOCK1-PadP$7)") (class "Default")
      (node (ref "LOCK1") (pin "P$7") (pinfunction "P$7_P$7") (pintype "bidirectional"))
      (node (ref "R44") (pin "2") (pinfunction "2_2") (pintype "passive"))
    )
    (net (code "211") (name "Net-(LOCK2-PadP$5)") (class "Default")
      (node (ref "LOCK2") (pin "P$5") (pinfunction "P$5_P$5") (pintype "bidirectional"))
      (node (ref "R117") (pin "2") (pinfunction "2_2") (pintype "passive"))
    )
    (net (code "212") (name "Net-(LOCK2-PadP$7)") (class "Default")
      (node (ref "LOCK2") (pin "P$7") (pinfunction "P$7_P$7") (pintype "bidirectional"))
      (node (ref "R50") (pin "2") (pinfunction "2_2") (pintype "passive"))
    )
    (net (code "213") (name "Net-(LOCK3-PadP$5)") (class "Default")
      (node (ref "LOCK3") (pin "P$5") (pinfunction "P$5_P$5") (pintype "bidirectional"))
      (node (ref "R119") (pin "2") (pinfunction "2_2") (pintype "passive"))
    )
    (net (code "214") (name "Net-(LOCK3-PadP$7)") (class "Default")
      (node (ref "LOCK3") (pin "P$7") (pinfunction "P$7_P$7") (pintype "bidirectional"))
      (node (ref "R118") (pin "2") (pinfunction "2_2") (pintype "passive"))
    )
    (net (code "215") (name "Net-(LOCK4-PadP$5)") (class "Default")
      (node (ref "LOCK4") (pin "P$5") (pinfunction "P$5_P$5") (pintype "bidirectional"))
      (node (ref "R121") (pin "2") (pinfunction "2_2") (pintype "passive"))
    )
    (net (code "216") (name "Net-(LOCK4-PadP$7)") (class "Default")
      (node (ref "LOCK4") (pin "P$7") (pinfunction "P$7_P$7") (pintype "bidirectional"))
      (node (ref "R120") (pin "2") (pinfunction "2_2") (pintype "passive"))
    )
    (net (code "217") (name "Net-(LOCK5-PadP$5)") (class "Default")
      (node (ref "LOCK5") (pin "P$5") (pinfunction "P$5_P$5") (pintype "bidirectional"))
      (node (ref "R123") (pin "2") (pinfunction "2_2") (pintype "passive"))
    )
    (net (code "218") (name "Net-(LOCK5-PadP$7)") (class "Default")
      (node (ref "LOCK5") (pin "P$7") (pinfunction "P$7_P$7") (pintype "bidirectional"))
      (node (ref "R122") (pin "2") (pinfunction "2_2") (pintype "passive"))
    )
    (net (code "219") (name "Net-(LOCK6-PadP$5)") (class "Default")
      (node (ref "LOCK6") (pin "P$5") (pinfunction "P$5_P$5") (pintype "bidirectional"))
      (node (ref "R47") (pin "2") (pinfunction "2_2") (pintype "passive"))
    )
    (net (code "220") (name "Net-(LOCK6-PadP$7)") (class "Default")
      (node (ref "LOCK6") (pin "P$7") (pinfunction "P$7_P$7") (pintype "bidirectional"))
      (node (ref "R45") (pin "2") (pinfunction "2_2") (pintype "passive"))
    )
    (net (code "221") (name "Net-(LOCK_135-TIP)") (class "Default")
      (node (ref "LOCK_135") (pin "1") (pinfunction "TIP_1") (pintype "passive"))
      (node (ref "R168") (pin "1") (pinfunction "1_1") (pintype "passive"))
    )
    (net (code "222") (name "Net-(LOCK_246-TIP)") (class "Default")
      (node (ref "LOCK_246") (pin "1") (pinfunction "TIP_1") (pintype "passive"))
      (node (ref "R169") (pin "1") (pinfunction "1_1") (pintype "passive"))
    )
    (net (code "223") (name "Net-(MORPH-Pad2)") (class "Default")
      (node (ref "MORPH") (pin "2") (pinfunction "2_2") (pintype "passive"))
      (node (ref "R20") (pin "1") (pinfunction "1_1") (pintype "passive"))
    )
    (net (code "224") (name "Net-(MORPHCV-TIP)") (class "Default")
      (node (ref "MORPHCV") (pin "1") (pinfunction "TIP_1") (pintype "passive"))
      (node (ref "R74") (pin "1") (pinfunction "1_1") (pintype "passive"))
    )
    (net (code "225") (name "Net-(OUT-1-TIP)") (class "Default")
      (node (ref "OUT-1") (pin "1") (pinfunction "TIP_1") (pintype "passive"))
      (node (ref "OUT-2") (pin "3") (pinfunction "TIP-SW_3") (pintype "passive"))
      (node (ref "R3") (pin "1") (pinfunction "1_1") (pintype "passive"))
    )
    (net (code "226") (name "Net-(OUT-2-TIP)") (class "Default")
      (node (ref "OUT-2") (pin "1") (pinfunction "TIP_1") (pintype "passive"))
      (node (ref "R4") (pin "1") (pinfunction "1_1") (pintype "passive"))
    )
    (net (code "227") (name "Net-(PG2-1)") (class "Default")
      (node (ref "PG2") (pin "P$1") (pinfunction "1_P$1") (pintype "bidirectional"))
      (node (ref "U7") (pin "87") (pinfunction "PG2_87") (pintype "bidirectional"))
    )
    (net (code "228") (name "Net-(PG3-1)") (class "Default")
      (node (ref "PG3") (pin "P$1") (pinfunction "1_P$1") (pintype "bidirectional"))
      (node (ref "U7") (pin "88") (pinfunction "PG3_88") (pintype "bidirectional"))
    )
    (net (code "229") (name "Net-(PG5-1)") (class "Default")
      (node (ref "PG5") (pin "P$1") (pinfunction "1_P$1") (pintype "bidirectional"))
      (node (ref "U7") (pin "90") (pinfunction "PG5_90") (pintype "bidirectional"))
    )
    (net (code "230") (name "Net-(PG6-1)") (class "Default")
      (node (ref "PG6") (pin "P$1") (pinfunction "1_P$1") (pintype "bidirectional"))
      (node (ref "U7") (pin "91") (pinfunction "PG6_91") (pintype "bidirectional"))
    )
    (net (code "231") (name "Net-(POWER-P$1)") (class "Default")
      (node (ref "POWER") (pin "1") (pinfunction "P$1_1") (pintype "bidirectional"))
      (node (ref "POWER") (pin "2") (pinfunction "P$2_2") (pintype "bidirectional"))
    )
    (net (code "232") (name "Net-(POWER-P$5)") (class "Default")
      (node (ref "L2") (pin "1") (pinfunction "1_1") (pintype "passive"))
      (node (ref "POWER") (pin "5") (pinfunction "P$5_5") (pintype "bidirectional"))
      (node (ref "POWER") (pin "6") (pinfunction "P$6_6") (pintype "bidirectional"))
    )
    (net (code "233") (name "Net-(POWER-P$7)") (class "Default")
      (node (ref "D19") (pin "A") (pinfunction "A_A") (pintype "passive"))
      (node (ref "POWER") (pin "7") (pinfunction "P$7_7") (pintype "bidirectional"))
      (node (ref "POWER") (pin "8") (pinfunction "P$8_8") (pintype "bidirectional"))
    )
    (net (code "234") (name "Net-(QVAL-Pad2)") (class "Default")
      (node (ref "QVAL") (pin "2") (pinfunction "2_2") (pintype "passive"))
      (node (ref "R6") (pin "1") (pinfunction "1_1") (pintype "passive"))
    )
    (net (code "235") (name "Net-(QVALCV-TIP)") (class "Default")
      (node (ref "QVALCV") (pin "1") (pinfunction "TIP_1") (pintype "passive"))
      (node (ref "R76") (pin "1") (pinfunction "1_1") (pintype "passive"))
    )
    (net (code "236") (name "Net-(R5-Pad1)") (class "Default")
      (node (ref "R5") (pin "1") (pinfunction "1_1") (pintype "passive"))
      (node (ref "SPREAD") (pin "2") (pinfunction "2_2") (pintype "passive"))
    )
    (net (code "237") (name "Net-(R27-Pad2)") (class "Default")
      (node (ref "R27") (pin "2") (pinfunction "2_2") (pintype "passive"))
      (node (ref "U$1") (pin "D-") (pinfunction "D-_D-") (pintype "bidirectional"))
    )
    (net (code "238") (name "Net-(R28-Pad2)") (class "Default")
      (node (ref "R28") (pin "2") (pinfunction "2_2") (pintype "passive"))
      (node (ref "U$1") (pin "D+") (pinfunction "D+_D+") (pintype "bidirectional"))
    )
    (net (code "239") (name "Net-(ROTCV-TIP)") (class "Default")
      (node (ref "R124") (pin "1") (pinfunction "1_1") (pintype "passive"))
      (node (ref "ROTCV") (pin "1") (pinfunction "TIP_1") (pintype "passive"))
    )
    (net (code "240") (name "Net-(ROTRIGUP-TIP)") (class "Default")
      (node (ref "R18") (pin "1") (pinfunction "1_1") (pintype "passive"))
      (node (ref "ROTRIGUP") (pin "1") (pinfunction "TIP_1") (pintype "passive"))
    )
    (net (code "241") (name "Net-(ROTTRIGDOWN-TIP)") (class "Default")
      (node (ref "R17") (pin "1") (pinfunction "1_1") (pintype "passive"))
      (node (ref "ROTTRIGDOWN") (pin "1") (pinfunction "TIP_1") (pintype "passive"))
    )
    (net (code "242") (name "Net-(SCALECV-TIP)") (class "Default")
      (node (ref "R19") (pin "1") (pinfunction "1_1") (pintype "passive"))
      (node (ref "SCALECV") (pin "1") (pinfunction "TIP_1") (pintype "passive"))
    )
    (net (code "243") (name "Net-(SLIDE1A-C)") (class "Default")
      (node (ref "R49") (pin "1") (pinfunction "1_1") (pintype "passive"))
      (node (ref "SLIDE1") (pin "P$LEDC") (pinfunction "C_P$LEDC") (pintype "passive"))
    )
    (net (code "244") (name "Net-(SLIDE2A-C)") (class "Default")
      (node (ref "R48") (pin "1") (pinfunction "1_1") (pintype "passive"))
      (node (ref "SLIDE2") (pin "P$LEDC") (pinfunction "C_P$LEDC") (pintype "passive"))
    )
    (net (code "245") (name "Net-(SLIDE3A-C)") (class "Default")
      (node (ref "R24") (pin "1") (pinfunction "1_1") (pintype "passive"))
      (node (ref "SLIDE3") (pin "P$LEDC") (pinfunction "C_P$LEDC") (pintype "passive"))
    )
    (net (code "246") (name "Net-(SLIDE4A-C)") (class "Default")
      (node (ref "R21") (pin "1") (pinfunction "1_1") (pintype "passive"))
      (node (ref "SLIDE4") (pin "P$LEDC") (pinfunction "C_P$LEDC") (pintype "passive"))
    )
    (net (code "247") (name "Net-(SLIDE5A-C)") (class "Default")
      (node (ref "R22") (pin "1") (pinfunction "1_1") (pintype "passive"))
      (node (ref "SLIDE5") (pin "P$LEDC") (pinfunction "C_P$LEDC") (pintype "passive"))
    )
    (net (code "248") (name "Net-(SLIDE6A-C)") (class "Default")
      (node (ref "R23") (pin "1") (pinfunction "1_1") (pintype "passive"))
      (node (ref "SLIDE6") (pin "P$LEDC") (pinfunction "C_P$LEDC") (pintype "passive"))
    )
    (net (code "249") (name "Net-(SPREADCV-TIP)") (class "Default")
      (node (ref "R75") (pin "1") (pinfunction "1_1") (pintype "passive"))
      (node (ref "SPREADCV") (pin "1") (pinfunction "TIP_1") (pintype "passive"))
    )
    (net (code "250") (name "Net-(U1-VMID)") (class "Default")
      (node (ref "C20") (pin "1") (pinfunction "1_1") (pintype "passive"))
      (node (ref "C21") (pin "+") (pinfunction "+_+") (pintype "passive"))
      (node (ref "U1") (pin "P$16") (pinfunction "VMID_P$16") (pintype "output"))
    )
    (net (code "251") (name "Net-(U2-PWM0)") (class "Default")
      (node (ref "R12") (pin "1") (pinfunction "1_1") (pintype "passive"))
      (node (ref "U2") (pin "6") (pinfunction "PWM0_6") (pintype "output"))
    )
    (net (code "252") (name "Net-(U2-PWM1)") (class "Default")
      (node (ref "R13") (pin "1") (pinfunction "1_1") (pintype "passive"))
      (node (ref "U2") (pin "7") (pinfunction "PWM1_7") (pintype "output"))
    )
    (net (code "253") (name "Net-(U2-PWM2)") (class "Default")
      (node (ref "R14") (pin "1") (pinfunction "1_1") (pintype "passive"))
      (node (ref "U2") (pin "8") (pinfunction "PWM2_8") (pintype "output"))
    )
    (net (code "254") (name "Net-(U2-PWM3)") (class "Default")
      (node (ref "R15") (pin "1") (pinfunction "1_1") (pintype "passive"))
      (node (ref "U2") (pin "9") (pinfunction "PWM3_9") (pintype "output"))
    )
    (net (code "255") (name "Net-(U2-PWM4)") (class "Default")
      (node (ref "R29") (pin "1") (pinfunction "1_1") (pintype "passive"))
      (node (ref "U2") (pin "10") (pinfunction "PWM4_10") (pintype "output"))
    )
    (net (code "256") (name "Net-(U2-PWM5)") (class "Default")
      (node (ref "R30") (pin "1") (pinfunction "1_1") (pintype "passive"))
      (node (ref "U2") (pin "11") (pinfunction "PWM5_11") (pintype "output"))
    )
    (net (code "257") (name "Net-(U2-PWM6)") (class "Default")
      (node (ref "R79") (pin "1") (pinfunction "1_1") (pintype "passive"))
      (node (ref "U2") (pin "12") (pinfunction "PWM6_12") (pintype "output"))
    )
    (net (code "258") (name "Net-(U2-PWM7)") (class "Default")
      (node (ref "R173") (pin "1") (pinfunction "1_1") (pintype "passive"))
      (node (ref "U2") (pin "13") (pinfunction "PWM7_13") (pintype "output"))
    )
    (net (code "259") (name "Net-(U2-PWM8)") (class "Default")
      (node (ref "R174") (pin "1") (pinfunction "1_1") (pintype "passive"))
      (node (ref "U2") (pin "15") (pinfunction "PWM8_15") (pintype "output"))
    )
    (net (code "260") (name "Net-(U2-PWM9)") (class "Default")
      (node (ref "R175") (pin "1") (pinfunction "1_1") (pintype "passive"))
      (node (ref "U2") (pin "16") (pinfunction "PWM9_16") (pintype "output"))
    )
    (net (code "261") (name "Net-(U2-PWM10)") (class "Default")
      (node (ref "R176") (pin "1") (pinfunction "1_1") (pintype "passive"))
      (node (ref "U2") (pin "17") (pinfunction "PWM10_17") (pintype "output"))
    )
    (net (code "262") (name "Net-(U2-PWM11)") (class "Default")
      (node (ref "R177") (pin "1") (pinfunction "1_1") (pintype "passive"))
      (node (ref "U2") (pin "18") (pinfunction "PWM11_18") (pintype "output"))
    )
    (net (code "263") (name "Net-(U2-PWM12)") (class "Default")
      (node (ref "R178") (pin "1") (pinfunction "1_1") (pintype "passive"))
      (node (ref "U2") (pin "19") (pinfunction "PWM12_19") (pintype "output"))
    )
    (net (code "264") (name "Net-(U2-PWM13)") (class "Default")
      (node (ref "R179") (pin "1") (pinfunction "1_1") (pintype "passive"))
      (node (ref "U2") (pin "20") (pinfunction "PWM13_20") (pintype "output"))
    )
    (net (code "265") (name "Net-(U2-PWM14)") (class "Default")
      (node (ref "R180") (pin "1") (pinfunction "1_1") (pintype "passive"))
      (node (ref "U2") (pin "21") (pinfunction "PWM14_21") (pintype "output"))
    )
    (net (code "266") (name "Net-(U2-PWM15)") (class "Default")
      (node (ref "R181") (pin "1") (pinfunction "1_1") (pintype "passive"))
      (node (ref "U2") (pin "22") (pinfunction "PWM15_22") (pintype "output"))
    )
    (net (code "267") (name "Net-(U3-PWM0)") (class "Default")
      (node (ref "R153") (pin "1") (pinfunction "1_1") (pintype "passive"))
      (node (ref "U3") (pin "6") (pinfunction "PWM0_6") (pintype "output"))
    )
    (net (code "268") (name "Net-(U3-PWM1)") (class "Default")
      (node (ref "R166") (pin "1") (pinfunction "1_1") (pintype "passive"))
      (node (ref "U3") (pin "7") (pinfunction "PWM1_7") (pintype "output"))
    )
    (net (code "269") (name "Net-(U3-PWM2)") (class "Default")
      (node (ref "R167") (pin "1") (pinfunction "1_1") (pintype "passive"))
      (node (ref "U3") (pin "8") (pinfunction "PWM2_8") (pintype "output"))
    )
    (net (code "270") (name "Net-(U3-PWM3)") (class "Default")
      (node (ref "R163") (pin "1") (pinfunction "1_1") (pintype "passive"))
      (node (ref "U3") (pin "9") (pinfunction "PWM3_9") (pintype "output"))
    )
    (net (code "271") (name "Net-(U3-PWM4)") (class "Default")
      (node (ref "R164") (pin "1") (pinfunction "1_1") (pintype "passive"))
      (node (ref "U3") (pin "10") (pinfunction "PWM4_10") (pintype "output"))
    )
    (net (code "272") (name "Net-(U3-PWM5)") (class "Default")
      (node (ref "R165") (pin "1") (pinfunction "1_1") (pintype "passive"))
      (node (ref "U3") (pin "11") (pinfunction "PWM5_11") (pintype "output"))
    )
    (net (code "273") (name "Net-(U3-PWM6)") (class "Default")
      (node (ref "R154") (pin "1") (pinfunction "1_1") (pintype "passive"))
      (node (ref "U3") (pin "12") (pinfunction "PWM6_12") (pintype "output"))
    )
    (net (code "274") (name "Net-(U3-PWM7)") (class "Default")
      (node (ref "R155") (pin "1") (pinfunction "1_1") (pintype "passive"))
      (node (ref "U3") (pin "13") (pinfunction "PWM7_13") (pintype "output"))
    )
    (net (code "275") (name "Net-(U3-PWM8)") (class "Default")
      (node (ref "R156") (pin "1") (pinfunction "1_1") (pintype "passive"))
      (node (ref "U3") (pin "15") (pinfunction "PWM8_15") (pintype "output"))
    )
    (net (code "276") (name "Net-(U3-PWM9)") (class "Default")
      (node (ref "R157") (pin "1") (pinfunction "1_1") (pintype "passive"))
      (node (ref "U3") (pin "16") (pinfunction "PWM9_16") (pintype "output"))
    )
    (net (code "277") (name "Net-(U3-PWM10)") (class "Default")
      (node (ref "R158") (pin "1") (pinfunction "1_1") (pintype "passive"))
      (node (ref "U3") (pin "17") (pinfunction "PWM10_17") (pintype "output"))
    )
    (net (code "278") (name "Net-(U3-PWM11)") (class "Default")
      (node (ref "R159") (pin "1") (pinfunction "1_1") (pintype "passive"))
      (node (ref "U3") (pin "18") (pinfunction "PWM11_18") (pintype "output"))
    )
    (net (code "279") (name "Net-(U3-PWM12)") (class "Default")
      (node (ref "R160") (pin "1") (pinfunction "1_1") (pintype "passive"))
      (node (ref "U3") (pin "19") (pinfunction "PWM12_19") (pintype "output"))
    )
    (net (code "280") (name "Net-(U3-PWM13)") (class "Default")
      (node (ref "R161") (pin "1") (pinfunction "1_1") (pintype "passive"))
      (node (ref "U3") (pin "20") (pinfunction "PWM13_20") (pintype "output"))
    )
    (net (code "281") (name "Net-(U3-PWM14)") (class "Default")
      (node (ref "R162") (pin "1") (pinfunction "1_1") (pintype "passive"))
      (node (ref "U3") (pin "21") (pinfunction "PWM14_21") (pintype "output"))
    )
    (net (code "282") (name "Net-(U4-PWM0)") (class "Default")
      (node (ref "R10") (pin "1") (pinfunction "1_1") (pintype "passive"))
      (node (ref "U4") (pin "6") (pinfunction "PWM0_6") (pintype "output"))
    )
    (net (code "283") (name "Net-(U4-PWM1)") (class "Default")
      (node (ref "R11") (pin "1") (pinfunction "1_1") (pintype "passive"))
      (node (ref "U4") (pin "7") (pinfunction "PWM1_7") (pintype "output"))
    )
    (net (code "284") (name "Net-(U4-PWM2)") (class "Default")
      (node (ref "R131") (pin "1") (pinfunction "1_1") (pintype "passive"))
      (node (ref "U4") (pin "8") (pinfunction "PWM2_8") (pintype "output"))
    )
    (net (code "285") (name "Net-(U4-PWM3)") (class "Default")
      (node (ref "R112") (pin "1") (pinfunction "1_1") (pintype "passive"))
      (node (ref "U4") (pin "9") (pinfunction "PWM3_9") (pintype "output"))
    )
    (net (code "286") (name "Net-(U4-PWM4)") (class "Default")
      (node (ref "R113") (pin "1") (pinfunction "1_1") (pintype "passive"))
      (node (ref "U4") (pin "10") (pinfunction "PWM4_10") (pintype "output"))
    )
    (net (code "287") (name "Net-(U4-PWM5)") (class "Default")
      (node (ref "R114") (pin "1") (pinfunction "1_1") (pintype "passive"))
      (node (ref "U4") (pin "11") (pinfunction "PWM5_11") (pintype "output"))
    )
    (net (code "288") (name "Net-(U4-PWM6)") (class "Default")
      (node (ref "R94") (pin "1") (pinfunction "1_1") (pintype "passive"))
      (node (ref "U4") (pin "12") (pinfunction "PWM6_12") (pintype "output"))
    )
    (net (code "289") (name "Net-(U4-PWM7)") (class "Default")
      (node (ref "R95") (pin "1") (pinfunction "1_1") (pintype "passive"))
      (node (ref "U4") (pin "13") (pinfunction "PWM7_13") (pintype "output"))
    )
    (net (code "290") (name "Net-(U4-PWM8)") (class "Default")
      (node (ref "R96") (pin "1") (pinfunction "1_1") (pintype "passive"))
      (node (ref "U4") (pin "15") (pinfunction "PWM8_15") (pintype "output"))
    )
    (net (code "291") (name "Net-(U4-PWM9)") (class "Default")
      (node (ref "R97") (pin "1") (pinfunction "1_1") (pintype "passive"))
      (node (ref "U4") (pin "16") (pinfunction "PWM9_16") (pintype "output"))
    )
    (net (code "292") (name "Net-(U4-PWM10)") (class "Default")
      (node (ref "R98") (pin "1") (pinfunction "1_1") (pintype "passive"))
      (node (ref "U4") (pin "17") (pinfunction "PWM10_17") (pintype "output"))
    )
    (net (code "293") (name "Net-(U4-PWM11)") (class "Default")
      (node (ref "R99") (pin "1") (pinfunction "1_1") (pintype "passive"))
      (node (ref "U4") (pin "18") (pinfunction "PWM11_18") (pintype "output"))
    )
    (net (code "294") (name "Net-(U4-PWM12)") (class "Default")
      (node (ref "R100") (pin "1") (pinfunction "1_1") (pintype "passive"))
      (node (ref "U4") (pin "19") (pinfunction "PWM12_19") (pintype "output"))
    )
    (net (code "295") (name "Net-(U4-PWM13)") (class "Default")
      (node (ref "R101") (pin "1") (pinfunction "1_1") (pintype "passive"))
      (node (ref "U4") (pin "20") (pinfunction "PWM13_20") (pintype "output"))
    )
    (net (code "296") (name "Net-(U4-PWM14)") (class "Default")
      (node (ref "R102") (pin "1") (pinfunction "1_1") (pintype "passive"))
      (node (ref "U4") (pin "21") (pinfunction "PWM14_21") (pintype "output"))
    )
    (net (code "297") (name "Net-(U5-PWM0)") (class "Default")
      (node (ref "R103") (pin "1") (pinfunction "1_1") (pintype "passive"))
      (node (ref "U5") (pin "6") (pinfunction "PWM0_6") (pintype "output"))
    )
    (net (code "298") (name "Net-(U5-PWM1)") (class "Default")
      (node (ref "R104") (pin "1") (pinfunction "1_1") (pintype "passive"))
      (node (ref "U5") (pin "7") (pinfunction "PWM1_7") (pintype "output"))
    )
    (net (code "299") (name "Net-(U5-PWM2)") (class "Default")
      (node (ref "R105") (pin "1") (pinfunction "1_1") (pintype "passive"))
      (node (ref "U5") (pin "8") (pinfunction "PWM2_8") (pintype "output"))
    )
    (net (code "300") (name "Net-(U5-PWM3)") (class "Default")
      (node (ref "R106") (pin "1") (pinfunction "1_1") (pintype "passive"))
      (node (ref "U5") (pin "9") (pinfunction "PWM3_9") (pintype "output"))
    )
    (net (code "301") (name "Net-(U5-PWM4)") (class "Default")
      (node (ref "R107") (pin "1") (pinfunction "1_1") (pintype "passive"))
      (node (ref "U5") (pin "10") (pinfunction "PWM4_10") (pintype "output"))
    )
    (net (code "302") (name "Net-(U5-PWM5)") (class "Default")
      (node (ref "R108") (pin "1") (pinfunction "1_1") (pintype "passive"))
      (node (ref "U5") (pin "11") (pinfunction "PWM5_11") (pintype "output"))
    )
    (net (code "303") (name "Net-(U5-PWM6)") (class "Default")
      (node (ref "R109") (pin "1") (pinfunction "1_1") (pintype "passive"))
      (node (ref "U5") (pin "12") (pinfunction "PWM6_12") (pintype "output"))
    )
    (net (code "304") (name "Net-(U5-PWM7)") (class "Default")
      (node (ref "R110") (pin "1") (pinfunction "1_1") (pintype "passive"))
      (node (ref "U5") (pin "13") (pinfunction "PWM7_13") (pintype "output"))
    )
    (net (code "305") (name "Net-(U5-PWM8)") (class "Default")
      (node (ref "R111") (pin "1") (pinfunction "1_1") (pintype "passive"))
      (node (ref "U5") (pin "15") (pinfunction "PWM8_15") (pintype "output"))
    )
    (net (code "306") (name "Net-(U5-PWM9)") (class "Default")
      (node (ref "R132") (pin "1") (pinfunction "1_1") (pintype "passive"))
      (node (ref "U5") (pin "16") (pinfunction "PWM9_16") (pintype "output"))
    )
    (net (code "307") (name "Net-(U5-PWM10)") (class "Default")
      (node (ref "R133") (pin "1") (pinfunction "1_1") (pintype "passive"))
      (node (ref "U5") (pin "17") (pinfunction "PWM10_17") (pintype "output"))
    )
    (net (code "308") (name "Net-(U5-PWM11)") (class "Default")
      (node (ref "R134") (pin "1") (pinfunction "1_1") (pintype "passive"))
      (node (ref "U5") (pin "18") (pinfunction "PWM11_18") (pintype "output"))
    )
    (net (code "309") (name "Net-(U5-PWM12)") (class "Default")
      (node (ref "R135") (pin "1") (pinfunction "1_1") (pintype "passive"))
      (node (ref "U5") (pin "19") (pinfunction "PWM12_19") (pintype "output"))
    )
    (net (code "310") (name "Net-(U5-PWM13)") (class "Default")
      (node (ref "R136") (pin "1") (pinfunction "1_1") (pintype "passive"))
      (node (ref "U5") (pin "20") (pinfunction "PWM13_20") (pintype "output"))
    )
    (net (code "311") (name "Net-(U5-PWM14)") (class "Default")
      (node (ref "R137") (pin "1") (pinfunction "1_1") (pintype "passive"))
      (node (ref "U5") (pin "21") (pinfunction "PWM14_21") (pintype "output"))
    )
    (net (code "312") (name "Net-(U5-PWM15)") (class "Default")
      (node (ref "R184") (pin "1") (pinfunction "1_1") (pintype "passive"))
      (node (ref "U5") (pin "22") (pinfunction "PWM15_22") (pintype "output"))
    )
    (net (code "313") (name "Net-(U6-PWM0)") (class "Default")
      (node (ref "R138") (pin "1") (pinfunction "1_1") (pintype "passive"))
      (node (ref "U6") (pin "6") (pinfunction "PWM0_6") (pintype "output"))
    )
    (net (code "314") (name "Net-(U6-PWM1)") (class "Default")
      (node (ref "R139") (pin "1") (pinfunction "1_1") (pintype "passive"))
      (node (ref "U6") (pin "7") (pinfunction "PWM1_7") (pintype "output"))
    )
    (net (code "315") (name "Net-(U6-PWM2)") (class "Default")
      (node (ref "R140") (pin "1") (pinfunction "1_1") (pintype "passive"))
      (node (ref "U6") (pin "8") (pinfunction "PWM2_8") (pintype "output"))
    )
    (net (code "316") (name "Net-(U6-PWM3)") (class "Default")
      (node (ref "R141") (pin "1") (pinfunction "1_1") (pintype "passive"))
      (node (ref "U6") (pin "9") (pinfunction "PWM3_9") (pintype "output"))
    )
    (net (code "317") (name "Net-(U6-PWM4)") (class "Default")
      (node (ref "R142") (pin "1") (pinfunction "1_1") (pintype "passive"))
      (node (ref "U6") (pin "10") (pinfunction "PWM4_10") (pintype "output"))
    )
    (net (code "318") (name "Net-(U6-PWM5)") (class "Default")
      (node (ref "R143") (pin "1") (pinfunction "1_1") (pintype "passive"))
      (node (ref "U6") (pin "11") (pinfunction "PWM5_11") (pintype "output"))
    )
    (net (code "319") (name "Net-(U6-PWM6)") (class "Default")
      (node (ref "R144") (pin "1") (pinfunction "1_1") (pintype "passive"))
      (node (ref "U6") (pin "12") (pinfunction "PWM6_12") (pintype "output"))
    )
    (net (code "320") (name "Net-(U6-PWM7)") (class "Default")
      (node (ref "R145") (pin "1") (pinfunction "1_1") (pintype "passive"))
      (node (ref "U6") (pin "13") (pinfunction "PWM7_13") (pintype "output"))
    )
    (net (code "321") (name "Net-(U6-PWM8)") (class "Default")
      (node (ref "R146") (pin "1") (pinfunction "1_1") (pintype "passive"))
      (node (ref "U6") (pin "15") (pinfunction "PWM8_15") (pintype "output"))
    )
    (net (code "322") (name "Net-(U6-PWM9)") (class "Default")
      (node (ref "R147") (pin "1") (pinfunction "1_1") (pintype "passive"))
      (node (ref "U6") (pin "16") (pinfunction "PWM9_16") (pintype "output"))
    )
    (net (code "323") (name "Net-(U6-PWM10)") (class "Default")
      (node (ref "R148") (pin "1") (pinfunction "1_1") (pintype "passive"))
      (node (ref "U6") (pin "17") (pinfunction "PWM10_17") (pintype "output"))
    )
    (net (code "324") (name "Net-(U6-PWM11)") (class "Default")
      (node (ref "R149") (pin "1") (pinfunction "1_1") (pintype "passive"))
      (node (ref "U6") (pin "18") (pinfunction "PWM11_18") (pintype "output"))
    )
    (net (code "325") (name "Net-(U6-PWM12)") (class "Default")
      (node (ref "R150") (pin "1") (pinfunction "1_1") (pintype "passive"))
      (node (ref "U6") (pin "19") (pinfunction "PWM12_19") (pintype "output"))
    )
    (net (code "326") (name "Net-(U6-PWM13)") (class "Default")
      (node (ref "R151") (pin "1") (pinfunction "1_1") (pintype "passive"))
      (node (ref "U6") (pin "20") (pinfunction "PWM13_20") (pintype "output"))
    )
    (net (code "327") (name "Net-(U6-PWM14)") (class "Default")
      (node (ref "R152") (pin "1") (pinfunction "1_1") (pintype "passive"))
      (node (ref "U6") (pin "21") (pinfunction "PWM14_21") (pintype "output"))
    )
    (net (code "328") (name "Net-(U6-PWM15)") (class "Default")
      (node (ref "R182") (pin "1") (pinfunction "1_1") (pintype "passive"))
      (node (ref "U6") (pin "22") (pinfunction "PWM15_22") (pintype "output"))
    )
    (net (code "329") (name "Net-(U7-BOOT0)") (class "Default")
      (node (ref "R26") (pin "1") (pinfunction "1_1") (pintype "passive"))
      (node (ref "S1") (pin "1") (pinfunction "1_1") (pintype "passive"))
      (node (ref "S1") (pin "2") (pinfunction "2_2") (pintype "passive"))
      (node (ref "U7") (pin "138") (pinfunction "BOOT0_138") (pintype "bidirectional"))
    )
    (net (code "330") (name "Net-(U7-NRST)") (class "Default")
      (node (ref "C12") (pin "1") (pinfunction "1_1") (pintype "passive"))
      (node (ref "S0") (pin "3") (pinfunction "3_3") (pintype "passive"))
      (node (ref "S0") (pin "4") (pinfunction "4_4") (pintype "passive"))
      (node (ref "U7") (pin "25") (pinfunction "NRST_25") (pintype "bidirectional"))
    )
    (net (code "331") (name "Net-(U7-PH0-OSC_IN)") (class "Default")
      (node (ref "C32") (pin "2") (pinfunction "2_2") (pintype "passive"))
      (node (ref "U7") (pin "23") (pinfunction "PH0-OSC_IN_23") (pintype "bidirectional"))
      (node (ref "X1") (pin "1") (pinfunction "1_1") (pintype "passive"))
    )
    (net (code "332") (name "Net-(U7-PH1-OSC_OUT)") (class "Default")
      (node (ref "C33") (pin "2") (pinfunction "2_2") (pintype "passive"))
      (node (ref "U7") (pin "24") (pinfunction "PH1-OSC_OUT_24") (pintype "bidirectional"))
      (node (ref "X1") (pin "2") (pinfunction "2_2") (pintype "passive"))
    )
    (net (code "333") (name "Net-(U7-VCAP1)") (class "Default")
      (node (ref "C29") (pin "1") (pinfunction "1_1") (pintype "passive"))
      (node (ref "U7") (pin "71") (pinfunction "VCAP1_71") (pintype "bidirectional"))
    )
    (net (code "334") (name "Net-(U7-VCAP2)") (class "Default")
      (node (ref "C28") (pin "1") (pinfunction "1_1") (pintype "passive"))
      (node (ref "U7") (pin "106") (pinfunction "VCAP2_106") (pintype "bidirectional"))
    )
    (net (code "335") (name "OUT-L") (class "Default")
      (node (ref "R63") (pin "1") (pinfunction "1_1") (pintype "passive"))
      (node (ref "U1") (pin "P$12") (pinfunction "LOUT_P$12") (pintype "output"))
    )
    (net (code "336") (name "OUT-R") (class "Default")
      (node (ref "R64") (pin "1") (pinfunction "1_1") (pintype "passive"))
      (node (ref "U1") (pin "P$13") (pinfunction "ROUT_P$13") (pintype "output"))
    )
    (net (code "337") (name "PREPOST") (class "Default")
      (node (ref "PREPOST-SW") (pin "P$2") (pinfunction "P$2_P$2") (pintype "passive"))
      (node (ref "U7") (pin "77") (pinfunction "PD8/USART3_TX(5T)_77") (pintype "bidirectional"))
    )
    (net (code "338") (name "QCVADC") (class "Default")
      (node (ref "C49") (pin "1") (pinfunction "1_1") (pintype "passive"))
      (node (ref "D12") (pin "3") (pinfunction "COMMON_3") (pintype "bidirectional"))
      (node (ref "R172") (pin "1") (pinfunction "1_1") (pintype "passive"))
      (node (ref "R76") (pin "2") (pinfunction "2_2") (pintype "passive"))
      (node (ref "U7") (pin "35") (pinfunction "PA1/ETH_RMII_RX_CLK/ADC123_IN1_35") (pintype "bidirectional"))
    )
    (net (code "339") (name "QPOTADC") (class "Default")
      (node (ref "C19") (pin "1") (pinfunction "1_1") (pintype "passive"))
      (node (ref "R6") (pin "2") (pinfunction "2_2") (pintype "passive"))
      (node (ref "U7") (pin "18") (pinfunction "PF6/ADC3_IN4_18") (pintype "bidirectional"))
    )
    (net (code "340") (name "ROTADC") (class "Default")
      (node (ref "D14") (pin "3") (pinfunction "COMMON_3") (pintype "bidirectional"))
      (node (ref "R124") (pin "2") (pinfunction "2_2") (pintype "passive"))
      (node (ref "R127") (pin "1") (pinfunction "1_1") (pintype "passive"))
      (node (ref "U7") (pin "41") (pinfunction "PA5/DAC2/SPI1_SCK/ADC12_IN5_41") (pintype "bidirectional"))
    )
    (net (code "341") (name "ROTENC1") (class "Default")
      (node (ref "C44") (pin "1") (pinfunction "1_1") (pintype "passive"))
      (node (ref "R59") (pin "2") (pinfunction "2_2") (pintype "passive"))
      (node (ref "U7") (pin "79") (pinfunction "PD10(5T)_79") (pintype "bidirectional"))
    )
    (net (code "342") (name "ROTENC2") (class "Default")
      (node (ref "C45") (pin "1") (pinfunction "1_1") (pintype "passive"))
      (node (ref "R60") (pin "1") (pinfunction "1_1") (pintype "passive"))
      (node (ref "U7") (pin "80") (pinfunction "PD11(5T)_80") (pintype "bidirectional"))
    )
    (net (code "343") (name "ROTENCSW") (class "Default")
      (node (ref "C9") (pin "1") (pinfunction "1_1") (pintype "passive"))
      (node (ref "R33") (pin "2") (pinfunction "2_2") (pintype "passive"))
      (node (ref "U7") (pin "78") (pinfunction "PD9/USART3_RX(5T)_78") (pintype "bidirectional"))
    )
    (net (code "344") (name "ROTTRIGL") (class "Default")
      (node (ref "D1") (pin "3") (pinfunction "COMMON_3") (pintype "bidirectional"))
      (node (ref "R17") (pin "2") (pinfunction "2_2") (pintype "passive"))
      (node (ref "U7") (pin "8") (pinfunction "PC14/OSC32_IN(5T)_8") (pintype "bidirectional"))
    )
    (net (code "345") (name "ROTTRIGR") (class "Default")
      (node (ref "D2") (pin "3") (pinfunction "COMMON_3") (pintype "bidirectional"))
      (node (ref "R18") (pin "2") (pinfunction "2_2") (pintype "passive"))
      (node (ref "U7") (pin "9") (pinfunction "PC15/OSC32_OUT(5T)_9") (pintype "bidirectional"))
    )
    (net (code "346") (name "SCALEADC") (class "Default")
      (node (ref "D3") (pin "3") (pinfunction "COMMON_3") (pintype "bidirectional"))
      (node (ref "R128") (pin "1") (pinfunction "1_1") (pintype "passive"))
      (node (ref "R19") (pin "2") (pinfunction "2_2") (pintype "passive"))
      (node (ref "U7") (pin "44") (pinfunction "PC4/ETH_MII_RXD0/ADC12_IN14_44") (pintype "bidirectional"))
    )
    (net (code "347") (name "SLDADC1") (class "Default")
      (node (ref "C65") (pin "1") (pinfunction "1_1") (pintype "passive"))
      (node (ref "SLIDE1") (pin "P$2") (pinfunction "2_P$2") (pintype "passive"))
      (node (ref "U7") (pin "13") (pinfunction "PF3/ADC3_IN9_13") (pintype "bidirectional"))
    )
    (net (code "348") (name "SLDADC2") (class "Default")
      (node (ref "C66") (pin "1") (pinfunction "1_1") (pintype "passive"))
      (node (ref "SLIDE2") (pin "P$2") (pinfunction "2_P$2") (pintype "passive"))
      (node (ref "U7") (pin "14") (pinfunction "PF4/ADC3_IN14_14") (pintype "bidirectional"))
    )
    (net (code "349") (name "SLDADC3") (class "Default")
      (node (ref "C67") (pin "1") (pinfunction "1_1") (pintype "passive"))
      (node (ref "SLIDE3") (pin "P$2") (pinfunction "2_P$2") (pintype "passive"))
      (node (ref "U7") (pin "15") (pinfunction "PF5/ADC3_IN15_15") (pintype "bidirectional"))
    )
    (net (code "350") (name "SLDADC4") (class "Default")
      (node (ref "C68") (pin "1") (pinfunction "1_1") (pintype "passive"))
      (node (ref "SLIDE4") (pin "P$2") (pinfunction "2_P$2") (pintype "passive"))
      (node (ref "U7") (pin "19") (pinfunction "PF7/ADC3_IN5_19") (pintype "bidirectional"))
    )
    (net (code "351") (name "SLDADC5") (class "Default")
      (node (ref "C69") (pin "1") (pinfunction "1_1") (pintype "passive"))
      (node (ref "SLIDE5") (pin "P$2") (pinfunction "2_P$2") (pintype "passive"))
      (node (ref "U7") (pin "20") (pinfunction "PF8/ADC3_IN6_20") (pintype "bidirectional"))
    )
    (net (code "352") (name "SLDADC6") (class "Default")
      (node (ref "C70") (pin "1") (pinfunction "1_1") (pintype "passive"))
      (node (ref "SLIDE6") (pin "P$2") (pinfunction "2_P$2") (pintype "passive"))
      (node (ref "U7") (pin "21") (pinfunction "PF9/ADC3_IN7_21") (pintype "bidirectional"))
    )
    (net (code "353") (name "SLLED1") (class "Default")
      (node (ref "SLIDE1") (pin "P$LEDA") (pinfunction "A_P$LEDA") (pintype "passive"))
      (node (ref "U7") (pin "124") (pinfunction "PG9_124") (pintype "bidirectional"))
    )
    (net (code "354") (name "SLLED2") (class "Default")
      (node (ref "SLIDE2") (pin "P$LEDA") (pinfunction "A_P$LEDA") (pintype "passive"))
      (node (ref "U7") (pin "125") (pinfunction "PG10_125") (pintype "bidirectional"))
    )
    (net (code "355") (name "SLLED3") (class "Default")
      (node (ref "SLIDE3") (pin "P$LEDA") (pinfunction "A_P$LEDA") (pintype "passive"))
      (node (ref "U7") (pin "126") (pinfunction "PG11_126") (pintype "bidirectional"))
    )
    (net (code "356") (name "SLLED4") (class "Default")
      (node (ref "SLIDE4") (pin "P$LEDA") (pinfunction "A_P$LEDA") (pintype "passive"))
      (node (ref "U7") (pin "127") (pinfunction "PG12_127") (pintype "bidirectional"))
    )
    (net (code "357") (name "SLLED5") (class "Default")
      (node (ref "SLIDE5") (pin "P$LEDA") (pinfunction "A_P$LEDA") (pintype "passive"))
      (node (ref "U7") (pin "128") (pinfunction "PG13_128") (pintype "bidirectional"))
    )
    (net (code "358") (name "SLLED6") (class "Default")
      (node (ref "SLIDE6") (pin "P$LEDA") (pinfunction "A_P$LEDA") (pintype "passive"))
      (node (ref "U7") (pin "129") (pinfunction "PG14_129") (pintype "bidirectional"))
    )
    (net (code "359") (name "SPREADADC") (class "Default")
      (node (ref "C48") (pin "1") (pinfunction "1_1") (pintype "passive"))
      (node (ref "D11") (pin "3") (pinfunction "COMMON_3") (pintype "bidirectional"))
      (node (ref "R5") (pin "2") (pinfunction "2_2") (pintype "passive"))
      (node (ref "R78") (pin "2") (pinfunction "2_2") (pintype "passive"))
      (node (ref "U7") (pin "45") (pinfunction "PC5/ETH_MII_RXD1/ADC12_IN15_45") (pintype "bidirectional"))
    )
    (net (code "360") (name "SWCK") (class "Default")
      (node (ref "SWD") (pin "P$2") (pinfunction "P$2_P$2") (pintype "bidirectional"))
      (node (ref "U7") (pin "109") (pinfunction "PA14/JTCK-SWCLK(5T)_109") (pintype "bidirectional"))
    )
    (net (code "361") (name "SWDIO") (class "Default")
      (node (ref "SWD") (pin "P$4") (pinfunction "P$4_P$4") (pintype "bidirectional"))
      (node (ref "U7") (pin "105") (pinfunction "PA13/JTMS-SWDAT(5T)_105") (pintype "bidirectional"))
    )
    (net (code "362") (name "USB_DM") (class "Default")
      (node (ref "R27") (pin "1") (pinfunction "1_1") (pintype "passive"))
      (node (ref "U7") (pin "103") (pinfunction "PA11/USART1_CTS(5T)_103") (pintype "bidirectional"))
    )
    (net (code "363") (name "USB_DP") (class "Default")
      (node (ref "R28") (pin "1") (pinfunction "1_1") (pintype "passive"))
      (node (ref "U7") (pin "104") (pinfunction "PA12/USART1_RTS(5T)_104") (pintype "bidirectional"))
    )
    (net (code "364") (name "USB_VBUS") (class "Default")
      (node (ref "U$1") (pin "VBUS") (pinfunction "VBUS_VBUS") (pintype "bidirectional"))
      (node (ref "U7") (pin "101") (pinfunction "PA9/USART1_TX(5T)_101") (pintype "bidirectional"))
    )
    (net (code "365") (name "unconnected-(BANKSCALE-SW-PadP$3)") (class "Default")
      (node (ref "BANKSCALE-SW") (pin "P$3") (pinfunction "P$3_P$3") (pintype "passive"))
    )
    (net (code "366") (name "unconnected-(ENV1-TIP-SW-Pad3)") (class "Default")
      (node (ref "ENV1") (pin "3") (pinfunction "TIP-SW_3") (pintype "passive"))
    )
    (net (code "367") (name "unconnected-(ENV2-TIP-SW-Pad3)") (class "Default")
      (node (ref "ENV2") (pin "3") (pinfunction "TIP-SW_3") (pintype "passive"))
    )
    (net (code "368") (name "unconnected-(ENV3-TIP-SW-Pad3)") (class "Default")
      (node (ref "ENV3") (pin "3") (pinfunction "TIP-SW_3") (pintype "passive"))
    )
    (net (code "369") (name "unconnected-(ENV4-TIP-SW-Pad3)") (class "Default")
      (node (ref "ENV4") (pin "3") (pinfunction "TIP-SW_3") (pintype "passive"))
    )
    (net (code "370") (name "unconnected-(ENV5-TIP-SW-Pad3)") (class "Default")
      (node (ref "ENV5") (pin "3") (pinfunction "TIP-SW_3") (pintype "passive"))
    )
    (net (code "371") (name "unconnected-(ENV6-TIP-SW-Pad3)") (class "Default")
      (node (ref "ENV6") (pin "3") (pinfunction "TIP-SW_3") (pintype "passive"))
    )
    (net (code "372") (name "unconnected-(LAG-SW-PadP$3)") (class "Default")
      (node (ref "LAG-SW") (pin "P$3") (pinfunction "P$3_P$3") (pintype "passive"))
    )
    (net (code "373") (name "unconnected-(LOCK1-PadP$1)") (class "Default")
      (node (ref "LOCK1") (pin "P$1") (pinfunction "P$1_P$1") (pintype "bidirectional"))
    )
    (net (code "374") (name "unconnected-(LOCK1-PadP$2)") (class "Default")
      (node (ref "LOCK1") (pin "P$2") (pinfunction "P$2_P$2") (pintype "bidirectional"))
    )
    (net (code "375") (name "unconnected-(LOCK1-PadP$3)") (class "Default")
      (node (ref "LOCK1") (pin "P$3") (pinfunction "P$3_P$3") (pintype "bidirectional"))
    )
    (net (code "376") (name "unconnected-(LOCK1-PadP$4)") (class "Default")
      (node (ref "LOCK1") (pin "P$4") (pinfunction "P$4_P$4") (pintype "bidirectional"))
    )
    (net (code "377") (name "unconnected-(LOCK2-PadP$1)") (class "Default")
      (node (ref "LOCK2") (pin "P$1") (pinfunction "P$1_P$1") (pintype "bidirectional"))
    )
    (net (code "378") (name "unconnected-(LOCK2-PadP$2)") (class "Default")
      (node (ref "LOCK2") (pin "P$2") (pinfunction "P$2_P$2") (pintype "bidirectional"))
    )
    (net (code "379") (name "unconnected-(LOCK2-PadP$3)") (class "Default")
      (node (ref "LOCK2") (pin "P$3") (pinfunction "P$3_P$3") (pintype "bidirectional"))
    )
    (net (code "380") (name "unconnected-(LOCK2-PadP$4)") (class "Default")
      (node (ref "LOCK2") (pin "P$4") (pinfunction "P$4_P$4") (pintype "bidirectional"))
    )
    (net (code "381") (name "unconnected-(LOCK3-PadP$1)") (class "Default")
      (node (ref "LOCK3") (pin "P$1") (pinfunction "P$1_P$1") (pintype "bidirectional"))
    )
    (net (code "382") (name "unconnected-(LOCK3-PadP$2)") (class "Default")
      (node (ref "LOCK3") (pin "P$2") (pinfunction "P$2_P$2") (pintype "bidirectional"))
    )
    (net (code "383") (name "unconnected-(LOCK3-PadP$3)") (class "Default")
      (node (ref "LOCK3") (pin "P$3") (pinfunction "P$3_P$3") (pintype "bidirectional"))
    )
    (net (code "384") (name "unconnected-(LOCK3-PadP$4)") (class "Default")
      (node (ref "LOCK3") (pin "P$4") (pinfunction "P$4_P$4") (pintype "bidirectional"))
    )
    (net (code "385") (name "unconnected-(LOCK4-PadP$1)") (class "Default")
      (node (ref "LOCK4") (pin "P$1") (pinfunction "P$1_P$1") (pintype "bidirectional"))
    )
    (net (code "386") (name "unconnected-(LOCK4-PadP$2)") (class "Default")
      (node (ref "LOCK4") (pin "P$2") (pinfunction "P$2_P$2") (pintype "bidirectional"))
    )
    (net (code "387") (name "unconnected-(LOCK4-PadP$3)") (class "Default")
      (node (ref "LOCK4") (pin "P$3") (pinfunction "P$3_P$3") (pintype "bidirectional"))
    )
    (net (code "388") (name "unconnected-(LOCK4-PadP$4)") (class "Default")
      (node (ref "LOCK4") (pin "P$4") (pinfunction "P$4_P$4") (pintype "bidirectional"))
    )
    (net (code "389") (name "unconnected-(LOCK5-PadP$1)") (class "Default")
      (node (ref "LOCK5") (pin "P$1") (pinfunction "P$1_P$1") (pintype "bidirectional"))
    )
    (net (code "390") (name "unconnected-(LOCK5-PadP$2)") (class "Default")
      (node (ref "LOCK5") (pin "P$2") (pinfunction "P$2_P$2") (pintype "bidirectional"))
    )
    (net (code "391") (name "unconnected-(LOCK5-PadP$3)") (class "Default")
      (node (ref "LOCK5") (pin "P$3") (pinfunction "P$3_P$3") (pintype "bidirectional"))
    )
    (net (code "392") (name "unconnected-(LOCK5-PadP$4)") (class "Default")
      (node (ref "LOCK5") (pin "P$4") (pinfunction "P$4_P$4") (pintype "bidirectional"))
    )
    (net (code "393") (name "unconnected-(LOCK6-PadP$1)") (class "Default")
      (node (ref "LOCK6") (pin "P$1") (pinfunction "P$1_P$1") (pintype "bidirectional"))
    )
    (net (code "394") (name "unconnected-(LOCK6-PadP$2)") (class "Default")
      (node (ref "LOCK6") (pin "P$2") (pinfunction "P$2_P$2") (pintype "bidirectional"))
    )
    (net (code "395") (name "unconnected-(LOCK6-PadP$3)") (class "Default")
      (node (ref "LOCK6") (pin "P$3") (pinfunction "P$3_P$3") (pintype "bidirectional"))
    )
    (net (code "396") (name "unconnected-(LOCK6-PadP$4)") (class "Default")
      (node (ref "LOCK6") (pin "P$4") (pinfunction "P$4_P$4") (pintype "bidirectional"))
    )
    (net (code "397") (name "unconnected-(MOD135-SW-PadP$3)") (class "Default")
      (node (ref "MOD135-SW") (pin "P$3") (pinfunction "P$3_P$3") (pintype "passive"))
    )
    (net (code "398") (name "unconnected-(MOD246-SW-PadP$3)") (class "Default")
      (node (ref "MOD246-SW") (pin "P$3") (pinfunction "P$3_P$3") (pintype "passive"))
    )
    (net (code "399") (name "unconnected-(OUT-1-TIP-SW-Pad3)") (class "Default")
      (node (ref "OUT-1") (pin "3") (pinfunction "TIP-SW_3") (pintype "passive"))
    )
    (net (code "400") (name "unconnected-(POWER-P$3-Pad3)") (class "Default")
      (node (ref "POWER") (pin "3") (pinfunction "P$3_3") (pintype "bidirectional"))
    )
    (net (code "401") (name "unconnected-(POWER-P$4-Pad4)") (class "Default")
      (node (ref "POWER") (pin "4") (pinfunction "P$4_4") (pintype "bidirectional"))
    )
    (net (code "402") (name "unconnected-(PREPOST-SW-PadP$3)") (class "Default")
      (node (ref "PREPOST-SW") (pin "P$3") (pinfunction "P$3_P$3") (pintype "passive"))
    )
    (net (code "403") (name "unconnected-(QVALCV-TIP-SW-Pad3)") (class "Default")
      (node (ref "QVALCV") (pin "3") (pinfunction "TIP-SW_3") (pintype "passive"))
    )
    (net (code "404") (name "unconnected-(U$1-PadID)") (class "Default")
      (node (ref "U$1") (pin "ID") (pinfunction "ID_ID") (pintype "bidirectional"))
    )
    (net (code "405") (name "unconnected-(U1-CLKOUT-PadP$2)") (class "Default")
      (node (ref "U1") (pin "P$2") (pinfunction "CLKOUT_P$2") (pintype "output"))
    )
    (net (code "406") (name "unconnected-(U1-LHPOUT-PadP$9)") (class "Default")
      (node (ref "U1") (pin "P$9") (pinfunction "LHPOUT_P$9") (pintype "output"))
    )
    (net (code "407") (name "unconnected-(U1-MICBIAS-PadP$17)") (class "Default")
      (node (ref "U1") (pin "P$17") (pinfunction "MICBIAS_P$17") (pintype "output"))
    )
    (net (code "408") (name "unconnected-(U1-RHPOUT-PadP$10)") (class "Default")
      (node (ref "U1") (pin "P$10") (pinfunction "RHPOUT_P$10") (pintype "output"))
    )
    (net (code "409") (name "unconnected-(U1-XTO-PadP$26)") (class "Default")
      (node (ref "U1") (pin "P$26") (pinfunction "XTO_P$26") (pintype "output"))
    )
    (net (code "410") (name "unconnected-(U3-PWM15-Pad22)") (class "Default")
      (node (ref "U3") (pin "22") (pinfunction "PWM15_22") (pintype "output"))
    )
    (net (code "411") (name "unconnected-(U4-PWM15-Pad22)") (class "Default")
      (node (ref "U4") (pin "22") (pinfunction "PWM15_22") (pintype "output"))
    )
    (net (code "412") (name "unconnected-(U7-PA15{slash}I2S3_WS{slash}JTDI-Pad110)") (class "Default")
      (node (ref "U7") (pin "110") (pinfunction "PA15/I2S3_WS/JTDI_110") (pintype "bidirectional"))
    )
    (net (code "413") (name "unconnected-(U7-PC10{slash}UART4_TX(5T)-Pad111)") (class "Default")
      (node (ref "U7") (pin "111") (pinfunction "PC10/UART4_TX(5T)_111") (pintype "bidirectional"))
    )
    (net (code "414") (name "unconnected-(U7-PC11{slash}UART4_RX(5T)-Pad112)") (class "Default")
      (node (ref "U7") (pin "112") (pinfunction "PC11/UART4_RX(5T)_112") (pintype "bidirectional"))
    )
    (net (code "415") (name "unconnected-(U7-PC12{slash}I2S3_SD{slash}UART5_TX-Pad113)") (class "Default")
      (node (ref "U7") (pin "113") (pinfunction "PC12/I2S3_SD/UART5_TX_113") (pintype "bidirectional"))
    )
    (net (code "416") (name "unconnected-(U7-PC13(5T)-Pad7)") (class "Default")
      (node (ref "U7") (pin "7") (pinfunction "PC13(5T)_7") (pintype "bidirectional"))
    )
    (net (code "417") (name "unconnected-(U7-PD4(5T)-Pad118)") (class "Default")
      (node (ref "U7") (pin "118") (pinfunction "PD4(5T)_118") (pintype "bidirectional"))
    )
    (net (code "418") (name "unconnected-(U7-PD5{slash}USART2_TX(5T)-Pad119)") (class "Default")
      (node (ref "U7") (pin "119") (pinfunction "PD5/USART2_TX(5T)_119") (pintype "bidirectional"))
    )
    (net (code "419") (name "unconnected-(U7-PD6{slash}USART2_RX(5T)-Pad122)") (class "Default")
      (node (ref "U7") (pin "122") (pinfunction "PD6/USART2_RX(5T)_122") (pintype "bidirectional"))
    )
    (net (code "420") (name "unconnected-(U7-PD7(5T)-Pad123)") (class "Default")
      (node (ref "U7") (pin "123") (pinfunction "PD7(5T)_123") (pintype "bidirectional"))
    )
    (net (code "421") (name "unconnected-(U7-PD13{slash}TIM4_CH2(5T)-Pad82)") (class "Default")
      (node (ref "U7") (pin "82") (pinfunction "PD13/TIM4_CH2(5T)_82") (pintype "bidirectional"))
    )
    (net (code "422") (name "unconnected-(U7-PE10{slash}TIM1_CH2N(5T)-Pad63)") (class "Default")
      (node (ref "U7") (pin "63") (pinfunction "PE10/TIM1_CH2N(5T)_63") (pintype "bidirectional"))
    )
    (net (code "423") (name "unconnected-(U7-PE11{slash}TIM1_CH2(5T)-Pad64)") (class "Default")
      (node (ref "U7") (pin "64") (pinfunction "PE11/TIM1_CH2(5T)_64") (pintype "bidirectional"))
    )
    (net (code "424") (name "unconnected-(U7-PE12{slash}TIM1_CH3N(5T)-Pad65)") (class "Default")
      (node (ref "U7") (pin "65") (pinfunction "PE12/TIM1_CH3N(5T)_65") (pintype "bidirectional"))
    )
    (net (code "425") (name "unconnected-(U7-PE13{slash}TIM1_CH3(5T)-Pad66)") (class "Default")
      (node (ref "U7") (pin "66") (pinfunction "PE13/TIM1_CH3(5T)_66") (pintype "bidirectional"))
    )
    (net (code "426") (name "unconnected-(U7-PE14{slash}TIM1_CH4(5T)-Pad67)") (class "Default")
      (node (ref "U7") (pin "67") (pinfunction "PE14/TIM1_CH4(5T)_67") (pintype "bidirectional"))
    )
    (net (code "427") (name "unconnected-(U7-PE15{slash}TIM1_BKIN(5T)-Pad68)") (class "Default")
      (node (ref "U7") (pin "68") (pinfunction "PE15/TIM1_BKIN(5T)_68") (pintype "bidirectional"))
    )
    (net (code "428") (name "unconnected-(U7-PF0-Pad10)") (class "Default")
      (node (ref "U7") (pin "10") (pinfunction "PF0_10") (pintype "bidirectional"))
    )
    (net (code "429") (name "unconnected-(U7-PF1-Pad11)") (class "Default")
      (node (ref "U7") (pin "11") (pinfunction "PF1_11") (pintype "bidirectional"))
    )
    (net (code "430") (name "unconnected-(U7-PF2-Pad12)") (class "Default")
      (node (ref "U7") (pin "12") (pinfunction "PF2_12") (pintype "bidirectional"))
    )
    (net (code "431") (name "unconnected-(U7-PF10{slash}ADC3_IN8-Pad22)") (class "Default")
      (node (ref "U7") (pin "22") (pinfunction "PF10/ADC3_IN8_22") (pintype "bidirectional"))
    )
    (net (code "432") (name "unconnected-(U7-PF11-Pad49)") (class "Default")
      (node (ref "U7") (pin "49") (pinfunction "PF11_49") (pintype "bidirectional"))
    )
    (net (code "433") (name "unconnected-(U7-PF12-Pad50)") (class "Default")
      (node (ref "U7") (pin "50") (pinfunction "PF12_50") (pintype "bidirectional"))
    )
    (net (code "434") (name "unconnected-(U7-PF13-Pad53)") (class "Default")
      (node (ref "U7") (pin "53") (pinfunction "PF13_53") (pintype "bidirectional"))
    )
    (net (code "435") (name "unconnected-(U7-PF14-Pad54)") (class "Default")
      (node (ref "U7") (pin "54") (pinfunction "PF14_54") (pintype "bidirectional"))
    )
    (net (code "436") (name "unconnected-(U7-PF15-Pad55)") (class "Default")
      (node (ref "U7") (pin "55") (pinfunction "PF15_55") (pintype "bidirectional"))
    )
    (net (code "437") (name "unconnected-(U7-PG0-Pad56)") (class "Default")
      (node (ref "U7") (pin "56") (pinfunction "PG0_56") (pintype "bidirectional"))
    )
    (net (code "438") (name "unconnected-(U7-PG1-Pad57)") (class "Default")
      (node (ref "U7") (pin "57") (pinfunction "PG1_57") (pintype "bidirectional"))
    )
    (net (code "439") (name "unconnected-(U7-PG4-Pad89)") (class "Default")
      (node (ref "U7") (pin "89") (pinfunction "PG4_89") (pintype "bidirectional"))
    )
    (net (code "440") (name "unconnected-(U7-PG7-Pad92)") (class "Default")
      (node (ref "U7") (pin "92") (pinfunction "PG7_92") (pintype "bidirectional"))
    )
    (net (code "441") (name "unconnected-(U7-PG8-Pad93)") (class "Default")
      (node (ref "U7") (pin "93") (pinfunction "PG8_93") (pintype "bidirectional"))
    )
  )
)
